# ReA4091_Rev4_2023-05-15_SCH.net
KiCad netlist of a schematic drawn in EasyEDA
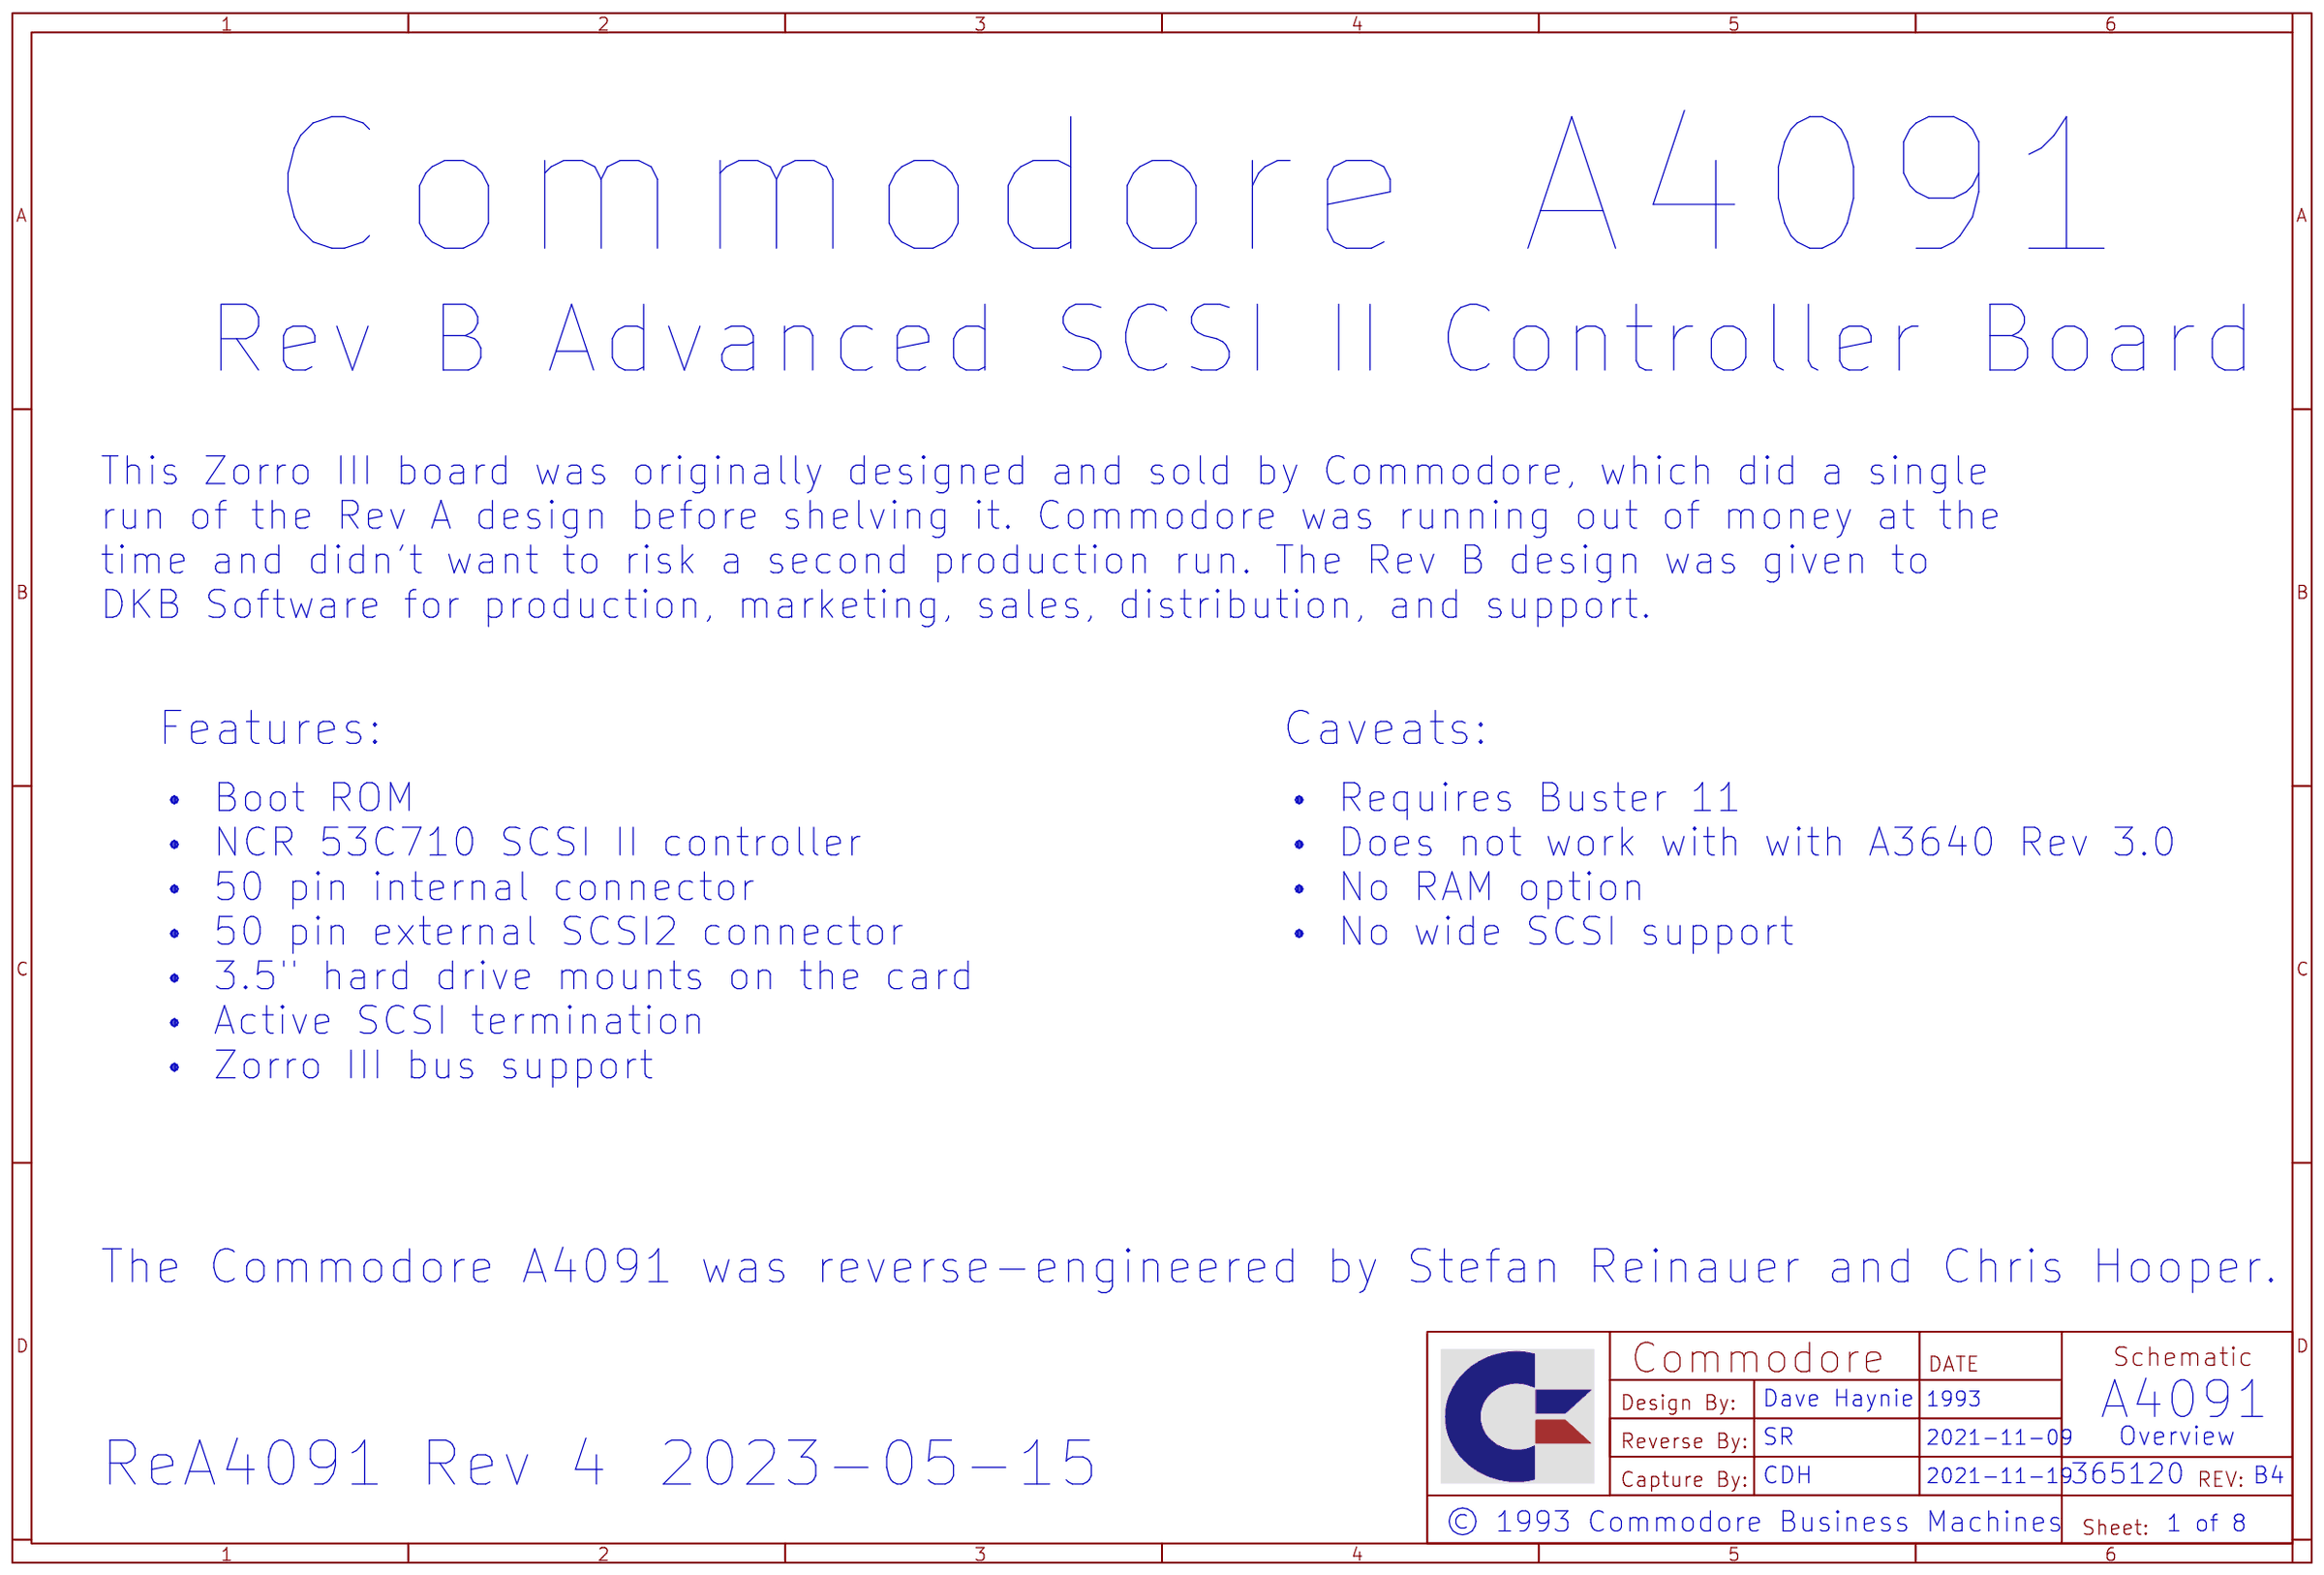
[diagram p0: Overview]
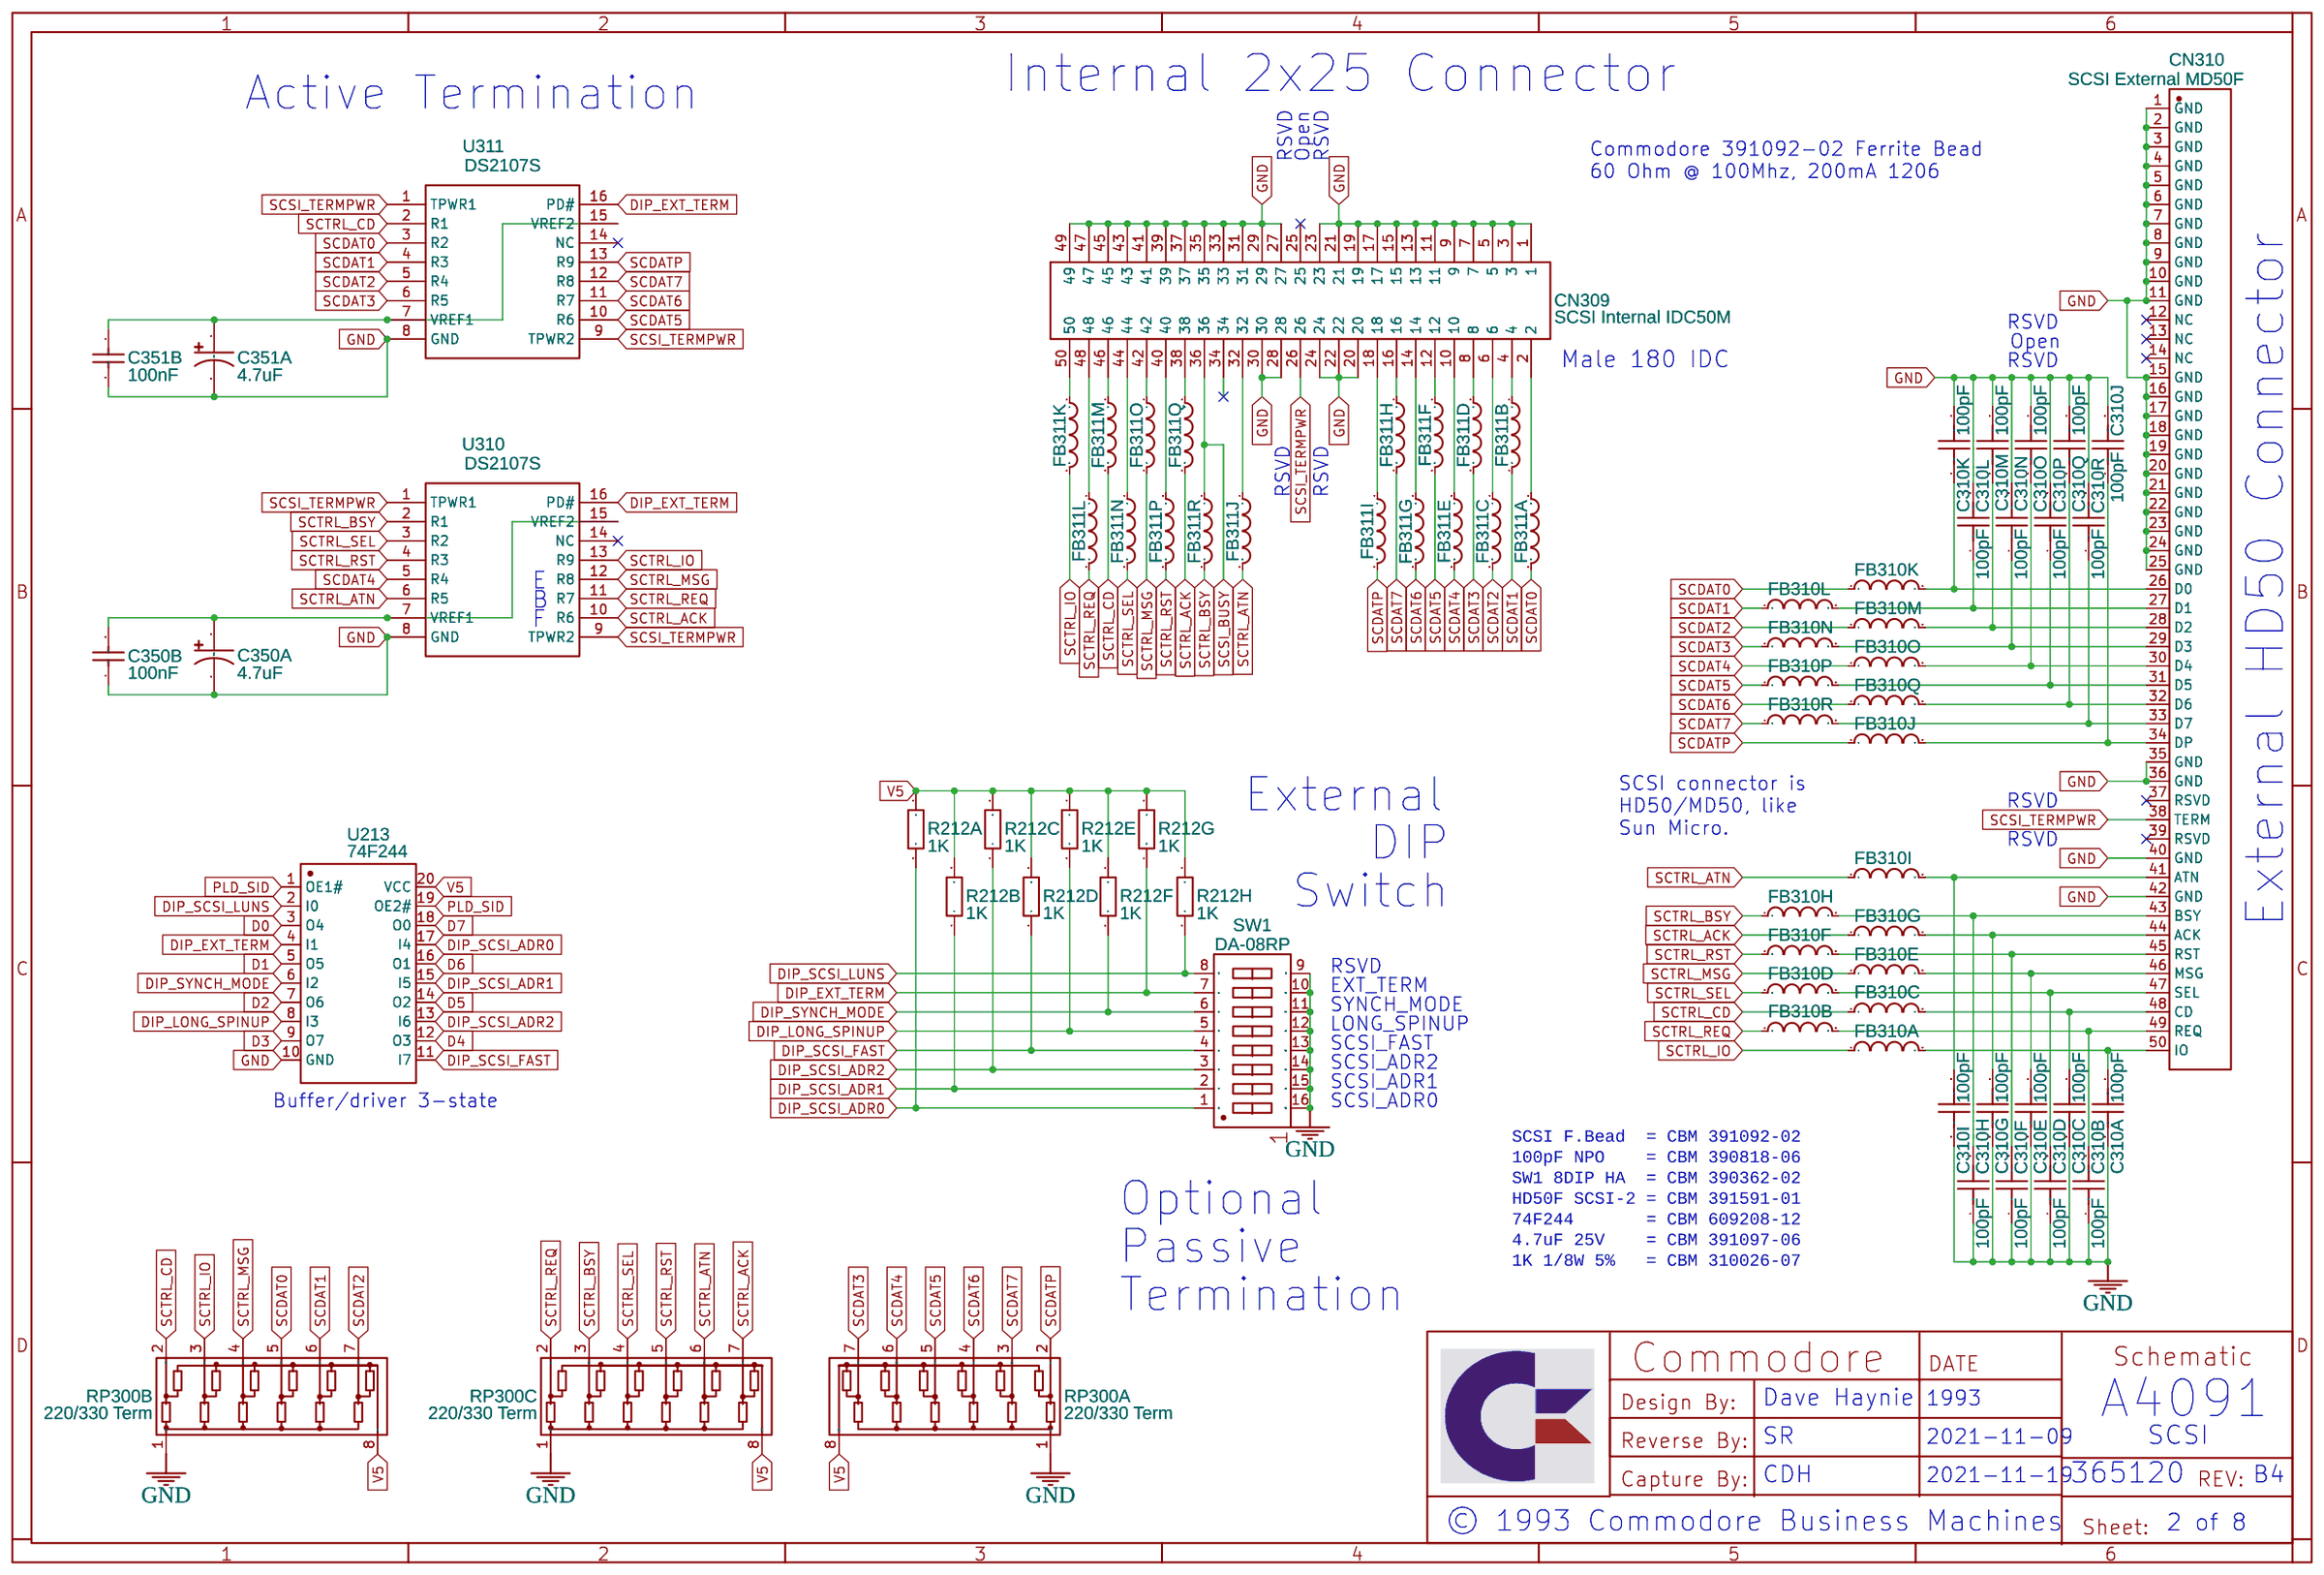
[diagram p1: SCSI]
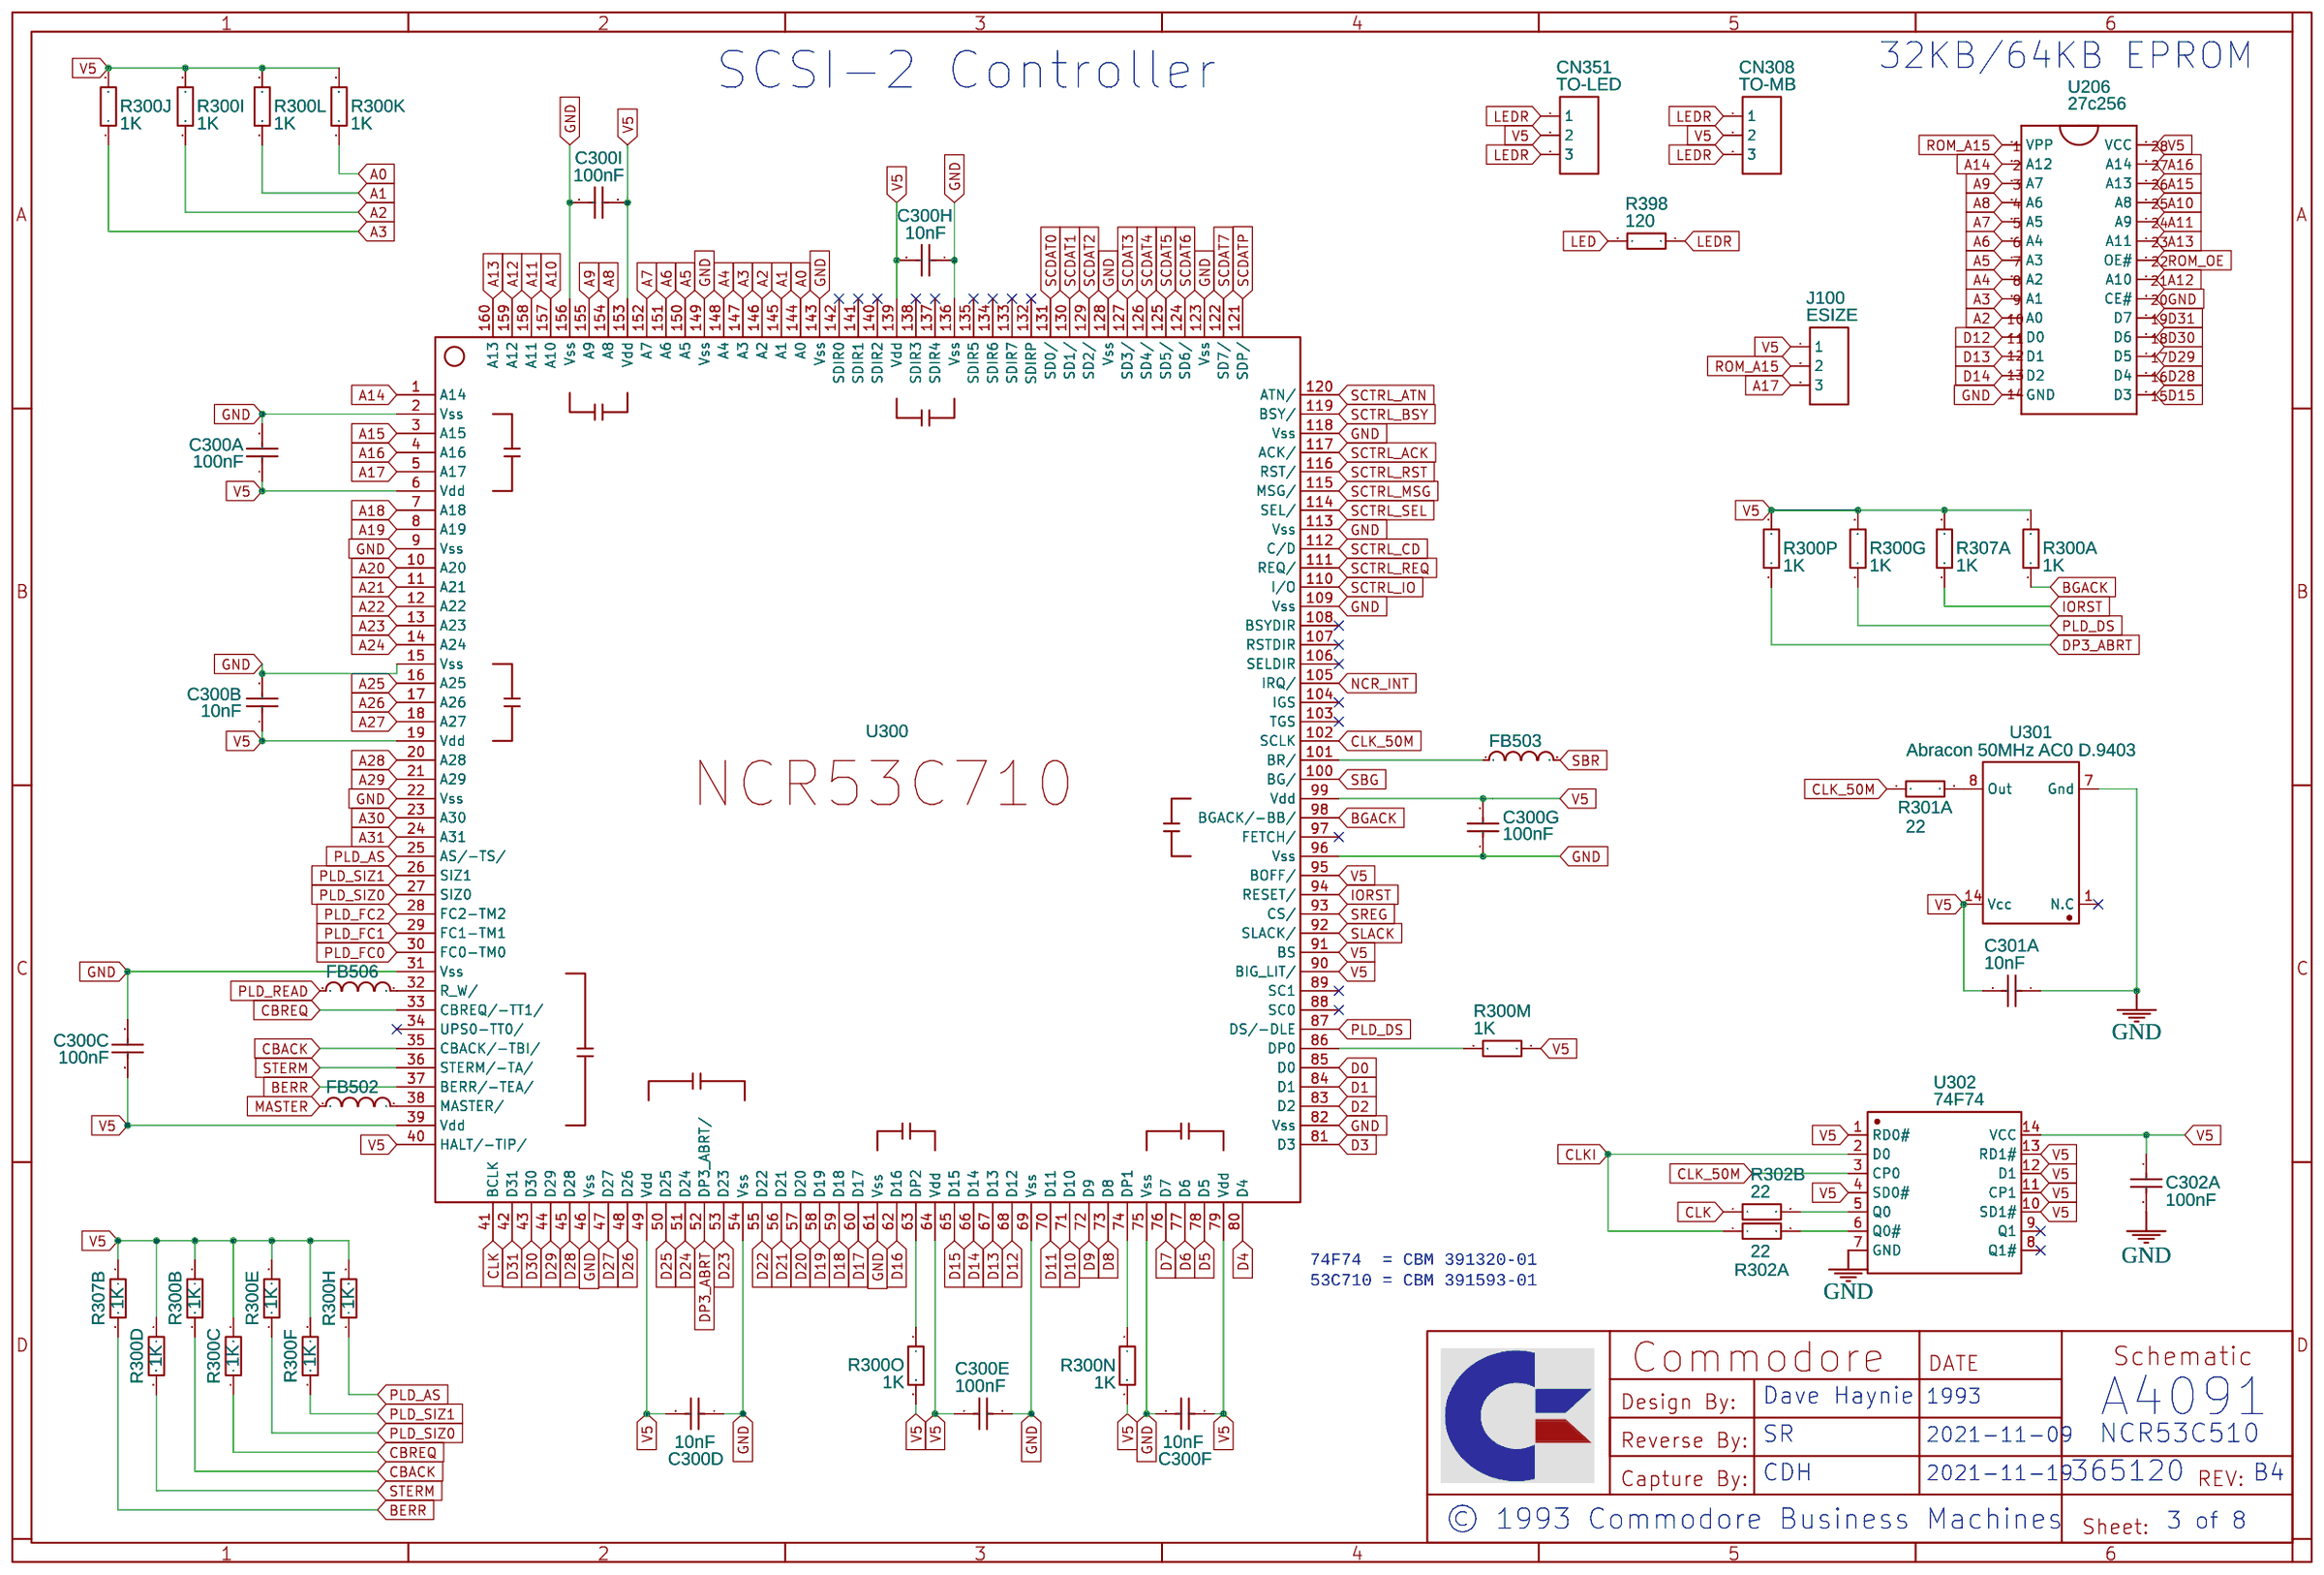
[diagram p2: NCR53C710]
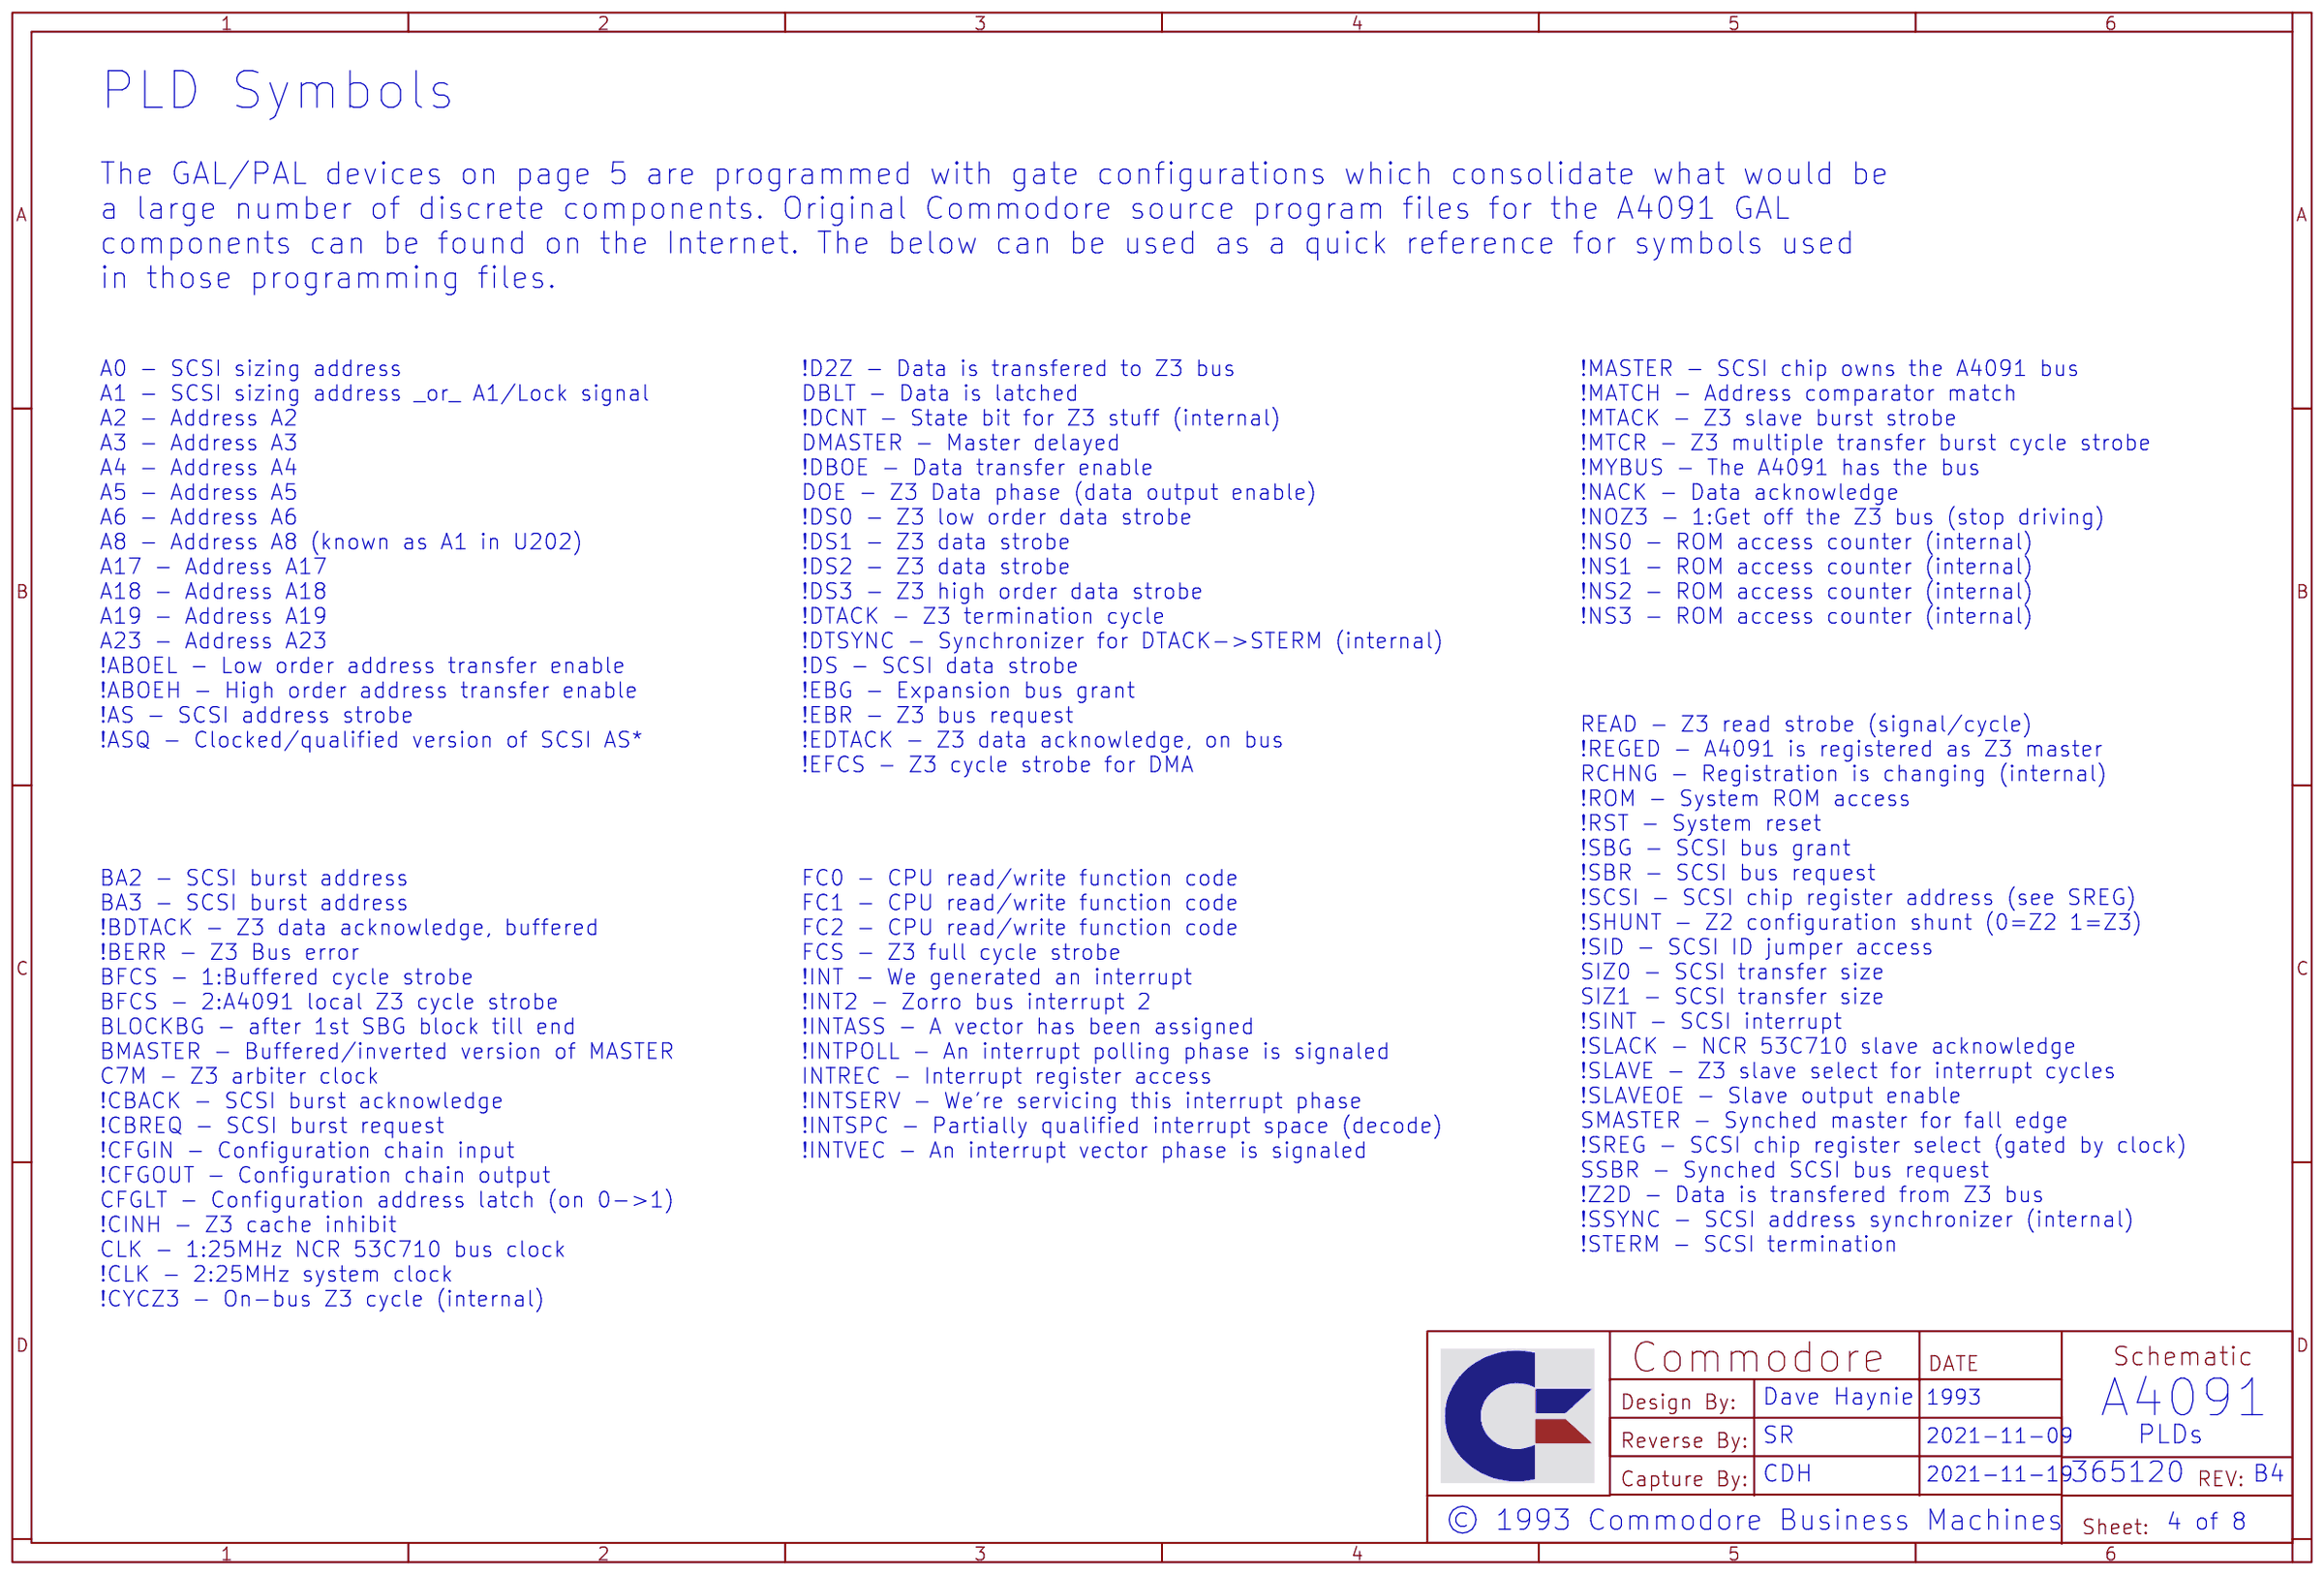
[diagram p3: PLD Symbols]
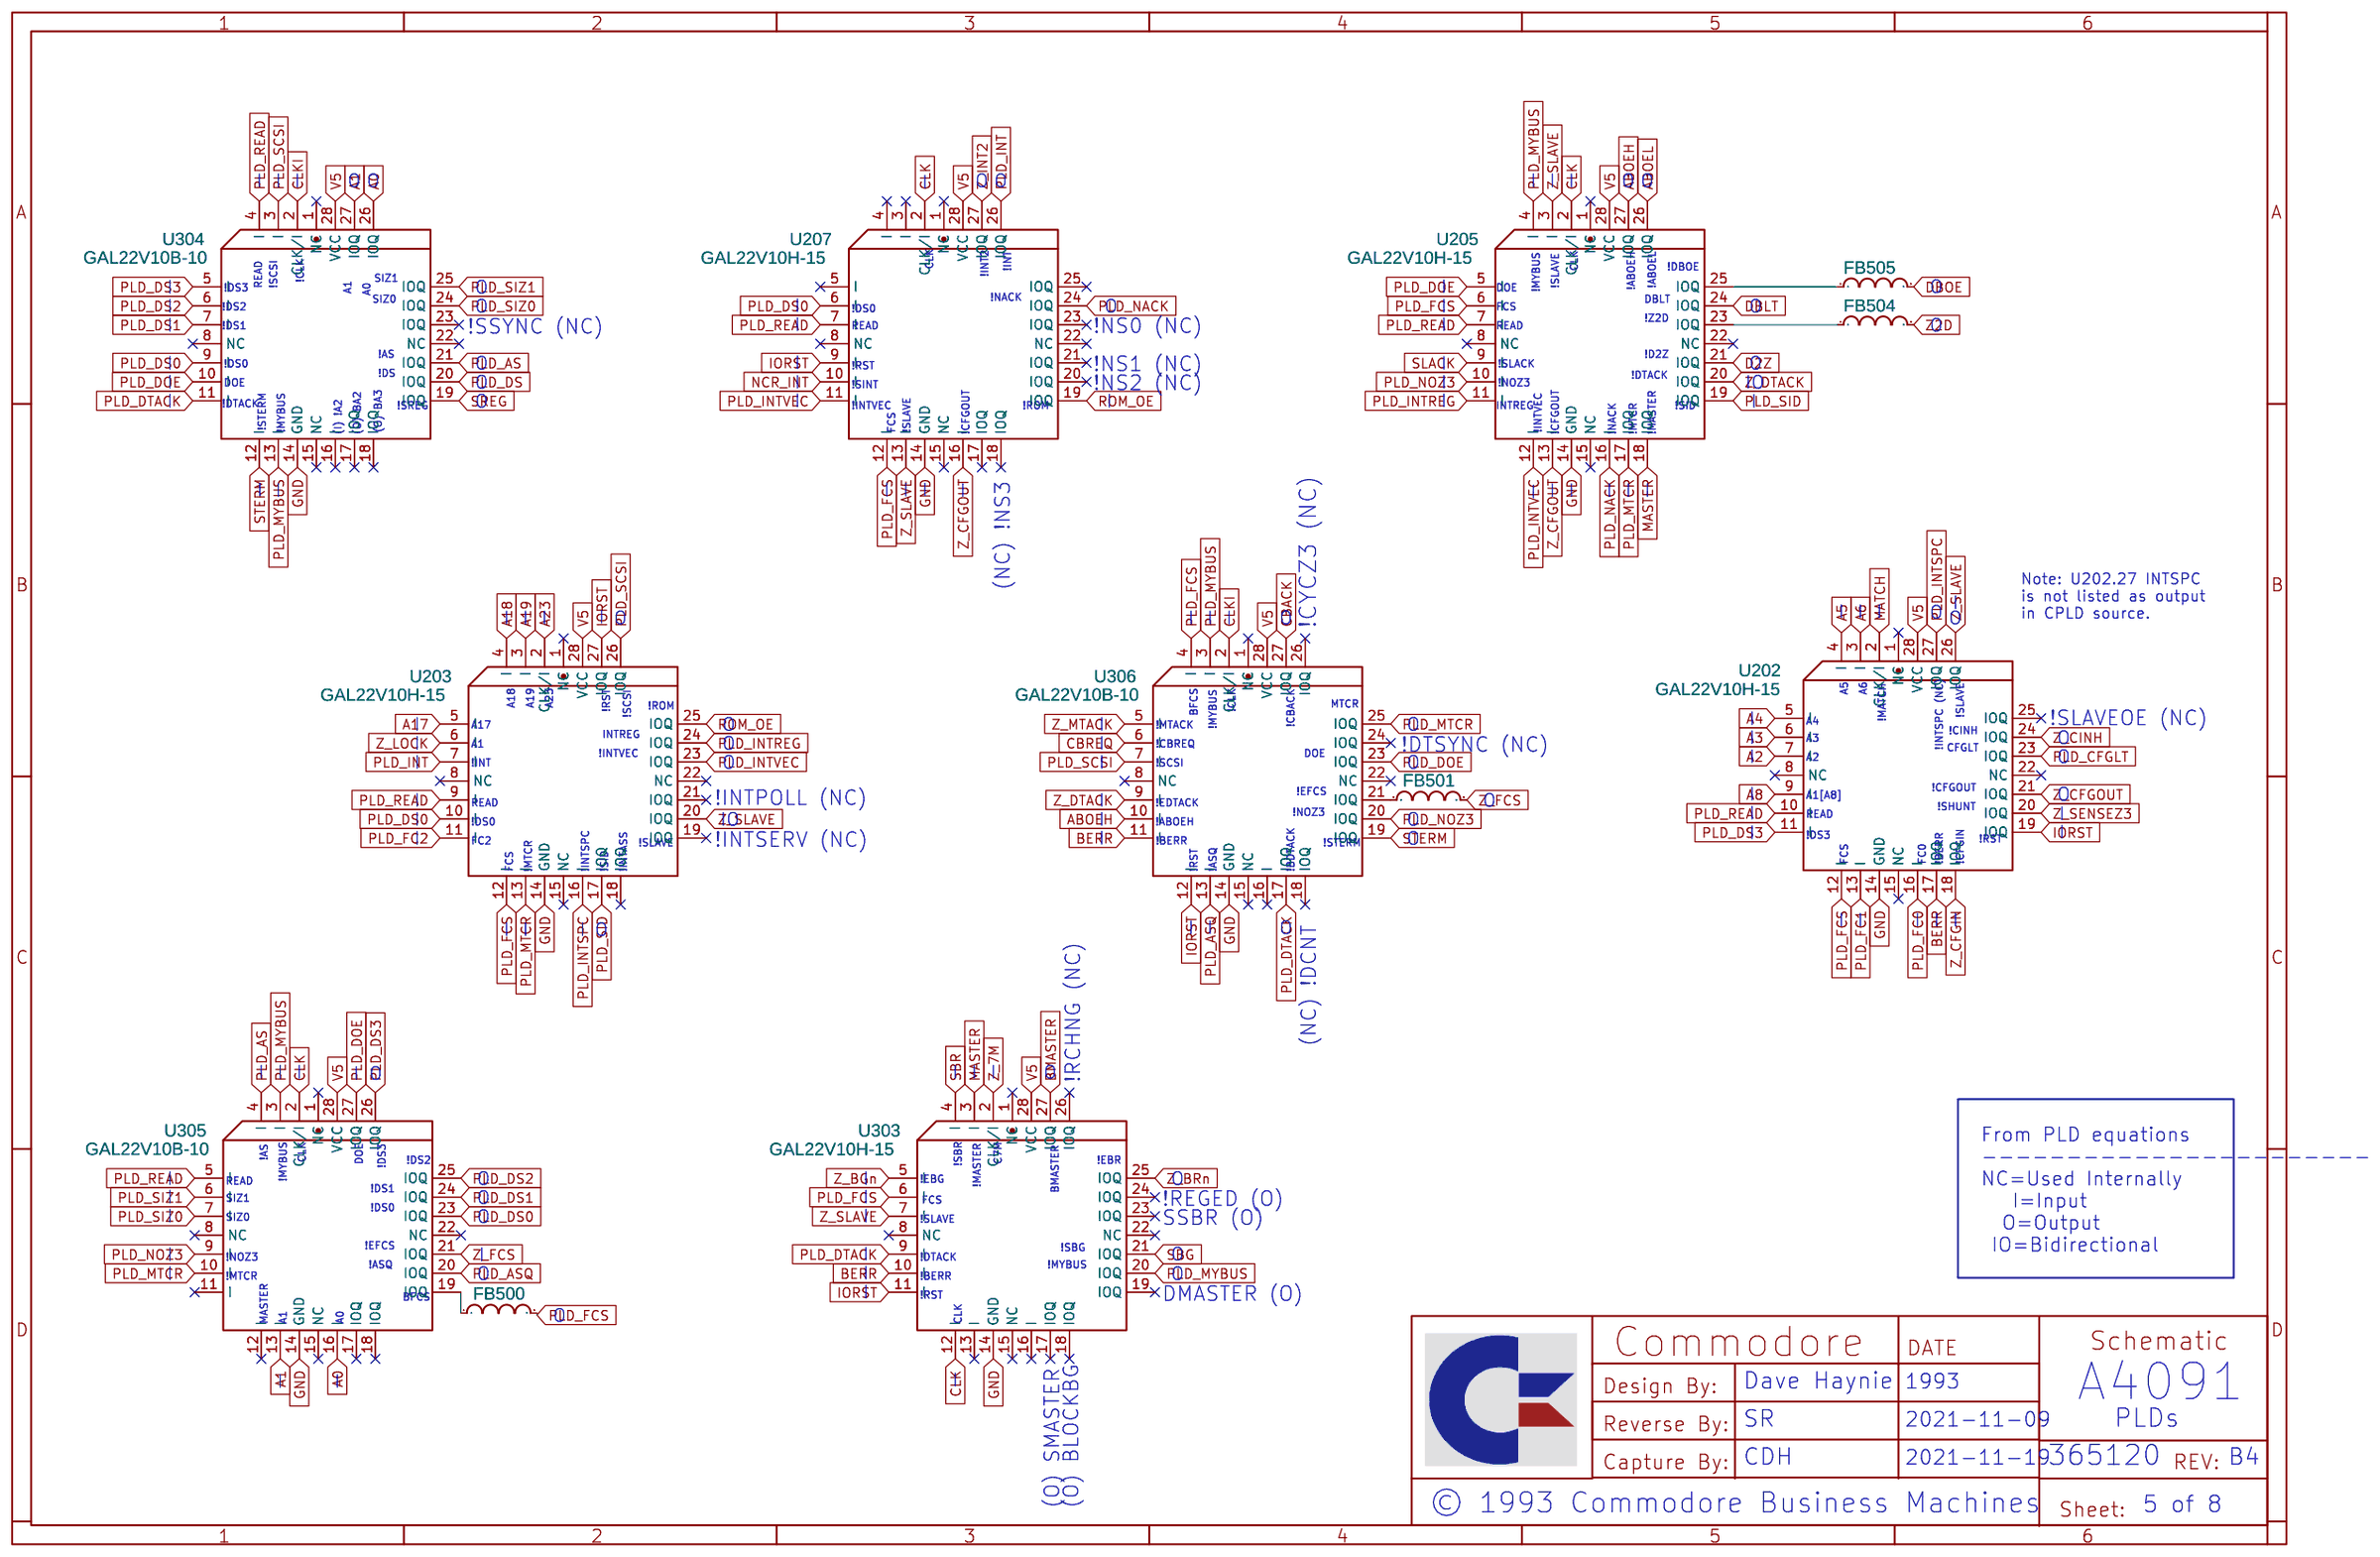
[diagram p4: PLDs]
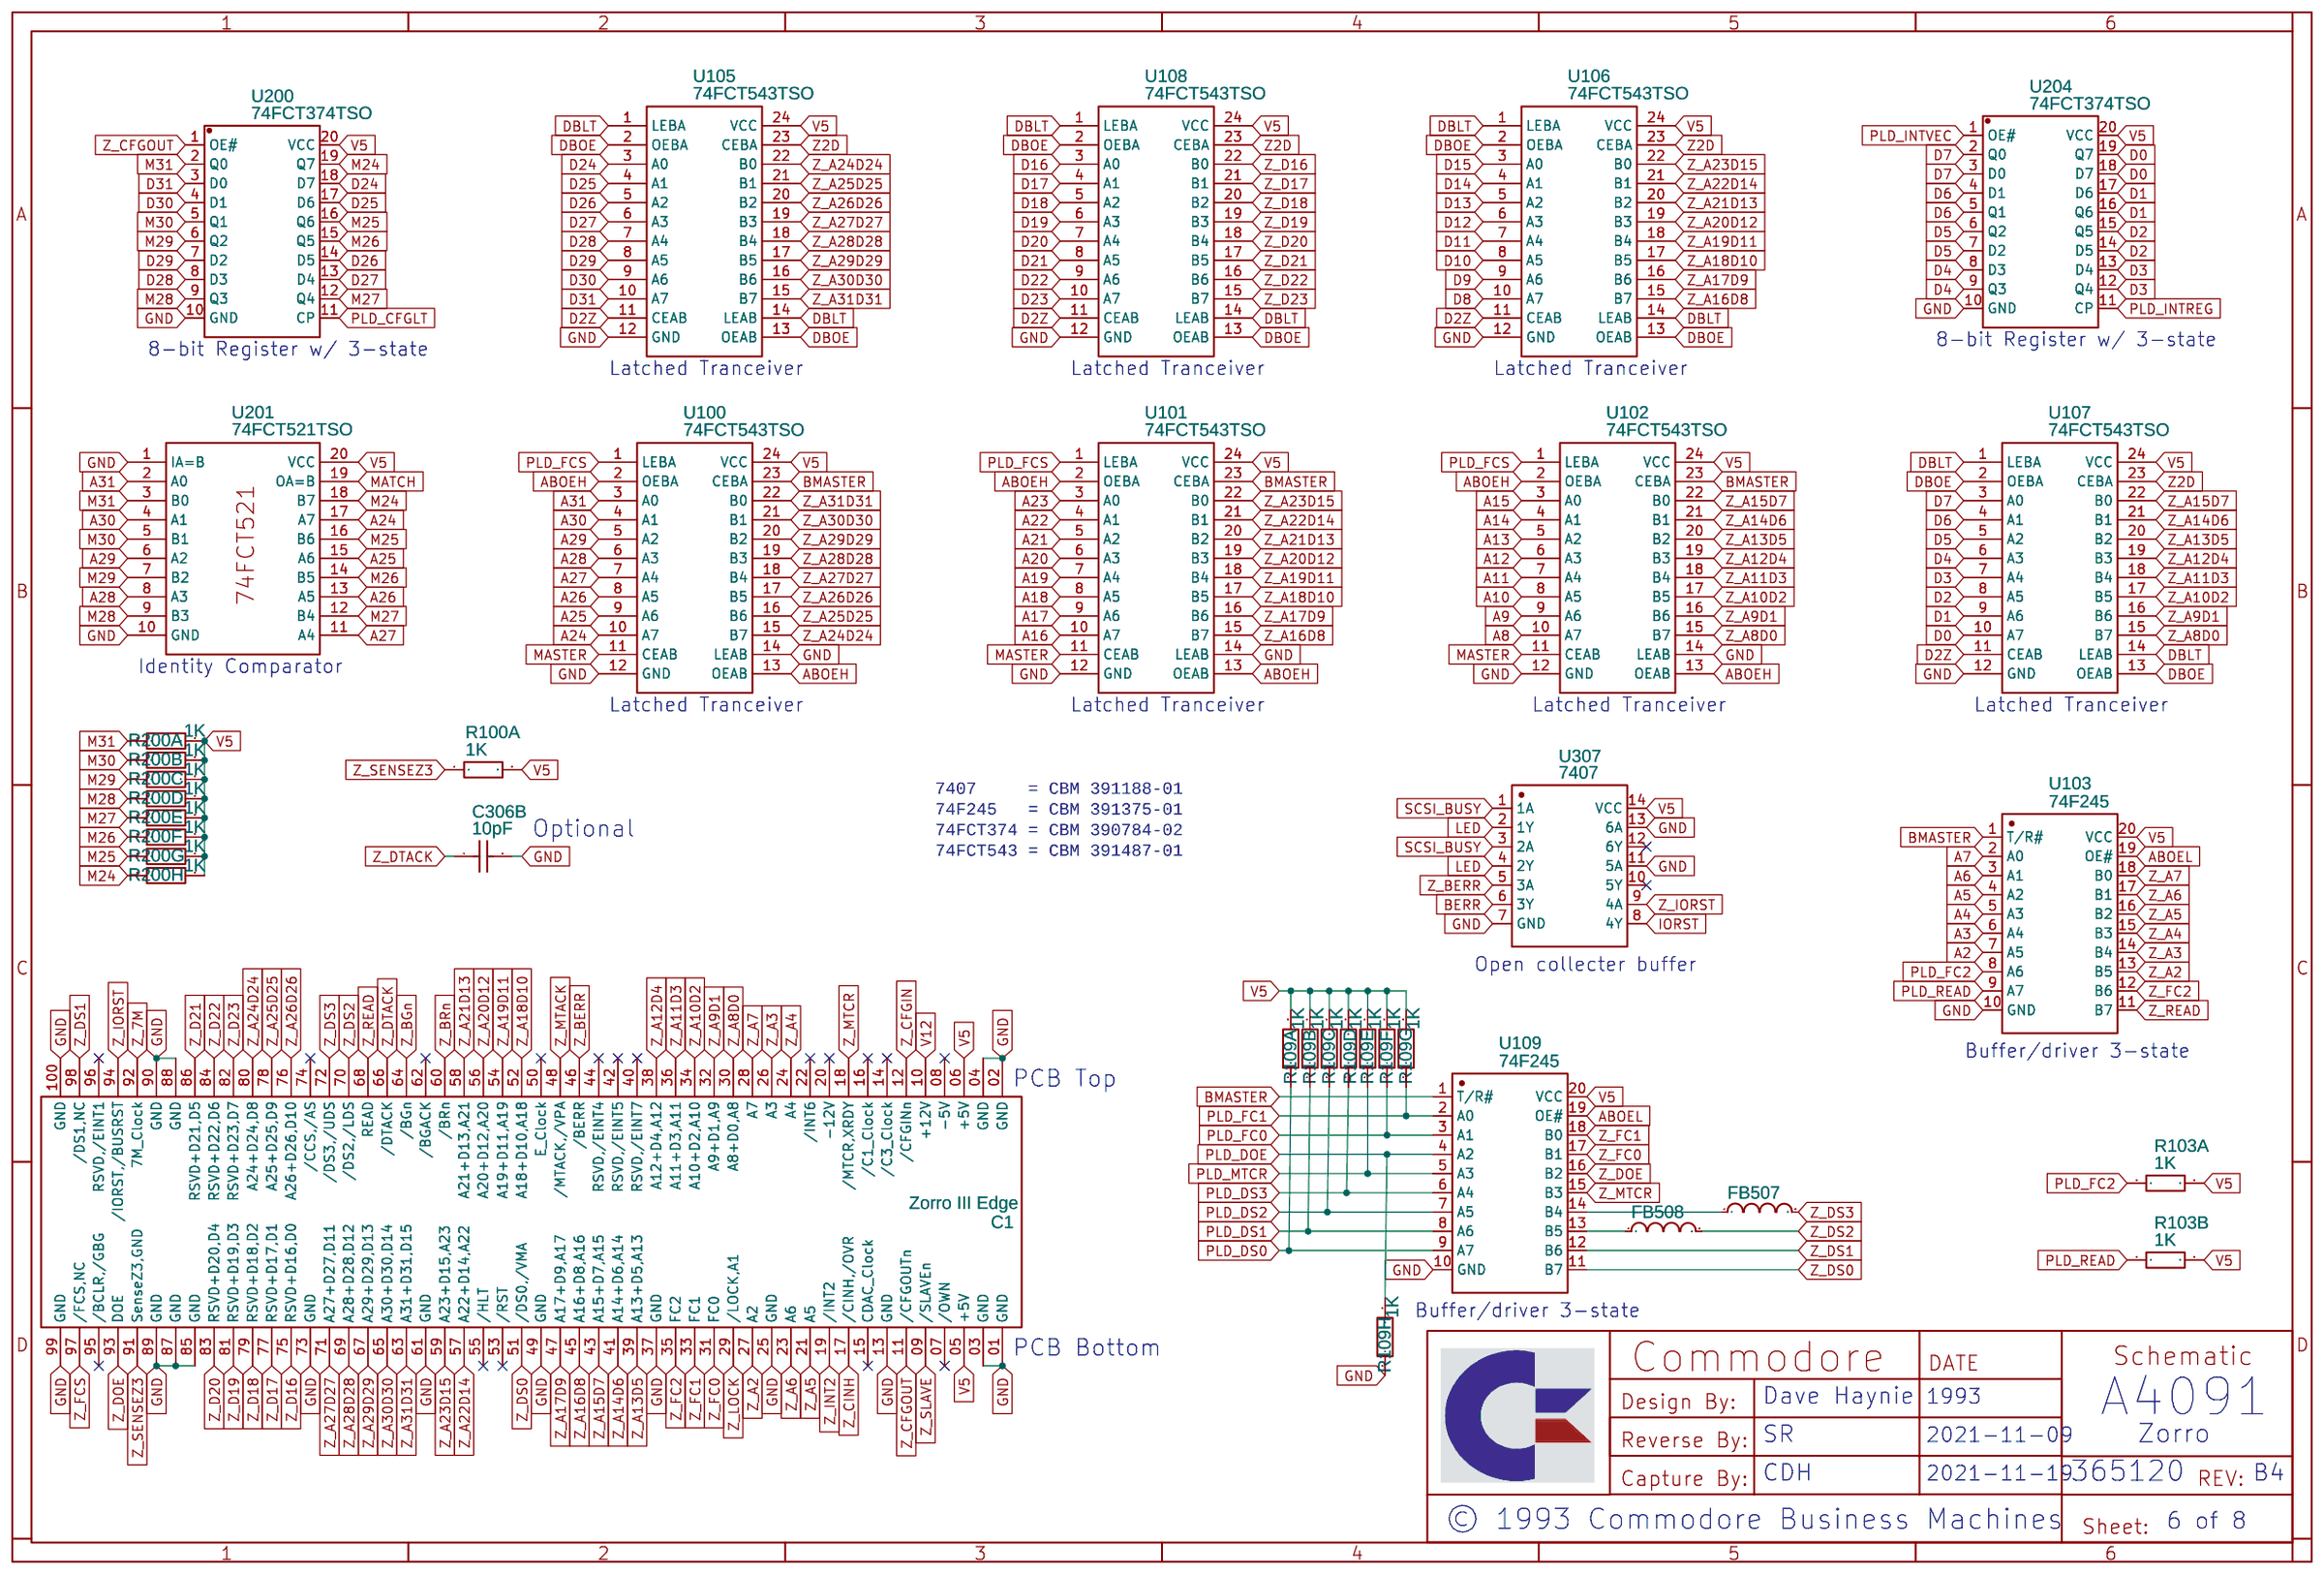
[diagram p5: Zorro]
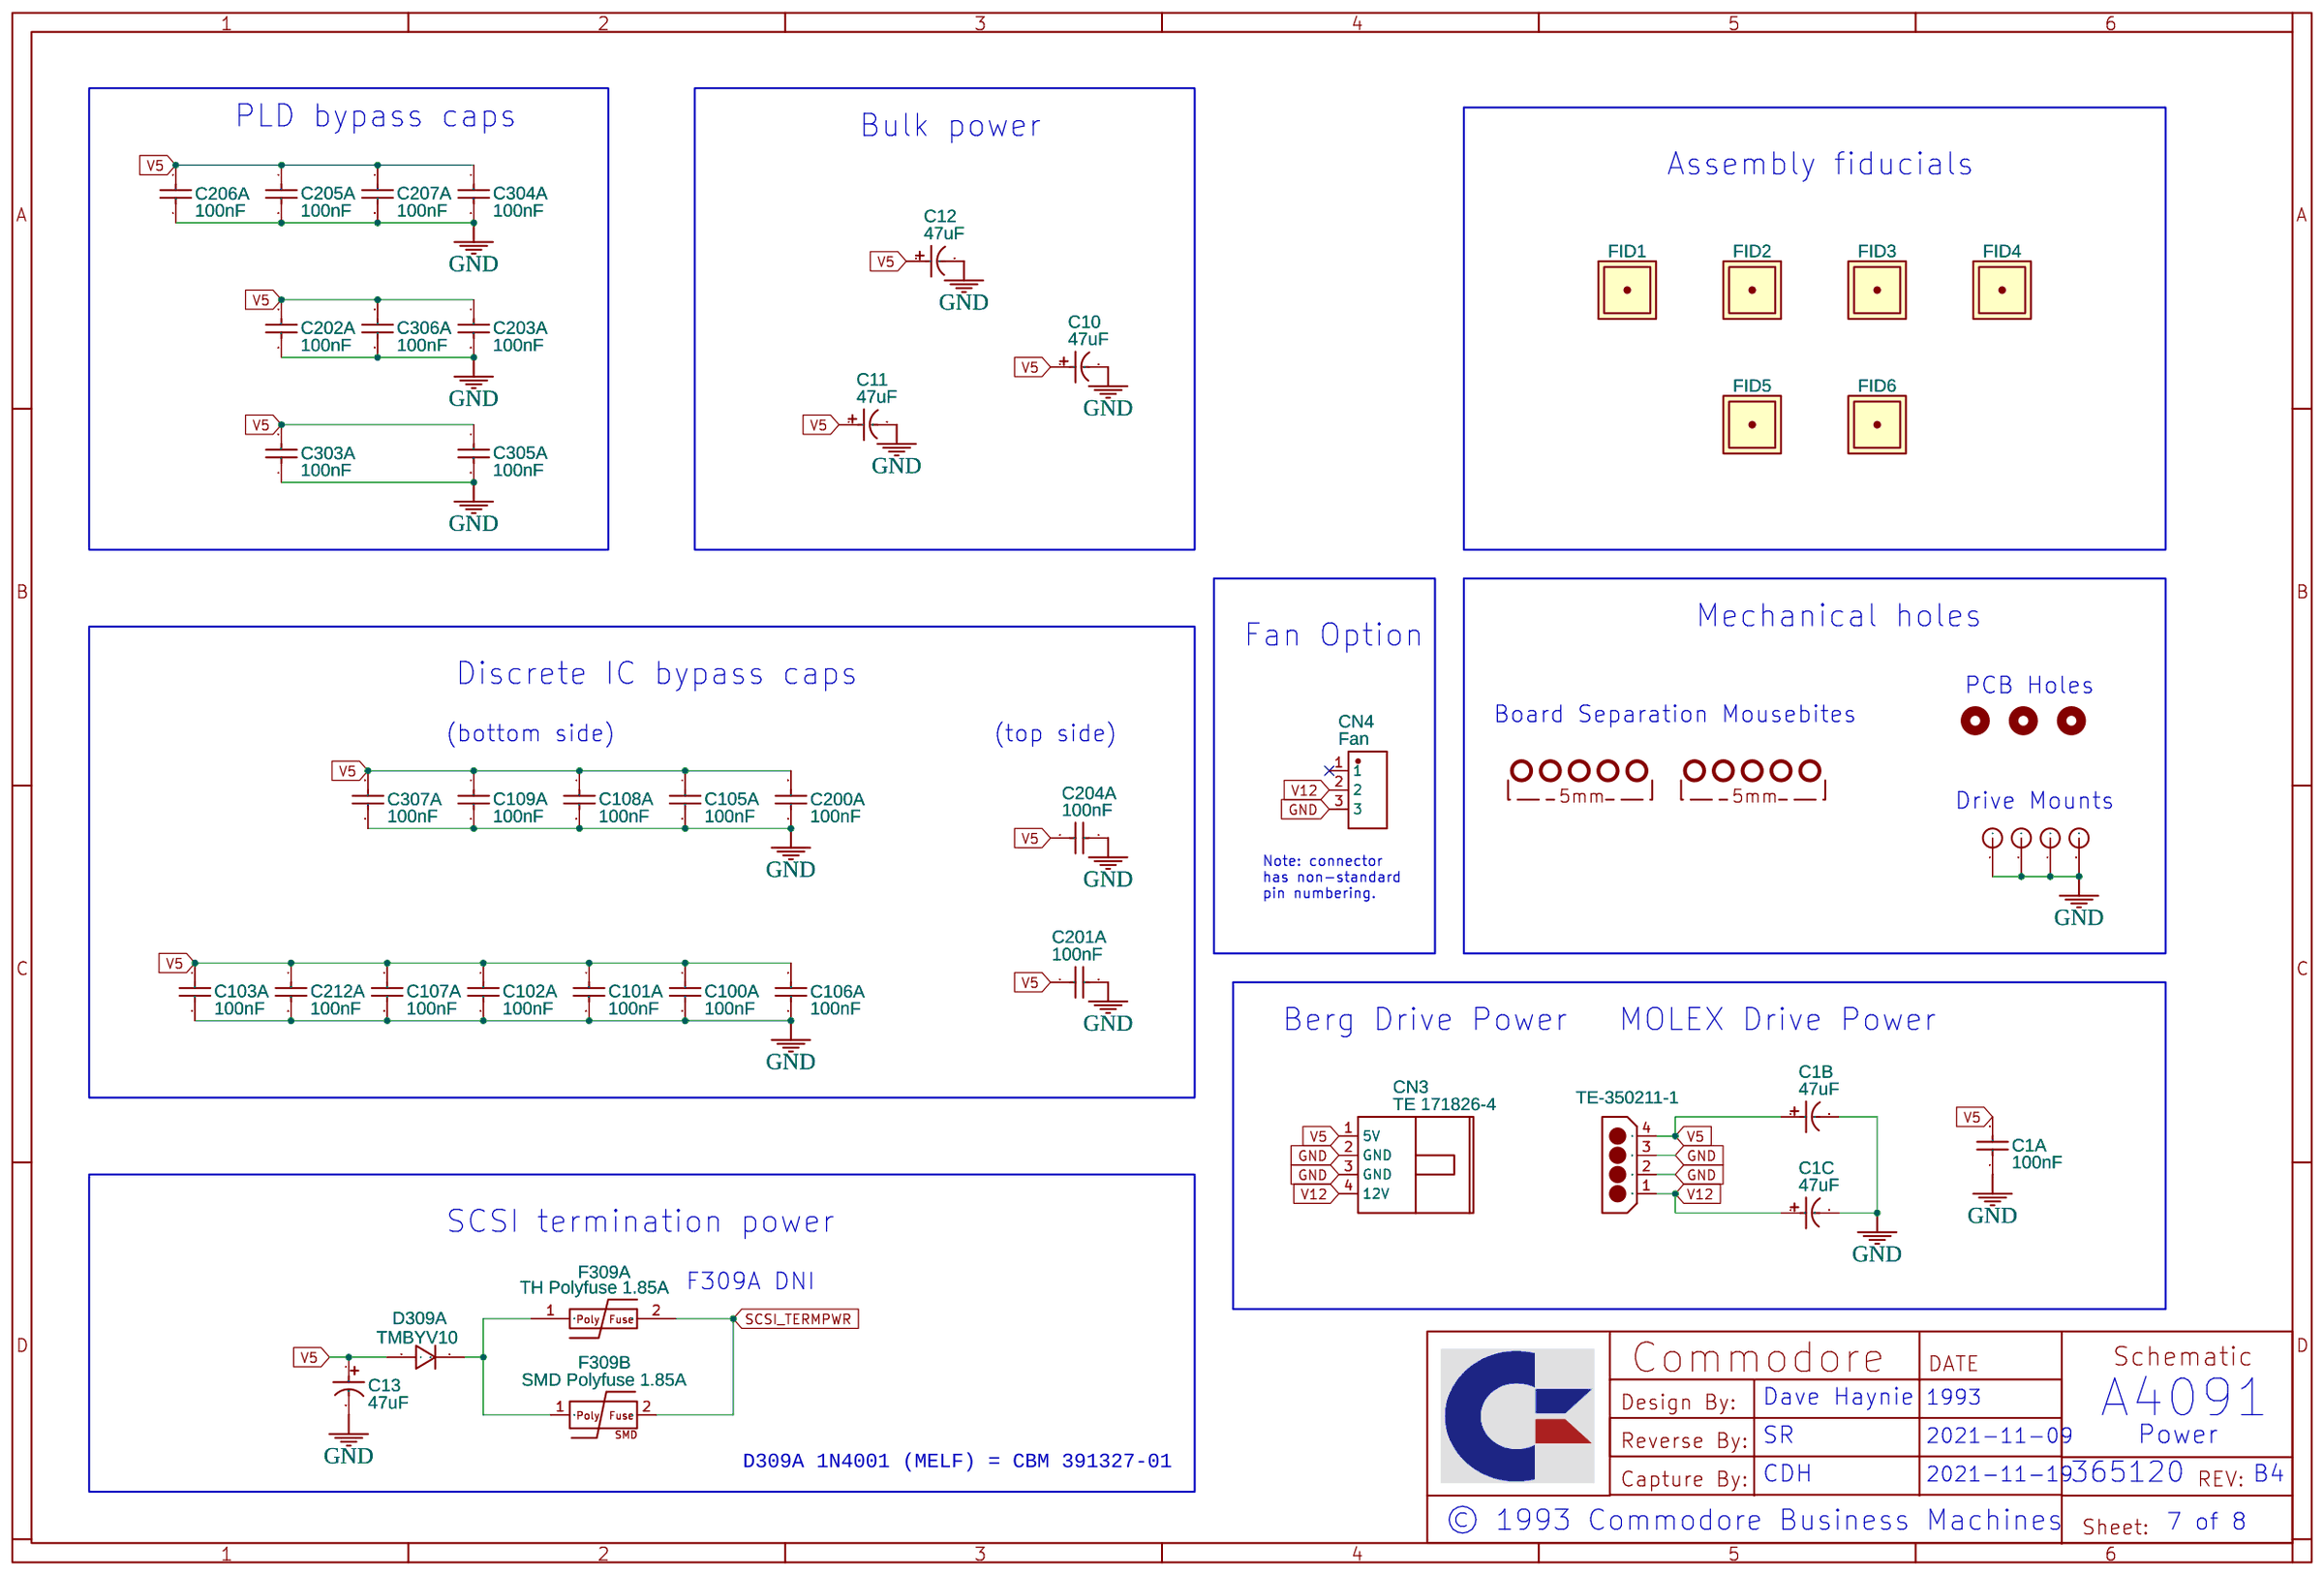
[diagram p6: Power]
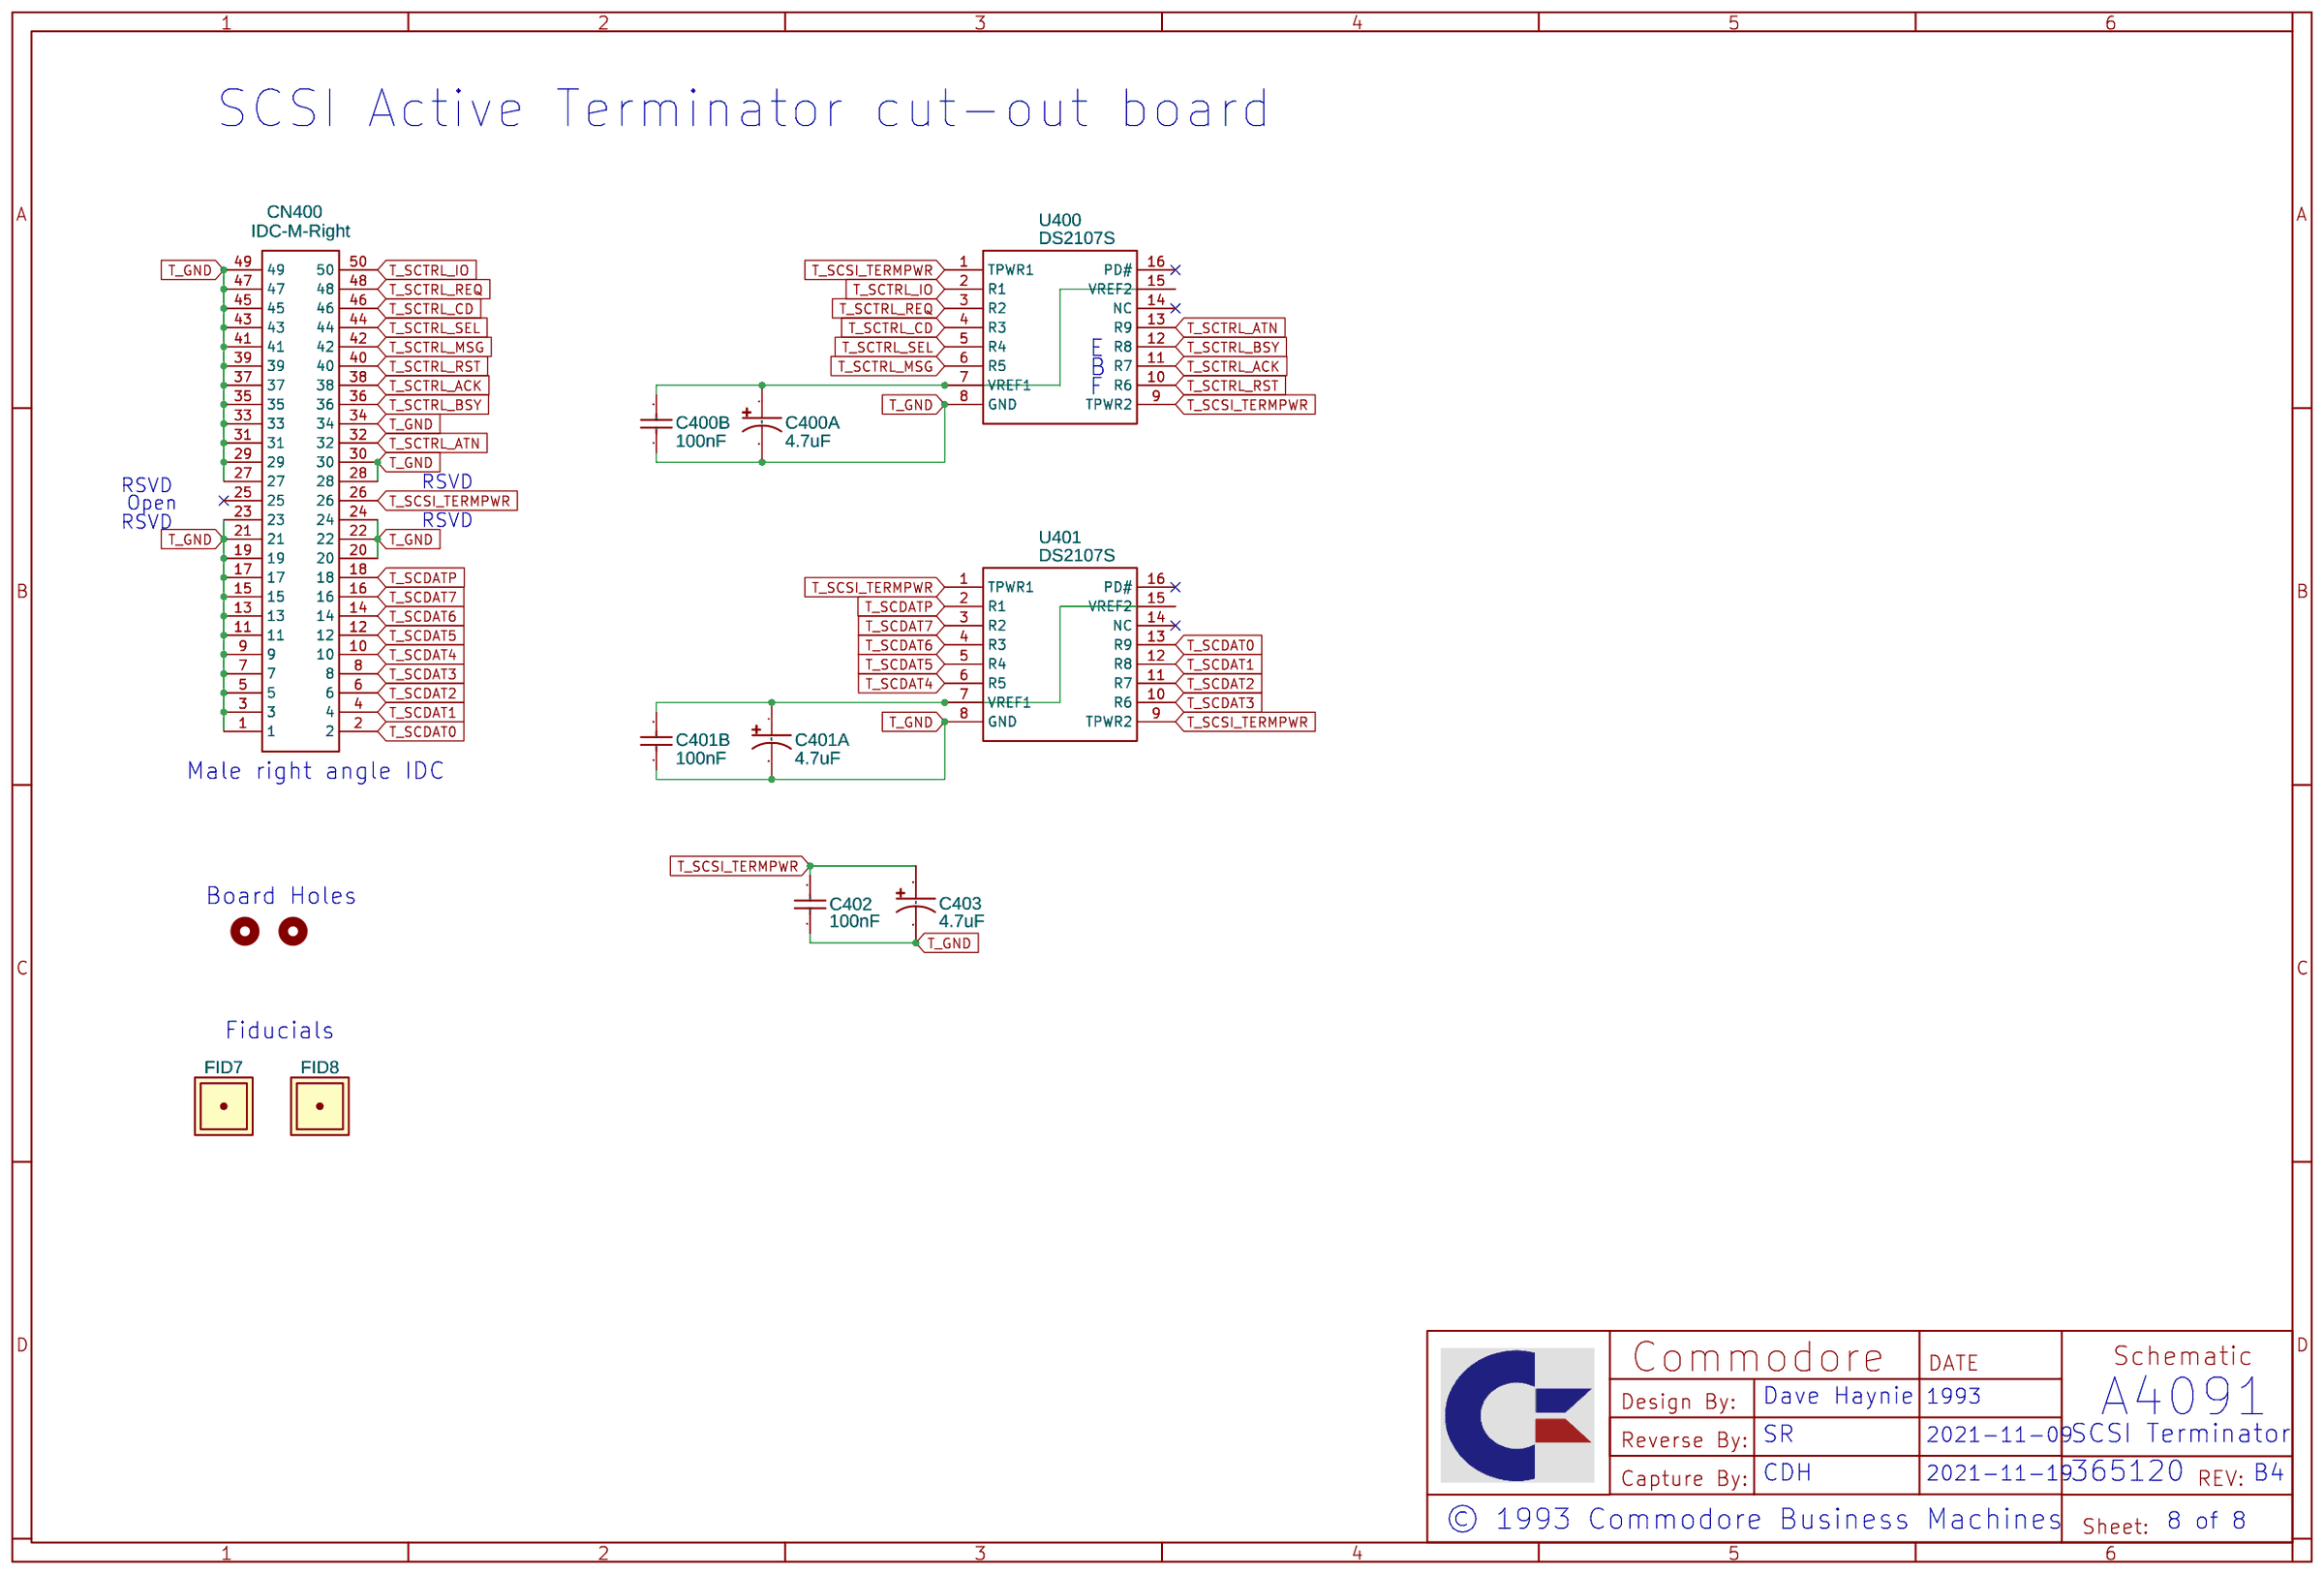
[diagram p7: SCSI Term]

(export (version "E")
  (design (tool "Eeschema 10.0.6"))
  (components
    (comp (ref "C310A")
      (value "100pF")
      (fields
        (field (name "BOM_Manufacturer Part") "TCC1206COG101J102ET")
        (field (name "BOM_Supplier Part") "C377018")
      )
      (libsource (lib "") (part "CL31C101JHFNNNE_11"))
    )
    (comp (ref "C310B")
      (value "100pF")
      (fields
        (field (name "BOM_Manufacturer Part") "TCC1206COG101J102ET")
        (field (name "BOM_Supplier Part") "C377018")
      )
      (libsource (lib "") (part "CL31C101JHFNNNE_5"))
    )
    (comp (ref "C310C")
      (value "100pF")
      (fields
        (field (name "BOM_Manufacturer Part") "TCC1206COG101J102ET")
        (field (name "BOM_Supplier Part") "C377018")
      )
      (libsource (lib "") (part "CL31C101JHFNNNE_3"))
    )
    (comp (ref "C310D")
      (value "100pF")
      (fields
        (field (name "BOM_Manufacturer Part") "TCC1206COG101J102ET")
        (field (name "BOM_Supplier Part") "C377018")
      )
      (libsource (lib "") (part "CL31C101JHFNNNE_8"))
    )
    (comp (ref "C310E")
      (value "100pF")
      (fields
        (field (name "BOM_Manufacturer Part") "TCC1206COG101J102ET")
        (field (name "BOM_Supplier Part") "C377018")
      )
      (libsource (lib "") (part "CL31C101JHFNNNE_1"))
    )
    (comp (ref "C310F")
      (value "100pF")
      (fields
        (field (name "BOM_Manufacturer Part") "TCC1206COG101J102ET")
        (field (name "BOM_Supplier Part") "C377018")
      )
      (libsource (lib "") (part "CL31C101JHFNNNE_7"))
    )
    (comp (ref "C310G")
      (value "100pF")
      (fields
        (field (name "BOM_Manufacturer Part") "TCC1206COG101J102ET")
        (field (name "BOM_Supplier Part") "C377018")
      )
      (libsource (lib "") (part "CL31C101JHFNNNE_6"))
    )
    (comp (ref "C310H")
      (value "100pF")
      (fields
        (field (name "BOM_Manufacturer Part") "TCC1206COG101J102ET")
        (field (name "BOM_Supplier Part") "C377018")
      )
      (libsource (lib "") (part "CL31C101JHFNNNE_15"))
    )
    (comp (ref "C310I")
      (value "100pF")
      (fields
        (field (name "BOM_Manufacturer Part") "TCC1206COG101J102ET")
        (field (name "BOM_Supplier Part") "C377018")
      )
      (libsource (lib "") (part "CL31C101JHFNNNE_16"))
    )
    (comp (ref "C310J")
      (value "100pF")
      (fields
        (field (name "BOM_Manufacturer Part") "TCC1206COG101J102ET")
        (field (name "BOM_Supplier Part") "C377018")
      )
      (libsource (lib "") (part "CL31C101JHFNNNE_13"))
    )
    (comp (ref "C310K")
      (value "100pF")
      (fields
        (field (name "BOM_Manufacturer Part") "TCC1206COG101J102ET")
        (field (name "BOM_Supplier Part") "C377018")
      )
      (libsource (lib "") (part "CL31C101JHFNNNE_14"))
    )
    (comp (ref "C310L")
      (value "100pF")
      (fields
        (field (name "BOM_Manufacturer Part") "TCC1206COG101J102ET")
        (field (name "BOM_Supplier Part") "C377018")
      )
      (libsource (lib "") (part "CL31C101JHFNNNE_17"))
    )
    (comp (ref "C310M")
      (value "100pF")
      (fields
        (field (name "BOM_Manufacturer Part") "TCC1206COG101J102ET")
        (field (name "BOM_Supplier Part") "C377018")
      )
      (libsource (lib "") (part "CL31C101JHFNNNE"))
    )
    (comp (ref "C310N")
      (value "100pF")
      (fields
        (field (name "BOM_Manufacturer Part") "TCC1206COG101J102ET")
        (field (name "BOM_Supplier Part") "C377018")
      )
      (libsource (lib "") (part "CL31C101JHFNNNE_2"))
    )
    (comp (ref "C310O")
      (value "100pF")
      (fields
        (field (name "BOM_Manufacturer Part") "TCC1206COG101J102ET")
        (field (name "BOM_Supplier Part") "C377018")
      )
      (libsource (lib "") (part "CL31C101JHFNNNE_4"))
    )
    (comp (ref "C310P")
      (value "100pF")
      (fields
        (field (name "BOM_Manufacturer Part") "TCC1206COG101J102ET")
        (field (name "BOM_Supplier Part") "C377018")
      )
      (libsource (lib "") (part "CL31C101JHFNNNE_12"))
    )
    (comp (ref "C310Q")
      (value "100pF")
      (fields
        (field (name "BOM_Manufacturer Part") "TCC1206COG101J102ET")
        (field (name "BOM_Supplier Part") "C377018")
      )
      (libsource (lib "") (part "CL31C101JHFNNNE_10"))
    )
    (comp (ref "C310R")
      (value "100pF")
      (fields
        (field (name "BOM_Manufacturer Part") "TCC1206COG101J102ET")
        (field (name "BOM_Supplier Part") "C377018")
      )
      (libsource (lib "") (part "CL31C101JHFNNNE_9"))
    )
    (comp (ref "C350A")
      (value "4.7uF")
      (fields
        (field (name "BOM_Manufacturer Part") "UWX1E4R7MCL1GB")
        (field (name "BOM_Supplier Part") "C445042")
      )
      (libsource (lib "") (part "VZH4R7M1HTR-0406_1"))
    )
    (comp (ref "C350B")
      (value "100nF")
      (fields
        (field (name "BOM_Manufacturer Part") "CL31B104KBCNNNC")
        (field (name "BOM_Supplier Part") "C24497")
      )
      (libsource (lib "") (part "CL31B104KBCNNNC"))
    )
    (comp (ref "C351A")
      (value "4.7uF")
      (fields
        (field (name "BOM_Manufacturer Part") "UWX1E4R7MCL1GB")
        (field (name "BOM_Supplier Part") "C445042")
      )
      (libsource (lib "") (part "VZH4R7M1HTR-0406"))
    )
    (comp (ref "C351B")
      (value "100nF")
      (fields
        (field (name "BOM_Manufacturer Part") "CL31B104KBCNNNC")
        (field (name "BOM_Supplier Part") "C24497")
      )
      (libsource (lib "") (part "CL31B104KBCNNNC_1"))
    )
    (comp (ref "CN309")
      (value "SCSI Internal IDC50M")
      (fields
        (field (name "BOM_Manufacturer Part") "B-3000S50P-0110")
        (field (name "BOM_Supplier Part") "C146633")
      )
      (libsource (lib "") (part "300S-50P"))
    )
    (comp (ref "CN310") (value "SCSI External MD50F") (libsource (lib "") (part "SCSI External MD50F")))
    (comp (ref "FB310A")
      (value "60Ω")
      (fields
        (field (name "BOM_Manufacturer Part") "CBG321609U600T")
        (field (name "BOM_Supplier Part") "C1020")
      )
      (libsource (lib "") (part "MLB3216-601(f)_32"))
    )
    (comp (ref "FB310B")
      (value "60Ω")
      (fields
        (field (name "BOM_Manufacturer Part") "CBG321609U600T")
        (field (name "BOM_Supplier Part") "C1020")
      )
      (libsource (lib "") (part "MLB3216-601(f)_28"))
    )
    (comp (ref "FB310C")
      (value "60Ω")
      (fields
        (field (name "BOM_Manufacturer Part") "CBG321609U600T")
        (field (name "BOM_Supplier Part") "C1020")
      )
      (libsource (lib "") (part "MLB3216-601(f)_26"))
    )
    (comp (ref "FB310D")
      (value "60Ω")
      (fields
        (field (name "BOM_Manufacturer Part") "CBG321609U600T")
        (field (name "BOM_Supplier Part") "C1020")
      )
      (libsource (lib "") (part "MLB3216-601(f)_19"))
    )
    (comp (ref "FB310E")
      (value "60Ω")
      (fields
        (field (name "BOM_Manufacturer Part") "CBG321609U600T")
        (field (name "BOM_Supplier Part") "C1020")
      )
      (libsource (lib "") (part "MLB3216-601(f)_4"))
    )
    (comp (ref "FB310F")
      (value "60Ω")
      (fields
        (field (name "BOM_Manufacturer Part") "CBG321609U600T")
        (field (name "BOM_Supplier Part") "C1020")
      )
      (libsource (lib "") (part "MLB3216-601(f)_31"))
    )
    (comp (ref "FB310G")
      (value "60Ω")
      (fields
        (field (name "BOM_Manufacturer Part") "CBG321609U600T")
        (field (name "BOM_Supplier Part") "C1020")
      )
      (libsource (lib "") (part "MLB3216-601(f)_5"))
    )
    (comp (ref "FB310H")
      (value "60Ω")
      (fields
        (field (name "BOM_Manufacturer Part") "CBG321609U600T")
        (field (name "BOM_Supplier Part") "C1020")
      )
      (libsource (lib "") (part "MLB3216-601(f)_34"))
    )
    (comp (ref "FB310I")
      (value "60Ω")
      (fields
        (field (name "BOM_Manufacturer Part") "CBG321609U600T")
        (field (name "BOM_Supplier Part") "C1020")
      )
      (libsource (lib "") (part "MLB3216-601(f)_1"))
    )
    (comp (ref "FB310J")
      (value "60Ω")
      (fields
        (field (name "BOM_Manufacturer Part") "CBG321609U600T")
        (field (name "BOM_Supplier Part") "C1020")
      )
      (libsource (lib "") (part "MLB3216-601(f)_9"))
    )
    (comp (ref "FB310K")
      (value "60Ω")
      (fields
        (field (name "BOM_Manufacturer Part") "CBG321609U600T")
        (field (name "BOM_Supplier Part") "C1020")
      )
      (libsource (lib "") (part "MLB3216-601(f)_29"))
    )
    (comp (ref "FB310L")
      (value "60Ω")
      (fields
        (field (name "BOM_Manufacturer Part") "CBG321609U600T")
        (field (name "BOM_Supplier Part") "C1020")
      )
      (libsource (lib "") (part "MLB3216-601(f)_24"))
    )
    (comp (ref "FB310M")
      (value "60Ω")
      (fields
        (field (name "BOM_Manufacturer Part") "CBG321609U600T")
        (field (name "BOM_Supplier Part") "C1020")
      )
      (libsource (lib "") (part "MLB3216-601(f)"))
    )
    (comp (ref "FB310N")
      (value "60Ω")
      (fields
        (field (name "BOM_Manufacturer Part") "CBG321609U600T")
        (field (name "BOM_Supplier Part") "C1020")
      )
      (libsource (lib "") (part "MLB3216-601(f)_22"))
    )
    (comp (ref "FB310O")
      (value "60Ω")
      (fields
        (field (name "BOM_Manufacturer Part") "CBG321609U600T")
        (field (name "BOM_Supplier Part") "C1020")
      )
      (libsource (lib "") (part "MLB3216-601(f)_12"))
    )
    (comp (ref "FB310P")
      (value "60Ω")
      (fields
        (field (name "BOM_Manufacturer Part") "CBG321609U600T")
        (field (name "BOM_Supplier Part") "C1020")
      )
      (libsource (lib "") (part "MLB3216-601(f)_6"))
    )
    (comp (ref "FB310Q")
      (value "60Ω")
      (fields
        (field (name "BOM_Manufacturer Part") "CBG321609U600T")
        (field (name "BOM_Supplier Part") "C1020")
      )
      (libsource (lib "") (part "MLB3216-601(f)_11"))
    )
    (comp (ref "FB310R")
      (value "60Ω")
      (fields
        (field (name "BOM_Manufacturer Part") "CBG321609U600T")
        (field (name "BOM_Supplier Part") "C1020")
      )
      (libsource (lib "") (part "MLB3216-601(f)_17"))
    )
    (comp (ref "FB311A")
      (value "60Ω")
      (fields
        (field (name "BOM_Manufacturer Part") "CBG321609U600T")
        (field (name "BOM_Supplier Part") "C1020")
      )
      (libsource (lib "") (part "MLB3216-601(f)_16"))
    )
    (comp (ref "FB311B")
      (value "60Ω")
      (fields
        (field (name "BOM_Manufacturer Part") "CBG321609U600T")
        (field (name "BOM_Supplier Part") "C1020")
      )
      (libsource (lib "") (part "MLB3216-601(f)_21"))
    )
    (comp (ref "FB311C")
      (value "60Ω")
      (fields
        (field (name "BOM_Manufacturer Part") "CBG321609U600T")
        (field (name "BOM_Supplier Part") "C1020")
      )
      (libsource (lib "") (part "MLB3216-601(f)_15"))
    )
    (comp (ref "FB311D")
      (value "60Ω")
      (fields
        (field (name "BOM_Manufacturer Part") "CBG321609U600T")
        (field (name "BOM_Supplier Part") "C1020")
      )
      (libsource (lib "") (part "MLB3216-601(f)_25"))
    )
    (comp (ref "FB311E")
      (value "60Ω")
      (fields
        (field (name "BOM_Manufacturer Part") "CBG321609U600T")
        (field (name "BOM_Supplier Part") "C1020")
      )
      (libsource (lib "") (part "MLB3216-601(f)_18"))
    )
    (comp (ref "FB311F")
      (value "60Ω")
      (fields
        (field (name "BOM_Manufacturer Part") "CBG321609U600T")
        (field (name "BOM_Supplier Part") "C1020")
      )
      (libsource (lib "") (part "MLB3216-601(f)_13"))
    )
    (comp (ref "FB311G")
      (value "60Ω")
      (fields
        (field (name "BOM_Manufacturer Part") "CBG321609U600T")
        (field (name "BOM_Supplier Part") "C1020")
      )
      (libsource (lib "") (part "MLB3216-601(f)_35"))
    )
    (comp (ref "FB311H")
      (value "60Ω")
      (fields
        (field (name "BOM_Manufacturer Part") "CBG321609U600T")
        (field (name "BOM_Supplier Part") "C1020")
      )
      (libsource (lib "") (part "MLB3216-601(f)_8"))
    )
    (comp (ref "FB311I")
      (value "60Ω")
      (fields
        (field (name "BOM_Manufacturer Part") "CBG321609U600T")
        (field (name "BOM_Supplier Part") "C1020")
      )
      (libsource (lib "") (part "MLB3216-601(f)_10"))
    )
    (comp (ref "FB311J")
      (value "60Ω")
      (fields
        (field (name "BOM_Manufacturer Part") "CBG321609U600T")
        (field (name "BOM_Supplier Part") "C1020")
      )
      (libsource (lib "") (part "MLB3216-601(f)_30"))
    )
    (comp (ref "FB311K")
      (value "60Ω")
      (fields
        (field (name "BOM_Manufacturer Part") "CBG321609U600T")
        (field (name "BOM_Supplier Part") "C1020")
      )
      (libsource (lib "") (part "MLB3216-601(f)_3"))
    )
    (comp (ref "FB311L")
      (value "60Ω")
      (fields
        (field (name "BOM_Manufacturer Part") "CBG321609U600T")
        (field (name "BOM_Supplier Part") "C1020")
      )
      (libsource (lib "") (part "MLB3216-601(f)_20"))
    )
    (comp (ref "FB311M")
      (value "60Ω")
      (fields
        (field (name "BOM_Manufacturer Part") "CBG321609U600T")
        (field (name "BOM_Supplier Part") "C1020")
      )
      (libsource (lib "") (part "MLB3216-601(f)_2"))
    )
    (comp (ref "FB311N")
      (value "60Ω")
      (fields
        (field (name "BOM_Manufacturer Part") "CBG321609U600T")
        (field (name "BOM_Supplier Part") "C1020")
      )
      (libsource (lib "") (part "MLB3216-601(f)_33"))
    )
    (comp (ref "FB311O")
      (value "60Ω")
      (fields
        (field (name "BOM_Manufacturer Part") "CBG321609U600T")
        (field (name "BOM_Supplier Part") "C1020")
      )
      (libsource (lib "") (part "MLB3216-601(f)_27"))
    )
    (comp (ref "FB311P")
      (value "60Ω")
      (fields
        (field (name "BOM_Manufacturer Part") "CBG321609U600T")
        (field (name "BOM_Supplier Part") "C1020")
      )
      (libsource (lib "") (part "MLB3216-601(f)_14"))
    )
    (comp (ref "FB311Q")
      (value "60Ω")
      (fields
        (field (name "BOM_Manufacturer Part") "CBG321609U600T")
        (field (name "BOM_Supplier Part") "C1020")
      )
      (libsource (lib "") (part "MLB3216-601(f)_7"))
    )
    (comp (ref "FB311R")
      (value "60Ω")
      (fields
        (field (name "BOM_Manufacturer Part") "CBG321609U600T")
        (field (name "BOM_Supplier Part") "C1020")
      )
      (libsource (lib "") (part "MLB3216-601(f)_23"))
    )
    (comp (ref "R212A")
      (value "1K")
      (fields
        (field (name "BOM_Manufacturer Part") "1206W4F1001T5E")
        (field (name "BOM_Supplier Part") "C4410")
      )
      (libsource (lib "") (part "1206W4F1001T5E_3"))
    )
    (comp (ref "R212B")
      (value "1K")
      (fields
        (field (name "BOM_Manufacturer Part") "1206W4F1001T5E")
        (field (name "BOM_Supplier Part") "C4410")
      )
      (libsource (lib "") (part "1206W4F1001T5E_4"))
    )
    (comp (ref "R212C")
      (value "1K")
      (fields
        (field (name "BOM_Manufacturer Part") "1206W4F1001T5E")
        (field (name "BOM_Supplier Part") "C4410")
      )
      (libsource (lib "") (part "1206W4F1001T5E_5"))
    )
    (comp (ref "R212D")
      (value "1K")
      (fields
        (field (name "BOM_Manufacturer Part") "1206W4F1001T5E")
        (field (name "BOM_Supplier Part") "C4410")
      )
      (libsource (lib "") (part "1206W4F1001T5E_7"))
    )
    (comp (ref "R212E")
      (value "1K")
      (fields
        (field (name "BOM_Manufacturer Part") "1206W4F1001T5E")
        (field (name "BOM_Supplier Part") "C4410")
      )
      (libsource (lib "") (part "1206W4F1001T5E"))
    )
    (comp (ref "R212F")
      (value "1K")
      (fields
        (field (name "BOM_Manufacturer Part") "1206W4F1001T5E")
        (field (name "BOM_Supplier Part") "C4410")
      )
      (libsource (lib "") (part "1206W4F1001T5E_6"))
    )
    (comp (ref "R212G")
      (value "1K")
      (fields
        (field (name "BOM_Manufacturer Part") "1206W4F1001T5E")
        (field (name "BOM_Supplier Part") "C4410")
      )
      (libsource (lib "") (part "1206W4F1001T5E_2"))
    )
    (comp (ref "R212H")
      (value "1K")
      (fields
        (field (name "BOM_Manufacturer Part") "1206W4F1001T5E")
        (field (name "BOM_Supplier Part") "C4410")
      )
      (libsource (lib "") (part "1206W4F1001T5E_1"))
    )
    (comp (ref "RP300A")
      (value "220/330 Term")
      (fields
        (field (name "BOM_Manufacturer Part") "4608X-104-331/221L")
        (field (name "BOM_Supplier Part") "652-4608X104331/221L")
      )
      (libsource (lib "") (part "SCSI Terminator sip-8"))
    )
    (comp (ref "RP300B")
      (value "220/330 Term")
      (fields
        (field (name "BOM_Manufacturer Part") "4608X-104-331/221L")
        (field (name "BOM_Supplier Part") "652-4608X104331/221L")
      )
      (libsource (lib "") (part "SCSI Terminator sip-8_1"))
    )
    (comp (ref "RP300C")
      (value "220/330 Term")
      (fields
        (field (name "BOM_Manufacturer Part") "4608X-104-331/221L")
        (field (name "BOM_Supplier Part") "652-4608X104331/221L")
      )
      (libsource (lib "") (part "SCSI Terminator sip-8_2"))
    )
    (comp (ref "SW1")
      (value "DA-08RP")
      (fields (field (name "BOM_Supplier Part") "C129027"))
      (libsource (lib "") (part "DA-08RP"))
    )
    (comp (ref "U213")
      (value "74F244")
      (fields (field (name "BOM_Manufacturer Part") "74F244SCX") (field (name "BOM_Supplier Part") "C5555"))
      (libsource (lib "") (part "74F244SCX"))
    )
    (comp (ref "U310") (value "DS2107S") (libsource (lib "") (part "DS2107S")))
    (comp (ref "U311") (value "DS2107S") (libsource (lib "") (part "DS2107S")))
    (comp (ref "C300A")
      (value "100nF")
      (fields
        (field (name "BOM_Manufacturer Part") "CL31B104KBCNNNC")
        (field (name "BOM_Supplier Part") "C24497")
      )
      (libsource (lib "") (part "CL31B104KBCNNNC_5"))
    )
    (comp (ref "C300B")
      (value "10nF")
      (fields
        (field (name "BOM_Manufacturer Part") "1206B103K500NT")
        (field (name "BOM_Supplier Part") "C1846")
      )
      (libsource (lib "") (part "1206B103K500NT_3"))
    )
    (comp (ref "C300C")
      (value "100nF")
      (fields
        (field (name "BOM_Manufacturer Part") "CL31B104KBCNNNC")
        (field (name "BOM_Supplier Part") "C24497")
      )
      (libsource (lib "") (part "CL31B104KBCNNNC_1"))
    )
    (comp (ref "C300D")
      (value "10nF")
      (fields
        (field (name "BOM_Manufacturer Part") "1206B103K500NT")
        (field (name "BOM_Supplier Part") "C1846")
      )
      (libsource (lib "") (part "1206B103K500NT"))
    )
    (comp (ref "C300E")
      (value "100nF")
      (fields
        (field (name "BOM_Manufacturer Part") "CL31B104KBCNNNC")
        (field (name "BOM_Supplier Part") "C24497")
      )
      (libsource (lib "") (part "CL31B104KBCNNNC_4"))
    )
    (comp (ref "C300F")
      (value "10nF")
      (fields
        (field (name "BOM_Manufacturer Part") "1206B103K500NT")
        (field (name "BOM_Supplier Part") "C1846")
      )
      (libsource (lib "") (part "1206B103K500NT_1"))
    )
    (comp (ref "C300G")
      (value "100nF")
      (fields
        (field (name "BOM_Manufacturer Part") "CL31B104KBCNNNC")
        (field (name "BOM_Supplier Part") "C24497")
      )
      (libsource (lib "") (part "CL31B104KBCNNNC_2"))
    )
    (comp (ref "C300H")
      (value "10nF")
      (fields
        (field (name "BOM_Manufacturer Part") "1206B103K500NT")
        (field (name "BOM_Supplier Part") "C1846")
      )
      (libsource (lib "") (part "1206B103K500NT_4"))
    )
    (comp (ref "C300I")
      (value "100nF")
      (fields
        (field (name "BOM_Manufacturer Part") "CL31B104KBCNNNC")
        (field (name "BOM_Supplier Part") "C24497")
      )
      (libsource (lib "") (part "CL31B104KBCNNNC_3"))
    )
    (comp (ref "C301A")
      (value "10nF")
      (fields
        (field (name "BOM_Manufacturer Part") "1206B103K500NT")
        (field (name "BOM_Supplier Part") "C1846")
      )
      (libsource (lib "") (part "1206B103K500NT_2"))
    )
    (comp (ref "C302A")
      (value "100nF")
      (fields
        (field (name "BOM_Manufacturer Part") "CL31B104KBCNNNC")
        (field (name "BOM_Supplier Part") "C24497")
      )
      (libsource (lib "") (part "CL31B104KBCNNNC"))
    )
    (comp (ref "CN308")
      (value "TO-MB")
      (fields
        (field (name "BOM_Manufacturer Part") "Header2.54mm 1*3P")
        (field (name "BOM_Supplier Part") "C49257")
      )
      (libsource (lib "") (part "Header-Male-2.54_1x3"))
    )
    (comp (ref "CN351")
      (value "TO-LED")
      (fields
        (field (name "BOM_Manufacturer Part") "Header2.54mm 1*3P")
        (field (name "BOM_Supplier Part") "C49257")
      )
      (libsource (lib "") (part "Header-Male-2.54_1x3"))
    )
    (comp (ref "FB502")
      (value "60Ω")
      (fields
        (field (name "BOM_Manufacturer Part") "CBG321609U600T")
        (field (name "BOM_Supplier Part") "C1020")
      )
      (libsource (lib "") (part "MLB3216-601(f)"))
    )
    (comp (ref "FB503")
      (value "60Ω")
      (fields
        (field (name "BOM_Manufacturer Part") "CBG321609U600T")
        (field (name "BOM_Supplier Part") "C1020")
      )
      (libsource (lib "") (part "MLB3216-601(f)_1"))
    )
    (comp (ref "FB506")
      (value "60Ω")
      (fields
        (field (name "BOM_Manufacturer Part") "CBG321609U600T")
        (field (name "BOM_Supplier Part") "C1020")
      )
      (libsource (lib "") (part "MLB3216-601(f)"))
    )
    (comp (ref "J100")
      (value "ESIZE")
      (fields
        (field (name "BOM_Manufacturer Part") "Header2.54mm 1*3P")
        (field (name "BOM_Supplier Part") "C49257")
      )
      (libsource (lib "") (part "Header-Male-2.54_1x3_1"))
    )
    (comp (ref "R300A")
      (value "1K")
      (fields
        (field (name "BOM_Manufacturer Part") "1206W4F1001T5E")
        (field (name "BOM_Supplier Part") "C4410")
      )
      (libsource (lib "") (part "1206W4F1001T5E_5"))
    )
    (comp (ref "R300B")
      (value "1K")
      (fields
        (field (name "BOM_Manufacturer Part") "1206W4F1001T5E")
        (field (name "BOM_Supplier Part") "C4410")
      )
      (libsource (lib "") (part "1206W4F1001T5E_16"))
    )
    (comp (ref "R300C")
      (value "1K")
      (fields
        (field (name "BOM_Manufacturer Part") "1206W4F1001T5E")
        (field (name "BOM_Supplier Part") "C4410")
      )
      (libsource (lib "") (part "1206W4F1001T5E_14"))
    )
    (comp (ref "R300D")
      (value "1K")
      (fields
        (field (name "BOM_Manufacturer Part") "1206W4F1001T5E")
        (field (name "BOM_Supplier Part") "C4410")
      )
      (libsource (lib "") (part "1206W4F1001T5E_8"))
    )
    (comp (ref "R300E")
      (value "1K")
      (fields
        (field (name "BOM_Manufacturer Part") "1206W4F1001T5E")
        (field (name "BOM_Supplier Part") "C4410")
      )
      (libsource (lib "") (part "1206W4F1001T5E_17"))
    )
    (comp (ref "R300F")
      (value "1K")
      (fields
        (field (name "BOM_Manufacturer Part") "1206W4F1001T5E")
        (field (name "BOM_Supplier Part") "C4410")
      )
      (libsource (lib "") (part "1206W4F1001T5E_4"))
    )
    (comp (ref "R300G")
      (value "1K")
      (fields
        (field (name "BOM_Manufacturer Part") "1206W4F1001T5E")
        (field (name "BOM_Supplier Part") "C4410")
      )
      (libsource (lib "") (part "1206W4F1001T5E_1"))
    )
    (comp (ref "R300H")
      (value "1K")
      (fields
        (field (name "BOM_Manufacturer Part") "1206W4F1001T5E")
        (field (name "BOM_Supplier Part") "C4410")
      )
      (libsource (lib "") (part "1206W4F1001T5E_12"))
    )
    (comp (ref "R300I")
      (value "1K")
      (fields
        (field (name "BOM_Manufacturer Part") "1206W4F1001T5E")
        (field (name "BOM_Supplier Part") "C4410")
      )
      (libsource (lib "") (part "1206W4F1001T5E_9"))
    )
    (comp (ref "R300J")
      (value "1K")
      (fields
        (field (name "BOM_Manufacturer Part") "1206W4F1001T5E")
        (field (name "BOM_Supplier Part") "C4410")
      )
      (libsource (lib "") (part "1206W4F1001T5E"))
    )
    (comp (ref "R300K")
      (value "1K")
      (fields
        (field (name "BOM_Manufacturer Part") "1206W4F1001T5E")
        (field (name "BOM_Supplier Part") "C4410")
      )
      (libsource (lib "") (part "1206W4F1001T5E_10"))
    )
    (comp (ref "R300L")
      (value "1K")
      (fields
        (field (name "BOM_Manufacturer Part") "1206W4F1001T5E")
        (field (name "BOM_Supplier Part") "C4410")
      )
      (libsource (lib "") (part "1206W4F1001T5E_2"))
    )
    (comp (ref "R300M")
      (value "1K")
      (fields
        (field (name "BOM_Manufacturer Part") "1206W4F1001T5E")
        (field (name "BOM_Supplier Part") "C4410")
      )
      (libsource (lib "") (part "1206W4F1001T5E_7"))
    )
    (comp (ref "R300N")
      (value "1K")
      (fields
        (field (name "BOM_Manufacturer Part") "1206W4F1001T5E")
        (field (name "BOM_Supplier Part") "C4410")
      )
      (libsource (lib "") (part "1206W4F1001T5E_13"))
    )
    (comp (ref "R300O")
      (value "1K")
      (fields
        (field (name "BOM_Manufacturer Part") "1206W4F1001T5E")
        (field (name "BOM_Supplier Part") "C4410")
      )
      (libsource (lib "") (part "1206W4F1001T5E_15"))
    )
    (comp (ref "R300P")
      (value "1K")
      (fields
        (field (name "BOM_Manufacturer Part") "1206W4F1001T5E")
        (field (name "BOM_Supplier Part") "C4410")
      )
      (libsource (lib "") (part "1206W4F1001T5E_11"))
    )
    (comp (ref "R301A")
      (value "22")
      (fields
        (field (name "BOM_Manufacturer Part") "1206W4F220JT5E")
        (field (name "BOM_Supplier Part") "C17958")
      )
      (libsource (lib "") (part "RS-06K22R0FT_1"))
    )
    (comp (ref "R302A")
      (value "22")
      (fields
        (field (name "BOM_Manufacturer Part") "1206W4F220JT5E")
        (field (name "BOM_Supplier Part") "C17958")
      )
      (libsource (lib "") (part "RS-06K22R0FT"))
    )
    (comp (ref "R302B")
      (value "22")
      (fields
        (field (name "BOM_Manufacturer Part") "1206W4F220JT5E")
        (field (name "BOM_Supplier Part") "C17958")
      )
      (libsource (lib "") (part "RS-06K22R0FT_2"))
    )
    (comp (ref "R307A")
      (value "1K")
      (fields
        (field (name "BOM_Manufacturer Part") "1206W4F1001T5E")
        (field (name "BOM_Supplier Part") "C4410")
      )
      (libsource (lib "") (part "1206W4F1001T5E_3"))
    )
    (comp (ref "R307B")
      (value "1K")
      (fields
        (field (name "BOM_Manufacturer Part") "1206W4F1001T5E")
        (field (name "BOM_Supplier Part") "C4410")
      )
      (libsource (lib "") (part "1206W4F1001T5E_6"))
    )
    (comp (ref "R398")
      (value "120")
      (fields
        (field (name "BOM_Manufacturer Part") "1206W4F1200T5E")
        (field (name "BOM_Supplier Part") "C17909")
      )
      (libsource (lib "") (part "RTT061200FTP"))
    )
    (comp (ref "U206")
      (value "27c256")
      (fields
        (field (name "BOM_Manufacturer Part") "IC254V-12-28-0743-P1524")
        (field (name "BOM_Supplier Part") "C2874016")
      )
      (libsource (lib "") (part "27c256"))
    )
    (comp (ref "U300") (value "NCR53C710") (libsource (lib "") (part "NCR53C710")))
    (comp (ref "U301")
      (value "Abracon 50MHz AC0 D.9403")
      (fields
        (field (name "BOM_Manufacturer Part") "MXO45T-3C-50M000000")
        (field (name "BOM_Supplier Part") "C1138655")
      )
      (libsource (lib "") (part "Osc"))
    )
    (comp (ref "U302")
      (value "74F74")
      (fields (field (name "BOM_Manufacturer Part") "74F74D") (field (name "BOM_Supplier Part") "C5573"))
      (libsource (lib "") (part "74F74D"))
    )
    (comp (ref "FB500")
      (value "60Ω")
      (fields
        (field (name "BOM_Manufacturer Part") "CBG321609U600T")
        (field (name "BOM_Supplier Part") "C1020")
      )
      (libsource (lib "") (part "MLB3216-601(f)_1"))
    )
    (comp (ref "FB501")
      (value "60Ω")
      (fields
        (field (name "BOM_Manufacturer Part") "CBG321609U600T")
        (field (name "BOM_Supplier Part") "C1020")
      )
      (libsource (lib "") (part "MLB3216-601(f)"))
    )
    (comp (ref "FB504")
      (value "60Ω")
      (fields
        (field (name "BOM_Manufacturer Part") "CBG321609U600T")
        (field (name "BOM_Supplier Part") "C1020")
      )
      (libsource (lib "") (part "MLB3216-601(f)"))
    )
    (comp (ref "FB505")
      (value "60Ω")
      (fields
        (field (name "BOM_Manufacturer Part") "CBG321609U600T")
        (field (name "BOM_Supplier Part") "C1020")
      )
      (libsource (lib "") (part "MLB3216-601(f)"))
    )
    (comp (ref "U202")
      (value "GAL22V10H-15")
      (fields (field (name "BOM_Manufacturer Part") "GAL220V10"))
      (libsource (lib "") (part "GAL22V10"))
    )
    (comp (ref "U203")
      (value "GAL22V10H-15")
      (fields (field (name "BOM_Manufacturer Part") "GAL220V10"))
      (libsource (lib "") (part "GAL22V10"))
    )
    (comp (ref "U205")
      (value "GAL22V10H-15")
      (fields (field (name "BOM_Manufacturer Part") "GAL220V10"))
      (libsource (lib "") (part "GAL22V10"))
    )
    (comp (ref "U207")
      (value "GAL22V10H-15")
      (fields (field (name "BOM_Manufacturer Part") "GAL220V10"))
      (libsource (lib "") (part "GAL22V10"))
    )
    (comp (ref "U303")
      (value "GAL22V10H-15")
      (fields (field (name "BOM_Manufacturer Part") "GAL220V10"))
      (libsource (lib "") (part "GAL22V10"))
    )
    (comp (ref "U304")
      (value "GAL22V10B-10")
      (fields (field (name "BOM_Manufacturer Part") "GAL220V10"))
      (libsource (lib "") (part "GAL22V10"))
    )
    (comp (ref "U305")
      (value "GAL22V10B-10")
      (fields (field (name "BOM_Manufacturer Part") "GAL220V10"))
      (libsource (lib "") (part "GAL22V10"))
    )
    (comp (ref "U306")
      (value "GAL22V10B-10")
      (fields (field (name "BOM_Manufacturer Part") "GAL220V10"))
      (libsource (lib "") (part "GAL22V10"))
    )
    (comp (ref "C1") (value "Zorro III Edge") (libsource (lib "") (part "Zorro III Edge")))
    (comp (ref "C306B")
      (value "10pF")
      (fields
        (field (name "BOM_Manufacturer Part") "CL21C100JBANNNC")
        (field (name "BOM_Supplier Part") "C1785")
      )
      (libsource (lib "") (part "CL21C100JBANNNC"))
    )
    (comp (ref "FB507")
      (value "60Ω")
      (fields
        (field (name "BOM_Manufacturer Part") "CBG321609U600T")
        (field (name "BOM_Supplier Part") "C1020")
      )
      (libsource (lib "") (part "MLB3216-601(f)"))
    )
    (comp (ref "FB508")
      (value "60Ω")
      (fields
        (field (name "BOM_Manufacturer Part") "CBG321609U600T")
        (field (name "BOM_Supplier Part") "C1020")
      )
      (libsource (lib "") (part "MLB3216-601(f)"))
    )
    (comp (ref "R100A")
      (value "1K")
      (fields
        (field (name "BOM_Manufacturer Part") "1206W4F1001T5E")
        (field (name "BOM_Supplier Part") "C4410")
      )
      (libsource (lib "") (part "1206W4F1001T5E_12"))
    )
    (comp (ref "R103A")
      (value "1K")
      (fields
        (field (name "BOM_Manufacturer Part") "1206W4F1001T5E")
        (field (name "BOM_Supplier Part") "C4410")
      )
      (libsource (lib "") (part "1206W4F1001T5E_8"))
    )
    (comp (ref "R103B")
      (value "1K")
      (fields
        (field (name "BOM_Manufacturer Part") "1206W4F1001T5E")
        (field (name "BOM_Supplier Part") "C4410")
      )
      (libsource (lib "") (part "1206W4F1001T5E_2"))
    )
    (comp (ref "R109A")
      (value "1K")
      (fields
        (field (name "BOM_Manufacturer Part") "1206W4F1001T5E")
        (field (name "BOM_Supplier Part") "C4410")
      )
      (libsource (lib "") (part "1206W4F1001T5E"))
    )
    (comp (ref "R109B")
      (value "1K")
      (fields
        (field (name "BOM_Manufacturer Part") "1206W4F1001T5E")
        (field (name "BOM_Supplier Part") "C4410")
      )
      (libsource (lib "") (part "1206W4F1001T5E_15"))
    )
    (comp (ref "R109C")
      (value "1K")
      (fields
        (field (name "BOM_Manufacturer Part") "1206W4F1001T5E")
        (field (name "BOM_Supplier Part") "C4410")
      )
      (libsource (lib "") (part "1206W4F1001T5E_14"))
    )
    (comp (ref "R109D")
      (value "1K")
      (fields
        (field (name "BOM_Manufacturer Part") "1206W4F1001T5E")
        (field (name "BOM_Supplier Part") "C4410")
      )
      (libsource (lib "") (part "1206W4F1001T5E_10"))
    )
    (comp (ref "R109E")
      (value "1K")
      (fields
        (field (name "BOM_Manufacturer Part") "1206W4F1001T5E")
        (field (name "BOM_Supplier Part") "C4410")
      )
      (libsource (lib "") (part "1206W4F1001T5E_16"))
    )
    (comp (ref "R109F")
      (value "1K")
      (fields
        (field (name "BOM_Manufacturer Part") "1206W4F1001T5E")
        (field (name "BOM_Supplier Part") "C4410")
      )
      (libsource (lib "") (part "1206W4F1001T5E_11"))
    )
    (comp (ref "R109G")
      (value "1K")
      (fields
        (field (name "BOM_Manufacturer Part") "1206W4F1001T5E")
        (field (name "BOM_Supplier Part") "C4410")
      )
      (libsource (lib "") (part "1206W4F1001T5E_1"))
    )
    (comp (ref "R109H")
      (value "1K")
      (fields
        (field (name "BOM_Manufacturer Part") "1206W4F1001T5E")
        (field (name "BOM_Supplier Part") "C4410")
      )
      (libsource (lib "") (part "1206W4F1001T5E_7"))
    )
    (comp (ref "R200A")
      (value "1K")
      (fields
        (field (name "BOM_Manufacturer Part") "1206W4F1001T5E")
        (field (name "BOM_Supplier Part") "C4410")
      )
      (libsource (lib "") (part "1206W4F1001T5E_3"))
    )
    (comp (ref "R200B")
      (value "1K")
      (fields
        (field (name "BOM_Manufacturer Part") "1206W4F1001T5E")
        (field (name "BOM_Supplier Part") "C4410")
      )
      (libsource (lib "") (part "1206W4F1001T5E_17"))
    )
    (comp (ref "R200C")
      (value "1K")
      (fields
        (field (name "BOM_Manufacturer Part") "1206W4F1001T5E")
        (field (name "BOM_Supplier Part") "C4410")
      )
      (libsource (lib "") (part "1206W4F1001T5E_18"))
    )
    (comp (ref "R200D")
      (value "1K")
      (fields
        (field (name "BOM_Manufacturer Part") "1206W4F1001T5E")
        (field (name "BOM_Supplier Part") "C4410")
      )
      (libsource (lib "") (part "1206W4F1001T5E_9"))
    )
    (comp (ref "R200E")
      (value "1K")
      (fields
        (field (name "BOM_Manufacturer Part") "1206W4F1001T5E")
        (field (name "BOM_Supplier Part") "C4410")
      )
      (libsource (lib "") (part "1206W4F1001T5E_4"))
    )
    (comp (ref "R200F")
      (value "1K")
      (fields
        (field (name "BOM_Manufacturer Part") "1206W4F1001T5E")
        (field (name "BOM_Supplier Part") "C4410")
      )
      (libsource (lib "") (part "1206W4F1001T5E_5"))
    )
    (comp (ref "R200G")
      (value "1K")
      (fields
        (field (name "BOM_Manufacturer Part") "1206W4F1001T5E")
        (field (name "BOM_Supplier Part") "C4410")
      )
      (libsource (lib "") (part "1206W4F1001T5E_6"))
    )
    (comp (ref "R200H")
      (value "1K")
      (fields
        (field (name "BOM_Manufacturer Part") "1206W4F1001T5E")
        (field (name "BOM_Supplier Part") "C4410")
      )
      (libsource (lib "") (part "1206W4F1001T5E_13"))
    )
    (comp (ref "U100")
      (value "74FCT543TSO")
      (fields (field (name "BOM_Manufacturer Part") "CY74FCT543TSOC"))
      (libsource (lib "") (part "74FCT543TSO"))
    )
    (comp (ref "U101")
      (value "74FCT543TSO")
      (fields (field (name "BOM_Manufacturer Part") "CY74FCT543TSOC"))
      (libsource (lib "") (part "74FCT543TSO"))
    )
    (comp (ref "U102")
      (value "74FCT543TSO")
      (fields (field (name "BOM_Manufacturer Part") "CY74FCT543TSOC"))
      (libsource (lib "") (part "74FCT543TSO"))
    )
    (comp (ref "U103")
      (value "74F245")
      (fields (field (name "BOM_Manufacturer Part") "74F245D") (field (name "BOM_Supplier Part") "C5557"))
      (libsource (lib "") (part "74F245D"))
    )
    (comp (ref "U105")
      (value "74FCT543TSO")
      (fields (field (name "BOM_Manufacturer Part") "CY74FCT543TSOC"))
      (libsource (lib "") (part "74FCT543TSO"))
    )
    (comp (ref "U106")
      (value "74FCT543TSO")
      (fields (field (name "BOM_Manufacturer Part") "CY74FCT543TSOC"))
      (libsource (lib "") (part "74FCT543TSO"))
    )
    (comp (ref "U107")
      (value "74FCT543TSO")
      (fields (field (name "BOM_Manufacturer Part") "CY74FCT543TSOC"))
      (libsource (lib "") (part "74FCT543TSO"))
    )
    (comp (ref "U108")
      (value "74FCT543TSO")
      (fields (field (name "BOM_Manufacturer Part") "CY74FCT543TSOC"))
      (libsource (lib "") (part "74FCT543TSO"))
    )
    (comp (ref "U109")
      (value "74F245")
      (fields (field (name "BOM_Manufacturer Part") "74F245D") (field (name "BOM_Supplier Part") "C5557"))
      (libsource (lib "") (part "74F245D"))
    )
    (comp (ref "U200")
      (value "74FCT374TSO")
      (fields (field (name "BOM_Manufacturer Part") "74F374D") (field (name "BOM_Supplier Part") "C5564"))
      (libsource (lib "") (part "74F374D"))
    )
    (comp (ref "U201")
      (value "74FCT521TSO")
      (fields
        (field (name "BOM_Manufacturer Part") "74FCT521CTSOG8")
        (field (name "BOM_Supplier Part") "972-74FCT521CTSOG8")
      )
      (libsource (lib "") (part "74FCT521TSO"))
    )
    (comp (ref "U204")
      (value "74FCT374TSO")
      (fields (field (name "BOM_Manufacturer Part") "74F374D") (field (name "BOM_Supplier Part") "C5564"))
      (libsource (lib "") (part "74F374D"))
    )
    (comp (ref "U307")
      (value "7407")
      (fields (field (name "BOM_Manufacturer Part") "SN7407DR") (field (name "BOM_Supplier Part") "C40481"))
      (libsource (lib "") (part "SN7407DR"))
    )
    (comp (ref "C1A")
      (value "100nF")
      (fields
        (field (name "BOM_Manufacturer Part") "CL31B104KBCNNNC")
        (field (name "BOM_Supplier Part") "C24497")
      )
      (libsource (lib "") (part "CL31B104KBCNNNC_9"))
    )
    (comp (ref "C1B")
      (value "47uF")
      (fields
        (field (name "BOM_Manufacturer Part") "RVT1V470M0605")
        (field (name "BOM_Supplier Part") "C3344")
      )
      (libsource (lib "") (part "RVT1V470M0605_1"))
    )
    (comp (ref "C1C")
      (value "47uF")
      (fields
        (field (name "BOM_Manufacturer Part") "RVT1V470M0605")
        (field (name "BOM_Supplier Part") "C3344")
      )
      (libsource (lib "") (part "RVT1V470M0605_3"))
    )
    (comp (ref "C10")
      (value "47uF")
      (fields
        (field (name "BOM_Manufacturer Part") "RVT1V470M0605")
        (field (name "BOM_Supplier Part") "C3344")
      )
      (libsource (lib "") (part "RVT1V470M0605"))
    )
    (comp (ref "C11")
      (value "47uF")
      (fields
        (field (name "BOM_Manufacturer Part") "RVT1V470M0605")
        (field (name "BOM_Supplier Part") "C3344")
      )
      (libsource (lib "") (part "RVT1V470M0605"))
    )
    (comp (ref "C12")
      (value "47uF")
      (fields
        (field (name "BOM_Manufacturer Part") "RVT1V470M0605")
        (field (name "BOM_Supplier Part") "C3344")
      )
      (libsource (lib "") (part "RVT1V470M0605"))
    )
    (comp (ref "C13")
      (value "47uF")
      (fields
        (field (name "BOM_Manufacturer Part") "RVT1V470M0605")
        (field (name "BOM_Supplier Part") "C3344")
      )
      (libsource (lib "") (part "RVT1V470M0605_2"))
    )
    (comp (ref "C100A")
      (value "100nF")
      (fields
        (field (name "BOM_Manufacturer Part") "CL31B104KBCNNNC")
        (field (name "BOM_Supplier Part") "C24497")
      )
      (libsource (lib "") (part "CL31B104KBCNNNC_3"))
    )
    (comp (ref "C101A")
      (value "100nF")
      (fields
        (field (name "BOM_Manufacturer Part") "CL31B104KBCNNNC")
        (field (name "BOM_Supplier Part") "C24497")
      )
      (libsource (lib "") (part "CL31B104KBCNNNC_4"))
    )
    (comp (ref "C102A")
      (value "100nF")
      (fields
        (field (name "BOM_Manufacturer Part") "CL31B104KBCNNNC")
        (field (name "BOM_Supplier Part") "C24497")
      )
      (libsource (lib "") (part "CL31B104KBCNNNC_2"))
    )
    (comp (ref "C103A")
      (value "100nF")
      (fields
        (field (name "BOM_Manufacturer Part") "CL31B104KBCNNNC")
        (field (name "BOM_Supplier Part") "C24497")
      )
      (libsource (lib "") (part "CL31B104KBCNNNC_1"))
    )
    (comp (ref "C105A")
      (value "100nF")
      (fields
        (field (name "BOM_Manufacturer Part") "CL31B104KBCNNNC")
        (field (name "BOM_Supplier Part") "C24497")
      )
      (libsource (lib "") (part "CL31B104KBCNNNC_11"))
    )
    (comp (ref "C106A")
      (value "100nF")
      (fields
        (field (name "BOM_Manufacturer Part") "CL31B104KBCNNNC")
        (field (name "BOM_Supplier Part") "C24497")
      )
      (libsource (lib "") (part "CL31B104KBCNNNC_23"))
    )
    (comp (ref "C107A")
      (value "100nF")
      (fields
        (field (name "BOM_Manufacturer Part") "CL31B104KBCNNNC")
        (field (name "BOM_Supplier Part") "C24497")
      )
      (libsource (lib "") (part "CL31B104KBCNNNC"))
    )
    (comp (ref "C108A")
      (value "100nF")
      (fields
        (field (name "BOM_Manufacturer Part") "CL31B104KBCNNNC")
        (field (name "BOM_Supplier Part") "C24497")
      )
      (libsource (lib "") (part "CL31B104KBCNNNC_15"))
    )
    (comp (ref "C109A")
      (value "100nF")
      (fields
        (field (name "BOM_Manufacturer Part") "CL31B104KBCNNNC")
        (field (name "BOM_Supplier Part") "C24497")
      )
      (libsource (lib "") (part "CL31B104KBCNNNC_14"))
    )
    (comp (ref "C200A")
      (value "100nF")
      (fields
        (field (name "BOM_Manufacturer Part") "CL31B104KBCNNNC")
        (field (name "BOM_Supplier Part") "C24497")
      )
      (libsource (lib "") (part "CL31B104KBCNNNC_8"))
    )
    (comp (ref "C201A")
      (value "100nF")
      (fields
        (field (name "BOM_Manufacturer Part") "CL31B104KBCNNNC")
        (field (name "BOM_Supplier Part") "C24497")
      )
      (libsource (lib "") (part "CL31B104KBCNNNC_19"))
    )
    (comp (ref "C202A")
      (value "100nF")
      (fields
        (field (name "BOM_Manufacturer Part") "CL31B104KBCNNNC")
        (field (name "BOM_Supplier Part") "C24497")
      )
      (libsource (lib "") (part "CL31B104KBCNNNC_13"))
    )
    (comp (ref "C203A")
      (value "100nF")
      (fields
        (field (name "BOM_Manufacturer Part") "CL31B104KBCNNNC")
        (field (name "BOM_Supplier Part") "C24497")
      )
      (libsource (lib "") (part "CL31B104KBCNNNC_16"))
    )
    (comp (ref "C204A")
      (value "100nF")
      (fields
        (field (name "BOM_Manufacturer Part") "CL31B104KBCNNNC")
        (field (name "BOM_Supplier Part") "C24497")
      )
      (libsource (lib "") (part "CL31B104KBCNNNC_20"))
    )
    (comp (ref "C205A")
      (value "100nF")
      (fields
        (field (name "BOM_Manufacturer Part") "CL31B104KBCNNNC")
        (field (name "BOM_Supplier Part") "C24497")
      )
      (libsource (lib "") (part "CL31B104KBCNNNC_10"))
    )
    (comp (ref "C206A")
      (value "100nF")
      (fields
        (field (name "BOM_Manufacturer Part") "CL31B104KBCNNNC")
        (field (name "BOM_Supplier Part") "C24497")
      )
      (libsource (lib "") (part "CL31B104KBCNNNC_17"))
    )
    (comp (ref "C207A")
      (value "100nF")
      (fields
        (field (name "BOM_Manufacturer Part") "CL31B104KBCNNNC")
        (field (name "BOM_Supplier Part") "C24497")
      )
      (libsource (lib "") (part "CL31B104KBCNNNC_22"))
    )
    (comp (ref "C212A")
      (value "100nF")
      (fields
        (field (name "BOM_Manufacturer Part") "CL31B104KBCNNNC")
        (field (name "BOM_Supplier Part") "C24497")
      )
      (libsource (lib "") (part "CL31B104KBCNNNC_6"))
    )
    (comp (ref "C303A")
      (value "100nF")
      (fields
        (field (name "BOM_Manufacturer Part") "CL31B104KBCNNNC")
        (field (name "BOM_Supplier Part") "C24497")
      )
      (libsource (lib "") (part "CL31B104KBCNNNC_5"))
    )
    (comp (ref "C304A")
      (value "100nF")
      (fields
        (field (name "BOM_Manufacturer Part") "CL31B104KBCNNNC")
        (field (name "BOM_Supplier Part") "C24497")
      )
      (libsource (lib "") (part "CL31B104KBCNNNC_7"))
    )
    (comp (ref "C305A")
      (value "100nF")
      (fields
        (field (name "BOM_Manufacturer Part") "CL31B104KBCNNNC")
        (field (name "BOM_Supplier Part") "C24497")
      )
      (libsource (lib "") (part "CL31B104KBCNNNC_12"))
    )
    (comp (ref "C306A")
      (value "100nF")
      (fields
        (field (name "BOM_Manufacturer Part") "CL31B104KBCNNNC")
        (field (name "BOM_Supplier Part") "C24497")
      )
      (libsource (lib "") (part "CL31B104KBCNNNC_21"))
    )
    (comp (ref "C307A")
      (value "100nF")
      (fields
        (field (name "BOM_Manufacturer Part") "CL31B104KBCNNNC")
        (field (name "BOM_Supplier Part") "C24497")
      )
      (libsource (lib "") (part "CL31B104KBCNNNC_18"))
    )
    (comp (ref "CN2")
      (value "TE-350211-1")
      (fields
        (field (name "BOM_Manufacturer Part") "350211-1")
        (field (name "BOM_Supplier Part") "AN1212-ND")
      )
      (libsource (lib "") (part "TE-350211-1-Simple"))
    )
    (comp (ref "CN3")
      (value "TE 171826-4")
      (fields
        (field (name "BOM_Manufacturer Part") "171826-4")
        (field (name "BOM_Supplier Part") "A112643-ND")
      )
      (libsource (lib "") (part "FLOPPY PWR TE 171826-4"))
    )
    (comp (ref "CN4")
      (value "Fan")
      (fields
        (field (name "BOM_Manufacturer Part") "KF2510-3AGW")
        (field (name "BOM_Supplier Part") "C722745")
      )
      (libsource (lib "") (part "KF2510-3AGW_C722745"))
    )
    (comp (ref "D309A")
      (value "TMBYV10")
      (fields
        (field (name "BOM_Manufacturer Part") "TMBYV10-40FILM")
        (field (name "BOM_Supplier Part") "C283270")
      )
      (libsource (lib "") (part "LL4007G L0"))
    )
    (comp (ref "F309A")
      (value "TH Polyfuse 1.85A")
      (fields (field (name "BOM_Manufacturer Part") "A72-185") (field (name "BOM_Supplier Part") "C135432"))
      (libsource (lib "") (part "A72-185 POLYFUSE"))
    )
    (comp (ref "F309B")
      (value "SMD Polyfuse 1.85A")
      (fields
        (field (name "BOM_Manufacturer Part") "SMD2920B185TF")
        (field (name "BOM_Supplier Part") "C269182")
      )
      (libsource (lib "") (part "A72-185-POLYFUSE-SMD"))
    )
    (comp (ref "FID1")
      (value "FIDUCIAL_SQUARE_DOT_128_100")
      (libsource (lib "") (part "FIDUCIAL_SQUARE_DOT_128_100"))
    )
    (comp (ref "FID2")
      (value "FIDUCIAL_SQUARE_DOT_128_100")
      (libsource (lib "") (part "FIDUCIAL_SQUARE_DOT_128_100"))
    )
    (comp (ref "FID3")
      (value "FIDUCIAL_SQUARE_DOT_128_100")
      (libsource (lib "") (part "FIDUCIAL_SQUARE_DOT_128_100"))
    )
    (comp (ref "FID4")
      (value "FIDUCIAL_SQUARE_DOT_128_100")
      (libsource (lib "") (part "FIDUCIAL_SQUARE_DOT_128_100"))
    )
    (comp (ref "FID5")
      (value "FIDUCIAL_SQUARE_DOT_128_100")
      (libsource (lib "") (part "FIDUCIAL_SQUARE_DOT_128_100"))
    )
    (comp (ref "FID6")
      (value "FIDUCIAL_SQUARE_DOT_128_100")
      (libsource (lib "") (part "FIDUCIAL_SQUARE_DOT_128_100"))
    )
    (comp (ref "MB1") (value "Mousebites") (libsource (lib "") (part "Mousebites")))
    (comp (ref "MB2") (value "Mousebites") (libsource (lib "") (part "Mousebites")))
    (comp (ref "MH1")
      (value "MOUNTINGHOLE_4MM")
      (fields (field (name "BOM_Manufacturer Part") "Mounting hole"))
      (libsource (lib "") (part "MOUNTINGHOLE_4MM"))
    )
    (comp (ref "MH2")
      (value "MOUNTINGHOLE_4MM")
      (fields (field (name "BOM_Manufacturer Part") "Mounting hole"))
      (libsource (lib "") (part "MOUNTINGHOLE_4MM"))
    )
    (comp (ref "MH3")
      (value "MOUNTINGHOLE_4MM")
      (fields (field (name "BOM_Manufacturer Part") "Mounting hole"))
      (libsource (lib "") (part "MOUNTINGHOLE_4MM"))
    )
    (comp (ref "MH4")
      (value "MOUNTINGHOLE_4MM")
      (fields (field (name "BOM_Manufacturer Part") "Mounting hole"))
      (libsource (lib "") (part "MOUNTINGHOLE_4MM"))
    )
    (comp (ref "MK5") (value "Mounting_Hole") (libsource (lib "") (part "Mounting_Hole")))
    (comp (ref "MK6") (value "Mounting_Hole") (libsource (lib "") (part "Mounting_Hole")))
    (comp (ref "MK7") (value "Mounting_Hole") (libsource (lib "") (part "Mounting_Hole")))
    (comp (ref "C400A")
      (value "4.7uF")
      (fields
        (field (name "BOM_Manufacturer Part") "UWX1E4R7MCL1GB")
        (field (name "BOM_Supplier Part") "C445042")
      )
      (libsource (lib "") (part "VZH4R7M1HTR-0406_1"))
    )
    (comp (ref "C400B")
      (value "100nF")
      (fields
        (field (name "BOM_Manufacturer Part") "CL31B104KBCNNNC")
        (field (name "BOM_Supplier Part") "C24497")
      )
      (libsource (lib "") (part "CL31B104KBCNNNC_2"))
    )
    (comp (ref "C401A")
      (value "4.7uF")
      (fields
        (field (name "BOM_Manufacturer Part") "UWX1E4R7MCL1GB")
        (field (name "BOM_Supplier Part") "C445042")
      )
      (libsource (lib "") (part "VZH4R7M1HTR-0406_2"))
    )
    (comp (ref "C401B")
      (value "100nF")
      (fields
        (field (name "BOM_Manufacturer Part") "CL31B104KBCNNNC")
        (field (name "BOM_Supplier Part") "C24497")
      )
      (libsource (lib "") (part "CL31B104KBCNNNC_1"))
    )
    (comp (ref "C402")
      (value "100nF")
      (fields
        (field (name "BOM_Manufacturer Part") "CL31B104KBCNNNC")
        (field (name "BOM_Supplier Part") "C24497")
      )
      (libsource (lib "") (part "CL31B104KBCNNNC"))
    )
    (comp (ref "C403")
      (value "4.7uF")
      (fields
        (field (name "BOM_Manufacturer Part") "UWX1E4R7MCL1GB")
        (field (name "BOM_Supplier Part") "C445042")
      )
      (libsource (lib "") (part "VZH4R7M1HTR-0406"))
    )
    (comp (ref "CN400")
      (value "IDC-M-Right")
      (fields
        (field (name "BOM_Manufacturer Part") "Z-231012050106")
        (field (name "BOM_Supplier Part") "C221060")
      )
      (libsource (lib "") (part "Z-231012050106"))
    )
    (comp (ref "FID7")
      (value "FIDUCIAL_SQUARE_DOT_128_100")
      (libsource (lib "") (part "FIDUCIAL_SQUARE_DOT_128_100"))
    )
    (comp (ref "FID8")
      (value "FIDUCIAL_SQUARE_DOT_128_100")
      (libsource (lib "") (part "FIDUCIAL_SQUARE_DOT_128_100"))
    )
    (comp (ref "MK1") (value "Mounting_Hole") (libsource (lib "") (part "Mounting_Hole")))
    (comp (ref "MK2") (value "Mounting_Hole") (libsource (lib "") (part "Mounting_Hole")))
    (comp (ref "U400") (value "DS2107S") (libsource (lib "") (part "DS2107S")))
    (comp (ref "U401") (value "DS2107S") (libsource (lib "") (part "DS2107S")))
  )
  (nets
    (net (code "1") (name "A0") (class "Default")
      (node (ref "R300K") (pin "1") (pinfunction "1_1") (pintype "input"))
      (node (ref "U300") (pin "144") (pinfunction "A0_144") (pintype "unspecified"))
      (node (ref "U304") (pin "26") (pinfunction "IOQ_26") (pintype "unspecified"))
      (node (ref "U305") (pin "16") (pinfunction "I_16") (pintype "unspecified"))
    )
    (net (code "2") (name "A1") (class "Default")
      (node (ref "R300L") (pin "1") (pinfunction "1_1") (pintype "input"))
      (node (ref "U300") (pin "145") (pinfunction "A1_145") (pintype "unspecified"))
      (node (ref "U304") (pin "27") (pinfunction "IOQ_27") (pintype "unspecified"))
      (node (ref "U305") (pin "13") (pinfunction "I_13") (pintype "unspecified"))
    )
    (net (code "3") (name "A2") (class "Default")
      (node (ref "R300I") (pin "1") (pinfunction "1_1") (pintype "input"))
      (node (ref "U103") (pin "7") (pinfunction "A5_7") (pintype "unspecified"))
      (node (ref "U202") (pin "7") (pinfunction "I_7") (pintype "unspecified"))
      (node (ref "U206") (pin "10") (pinfunction "A0_10") (pintype "input"))
      (node (ref "U300") (pin "146") (pinfunction "A2_146") (pintype "unspecified"))
    )
    (net (code "4") (name "A3") (class "Default")
      (node (ref "R300J") (pin "1") (pinfunction "1_1") (pintype "input"))
      (node (ref "U103") (pin "6") (pinfunction "A4_6") (pintype "unspecified"))
      (node (ref "U202") (pin "6") (pinfunction "I_6") (pintype "unspecified"))
      (node (ref "U206") (pin "9") (pinfunction "A1_9") (pintype "input"))
      (node (ref "U300") (pin "147") (pinfunction "A3_147") (pintype "unspecified"))
    )
    (net (code "5") (name "A4") (class "Default")
      (node (ref "U103") (pin "5") (pinfunction "A3_5") (pintype "unspecified"))
      (node (ref "U202") (pin "5") (pinfunction "I_5") (pintype "unspecified"))
      (node (ref "U206") (pin "8") (pinfunction "A2_8") (pintype "input"))
      (node (ref "U300") (pin "148") (pinfunction "A4_148") (pintype "unspecified"))
    )
    (net (code "6") (name "A5") (class "Default")
      (node (ref "U103") (pin "4") (pinfunction "A2_4") (pintype "unspecified"))
      (node (ref "U202") (pin "4") (pinfunction "I_4") (pintype "unspecified"))
      (node (ref "U206") (pin "7") (pinfunction "A3_7") (pintype "input"))
      (node (ref "U300") (pin "150") (pinfunction "A5_150") (pintype "unspecified"))
    )
    (net (code "7") (name "A6") (class "Default")
      (node (ref "U103") (pin "3") (pinfunction "A1_3") (pintype "unspecified"))
      (node (ref "U202") (pin "3") (pinfunction "I_3") (pintype "unspecified"))
      (node (ref "U206") (pin "6") (pinfunction "A4_6") (pintype "input"))
      (node (ref "U300") (pin "151") (pinfunction "A6_151") (pintype "unspecified"))
    )
    (net (code "8") (name "A7") (class "Default")
      (node (ref "U103") (pin "2") (pinfunction "A0_2") (pintype "unspecified"))
      (node (ref "U206") (pin "5") (pinfunction "A5_5") (pintype "input"))
      (node (ref "U300") (pin "152") (pinfunction "A7_152") (pintype "unspecified"))
    )
    (net (code "9") (name "A8") (class "Default")
      (node (ref "U102") (pin "10") (pinfunction "A7_10") (pintype "bidirectional"))
      (node (ref "U202") (pin "9") (pinfunction "I_9") (pintype "unspecified"))
      (node (ref "U206") (pin "4") (pinfunction "A6_4") (pintype "input"))
      (node (ref "U300") (pin "154") (pinfunction "A8_154") (pintype "unspecified"))
    )
    (net (code "10") (name "A9") (class "Default")
      (node (ref "U102") (pin "9") (pinfunction "A6_9") (pintype "bidirectional"))
      (node (ref "U206") (pin "3") (pinfunction "A7_3") (pintype "input"))
      (node (ref "U300") (pin "155") (pinfunction "A9_155") (pintype "unspecified"))
    )
    (net (code "11") (name "A10") (class "Default")
      (node (ref "U102") (pin "8") (pinfunction "A5_8") (pintype "bidirectional"))
      (node (ref "U206") (pin "25") (pinfunction "A8_25") (pintype "output"))
      (node (ref "U300") (pin "157") (pinfunction "A10_157") (pintype "unspecified"))
    )
    (net (code "12") (name "A11") (class "Default")
      (node (ref "U102") (pin "7") (pinfunction "A4_7") (pintype "bidirectional"))
      (node (ref "U206") (pin "24") (pinfunction "A9_24") (pintype "output"))
      (node (ref "U300") (pin "158") (pinfunction "A11_158") (pintype "unspecified"))
    )
    (net (code "13") (name "A12") (class "Default")
      (node (ref "U102") (pin "6") (pinfunction "A3_6") (pintype "bidirectional"))
      (node (ref "U206") (pin "21") (pinfunction "A10_21") (pintype "output"))
      (node (ref "U300") (pin "159") (pinfunction "A12_159") (pintype "unspecified"))
    )
    (net (code "14") (name "A13") (class "Default")
      (node (ref "U102") (pin "5") (pinfunction "A2_5") (pintype "bidirectional"))
      (node (ref "U206") (pin "23") (pinfunction "A11_23") (pintype "output"))
      (node (ref "U300") (pin "160") (pinfunction "A13_160") (pintype "unspecified"))
    )
    (net (code "15") (name "A14") (class "Default")
      (node (ref "U102") (pin "4") (pinfunction "A1_4") (pintype "bidirectional"))
      (node (ref "U206") (pin "2") (pinfunction "A12_2") (pintype "input"))
      (node (ref "U300") (pin "1") (pinfunction "A14_1") (pintype "unspecified"))
    )
    (net (code "16") (name "A15") (class "Default")
      (node (ref "U102") (pin "3") (pinfunction "A0_3") (pintype "bidirectional"))
      (node (ref "U206") (pin "26") (pinfunction "A13_26") (pintype "output"))
      (node (ref "U300") (pin "3") (pinfunction "A15_3") (pintype "unspecified"))
    )
    (net (code "17") (name "A16") (class "Default")
      (node (ref "U101") (pin "10") (pinfunction "A7_10") (pintype "bidirectional"))
      (node (ref "U206") (pin "27") (pinfunction "A14_27") (pintype "output"))
      (node (ref "U300") (pin "4") (pinfunction "A16_4") (pintype "unspecified"))
    )
    (net (code "18") (name "A17") (class "Default")
      (node (ref "J100") (pin "3") (pinfunction "3_3") (pintype "input"))
      (node (ref "U101") (pin "9") (pinfunction "A6_9") (pintype "bidirectional"))
      (node (ref "U203") (pin "5") (pinfunction "I_5") (pintype "unspecified"))
      (node (ref "U300") (pin "5") (pinfunction "A17_5") (pintype "unspecified"))
    )
    (net (code "19") (name "A18") (class "Default")
      (node (ref "U101") (pin "8") (pinfunction "A5_8") (pintype "bidirectional"))
      (node (ref "U203") (pin "4") (pinfunction "I_4") (pintype "unspecified"))
      (node (ref "U300") (pin "7") (pinfunction "A18_7") (pintype "unspecified"))
    )
    (net (code "20") (name "A19") (class "Default")
      (node (ref "U101") (pin "7") (pinfunction "A4_7") (pintype "bidirectional"))
      (node (ref "U203") (pin "3") (pinfunction "I_3") (pintype "unspecified"))
      (node (ref "U300") (pin "8") (pinfunction "A19_8") (pintype "unspecified"))
    )
    (net (code "21") (name "A20") (class "Default")
      (node (ref "U101") (pin "6") (pinfunction "A3_6") (pintype "bidirectional"))
      (node (ref "U300") (pin "10") (pinfunction "A20_10") (pintype "unspecified"))
    )
    (net (code "22") (name "A21") (class "Default")
      (node (ref "U101") (pin "5") (pinfunction "A2_5") (pintype "bidirectional"))
      (node (ref "U300") (pin "11") (pinfunction "A21_11") (pintype "unspecified"))
    )
    (net (code "23") (name "A22") (class "Default")
      (node (ref "U101") (pin "4") (pinfunction "A1_4") (pintype "bidirectional"))
      (node (ref "U300") (pin "12") (pinfunction "A22_12") (pintype "unspecified"))
    )
    (net (code "24") (name "A23") (class "Default")
      (node (ref "U101") (pin "3") (pinfunction "A0_3") (pintype "bidirectional"))
      (node (ref "U203") (pin "2") (pinfunction "CLK/I_2") (pintype "unspecified"))
      (node (ref "U300") (pin "13") (pinfunction "A23_13") (pintype "unspecified"))
    )
    (net (code "25") (name "A24") (class "Default")
      (node (ref "U100") (pin "10") (pinfunction "A7_10") (pintype "bidirectional"))
      (node (ref "U201") (pin "17") (pinfunction "A7_17") (pintype "unspecified"))
      (node (ref "U300") (pin "14") (pinfunction "A24_14") (pintype "unspecified"))
    )
    (net (code "26") (name "A25") (class "Default")
      (node (ref "U100") (pin "9") (pinfunction "A6_9") (pintype "bidirectional"))
      (node (ref "U201") (pin "15") (pinfunction "A6_15") (pintype "unspecified"))
      (node (ref "U300") (pin "16") (pinfunction "A25_16") (pintype "unspecified"))
    )
    (net (code "27") (name "A26") (class "Default")
      (node (ref "U100") (pin "8") (pinfunction "A5_8") (pintype "bidirectional"))
      (node (ref "U201") (pin "13") (pinfunction "A5_13") (pintype "unspecified"))
      (node (ref "U300") (pin "17") (pinfunction "A26_17") (pintype "unspecified"))
    )
    (net (code "28") (name "A27") (class "Default")
      (node (ref "U100") (pin "7") (pinfunction "A4_7") (pintype "bidirectional"))
      (node (ref "U201") (pin "11") (pinfunction "A4_11") (pintype "unspecified"))
      (node (ref "U300") (pin "18") (pinfunction "A27_18") (pintype "unspecified"))
    )
    (net (code "29") (name "A28") (class "Default")
      (node (ref "U100") (pin "6") (pinfunction "A3_6") (pintype "bidirectional"))
      (node (ref "U201") (pin "8") (pinfunction "A3_8") (pintype "unspecified"))
      (node (ref "U300") (pin "20") (pinfunction "A28_20") (pintype "unspecified"))
    )
    (net (code "30") (name "A29") (class "Default")
      (node (ref "U100") (pin "5") (pinfunction "A2_5") (pintype "bidirectional"))
      (node (ref "U201") (pin "6") (pinfunction "A2_6") (pintype "unspecified"))
      (node (ref "U300") (pin "21") (pinfunction "A29_21") (pintype "unspecified"))
    )
    (net (code "31") (name "A30") (class "Default")
      (node (ref "U100") (pin "4") (pinfunction "A1_4") (pintype "bidirectional"))
      (node (ref "U201") (pin "4") (pinfunction "A1_4") (pintype "unspecified"))
      (node (ref "U300") (pin "23") (pinfunction "A30_23") (pintype "unspecified"))
    )
    (net (code "32") (name "A31") (class "Default")
      (node (ref "U100") (pin "3") (pinfunction "A0_3") (pintype "bidirectional"))
      (node (ref "U201") (pin "2") (pinfunction "A0_2") (pintype "unspecified"))
      (node (ref "U300") (pin "24") (pinfunction "A31_24") (pintype "unspecified"))
    )
    (net (code "33") (name "ABOEH") (class "Default")
      (node (ref "U100") (pin "13") (pinfunction "OEAB_13") (pintype "unspecified"))
      (node (ref "U100") (pin "2") (pinfunction "OEBA_2") (pintype "unspecified"))
      (node (ref "U101") (pin "13") (pinfunction "OEAB_13") (pintype "unspecified"))
      (node (ref "U101") (pin "2") (pinfunction "OEBA_2") (pintype "unspecified"))
      (node (ref "U102") (pin "13") (pinfunction "OEAB_13") (pintype "unspecified"))
      (node (ref "U102") (pin "2") (pinfunction "OEBA_2") (pintype "unspecified"))
      (node (ref "U205") (pin "27") (pinfunction "IOQ_27") (pintype "unspecified"))
      (node (ref "U306") (pin "10") (pinfunction "I_10") (pintype "unspecified"))
    )
    (net (code "34") (name "ABOEL") (class "Default")
      (node (ref "U103") (pin "19") (pinfunction "OE#_19") (pintype "unspecified"))
      (node (ref "U109") (pin "19") (pinfunction "OE#_19") (pintype "unspecified"))
      (node (ref "U205") (pin "26") (pinfunction "IOQ_26") (pintype "unspecified"))
    )
    (net (code "35") (name "BERR") (class "Default")
      (node (ref "R307B") (pin "2") (pinfunction "2_2") (pintype "input"))
      (node (ref "U202") (pin "17") (pinfunction "IOQ_17") (pintype "unspecified"))
      (node (ref "U300") (pin "37") (pinfunction "BERR/-TEA/_37") (pintype "unspecified"))
      (node (ref "U303") (pin "10") (pinfunction "I_10") (pintype "unspecified"))
      (node (ref "U306") (pin "11") (pinfunction "I_11") (pintype "unspecified"))
      (node (ref "U307") (pin "6") (pinfunction "3Y_6") (pintype "unspecified"))
    )
    (net (code "36") (name "BGACK") (class "Default")
      (node (ref "R300A") (pin "1") (pinfunction "1_1") (pintype "input"))
      (node (ref "U300") (pin "98") (pinfunction "BGACK/-BB/_98") (pintype "unspecified"))
    )
    (net (code "37") (name "BMASTER") (class "Default")
      (node (ref "U100") (pin "23") (pinfunction "CEBA_23") (pintype "unspecified"))
      (node (ref "U101") (pin "23") (pinfunction "CEBA_23") (pintype "unspecified"))
      (node (ref "U102") (pin "23") (pinfunction "CEBA_23") (pintype "unspecified"))
      (node (ref "U103") (pin "1") (pinfunction "T/R#_1") (pintype "unspecified"))
      (node (ref "U109") (pin "1") (pinfunction "T/R#_1") (pintype "unspecified"))
      (node (ref "U303") (pin "27") (pinfunction "IOQ_27") (pintype "unspecified"))
    )
    (net (code "38") (name "CBACK") (class "Default")
      (node (ref "R300B") (pin "2") (pinfunction "2_2") (pintype "input"))
      (node (ref "U300") (pin "35") (pinfunction "CBACK/-TBI/_35") (pintype "unspecified"))
      (node (ref "U306") (pin "27") (pinfunction "IOQ_27") (pintype "unspecified"))
    )
    (net (code "39") (name "CBREQ") (class "Default")
      (node (ref "R300C") (pin "1") (pinfunction "1_1") (pintype "input"))
      (node (ref "U300") (pin "33") (pinfunction "CBREQ/-TT1/_33") (pintype "unspecified"))
      (node (ref "U306") (pin "6") (pinfunction "I_6") (pintype "unspecified"))
    )
    (net (code "40") (name "CLK") (class "Default")
      (node (ref "R302B") (pin "1") (pinfunction "1_1") (pintype "input"))
      (node (ref "U205") (pin "2") (pinfunction "CLK/I_2") (pintype "unspecified"))
      (node (ref "U207") (pin "2") (pinfunction "CLK/I_2") (pintype "unspecified"))
      (node (ref "U300") (pin "41") (pinfunction "BCLK_41") (pintype "unspecified"))
      (node (ref "U303") (pin "12") (pinfunction "I_12") (pintype "unspecified"))
      (node (ref "U305") (pin "2") (pinfunction "CLK/I_2") (pintype "unspecified"))
    )
    (net (code "41") (name "CLKI") (class "Default")
      (node (ref "R302A") (pin "1") (pinfunction "1_1") (pintype "input"))
      (node (ref "U302") (pin "2") (pinfunction "D0_2") (pintype "unspecified"))
      (node (ref "U304") (pin "2") (pinfunction "CLK/I_2") (pintype "unspecified"))
      (node (ref "U306") (pin "2") (pinfunction "CLK/I_2") (pintype "unspecified"))
    )
    (net (code "42") (name "CLK_50M") (class "Default")
      (node (ref "R301A") (pin "1") (pinfunction "1_1") (pintype "input"))
      (node (ref "U300") (pin "102") (pinfunction "SCLK_102") (pintype "unspecified"))
      (node (ref "U302") (pin "3") (pinfunction "CP0_3") (pintype "unspecified"))
    )
    (net (code "43") (name "D0") (class "Default")
      (node (ref "U107") (pin "10") (pinfunction "A7_10") (pintype "bidirectional"))
      (node (ref "U204") (pin "18") (pinfunction "D7_18") (pintype "unspecified"))
      (node (ref "U204") (pin "19") (pinfunction "Q7_19") (pintype "unspecified"))
      (node (ref "U213") (pin "3") (pinfunction "O4_3") (pintype "unspecified"))
      (node (ref "U300") (pin "85") (pinfunction "D0_85") (pintype "unspecified"))
    )
    (net (code "44") (name "D1") (class "Default")
      (node (ref "U107") (pin "9") (pinfunction "A6_9") (pintype "bidirectional"))
      (node (ref "U204") (pin "16") (pinfunction "Q6_16") (pintype "unspecified"))
      (node (ref "U204") (pin "17") (pinfunction "D6_17") (pintype "unspecified"))
      (node (ref "U213") (pin "5") (pinfunction "O5_5") (pintype "unspecified"))
      (node (ref "U300") (pin "84") (pinfunction "D1_84") (pintype "unspecified"))
    )
    (net (code "45") (name "D2") (class "Default")
      (node (ref "U107") (pin "8") (pinfunction "A5_8") (pintype "bidirectional"))
      (node (ref "U204") (pin "14") (pinfunction "D5_14") (pintype "unspecified"))
      (node (ref "U204") (pin "15") (pinfunction "Q5_15") (pintype "unspecified"))
      (node (ref "U213") (pin "7") (pinfunction "O6_7") (pintype "unspecified"))
      (node (ref "U300") (pin "83") (pinfunction "D2_83") (pintype "unspecified"))
    )
    (net (code "46") (name "D2Z") (class "Default")
      (node (ref "U105") (pin "11") (pinfunction "CEAB_11") (pintype "unspecified"))
      (node (ref "U106") (pin "11") (pinfunction "CEAB_11") (pintype "unspecified"))
      (node (ref "U107") (pin "11") (pinfunction "CEAB_11") (pintype "unspecified"))
      (node (ref "U108") (pin "11") (pinfunction "CEAB_11") (pintype "unspecified"))
      (node (ref "U205") (pin "21") (pinfunction "IOQ_21") (pintype "unspecified"))
    )
    (net (code "47") (name "D3") (class "Default")
      (node (ref "U107") (pin "7") (pinfunction "A4_7") (pintype "bidirectional"))
      (node (ref "U204") (pin "12") (pinfunction "Q4_12") (pintype "unspecified"))
      (node (ref "U204") (pin "13") (pinfunction "D4_13") (pintype "unspecified"))
      (node (ref "U213") (pin "9") (pinfunction "O7_9") (pintype "unspecified"))
      (node (ref "U300") (pin "81") (pinfunction "D3_81") (pintype "unspecified"))
    )
    (net (code "48") (name "D4") (class "Default")
      (node (ref "U107") (pin "6") (pinfunction "A3_6") (pintype "bidirectional"))
      (node (ref "U204") (pin "8") (pinfunction "D3_8") (pintype "unspecified"))
      (node (ref "U204") (pin "9") (pinfunction "Q3_9") (pintype "unspecified"))
      (node (ref "U213") (pin "12") (pinfunction "O3_12") (pintype "unspecified"))
      (node (ref "U300") (pin "80") (pinfunction "D4_80") (pintype "unspecified"))
    )
    (net (code "49") (name "D5") (class "Default")
      (node (ref "U107") (pin "5") (pinfunction "A2_5") (pintype "bidirectional"))
      (node (ref "U204") (pin "6") (pinfunction "Q2_6") (pintype "unspecified"))
      (node (ref "U204") (pin "7") (pinfunction "D2_7") (pintype "unspecified"))
      (node (ref "U213") (pin "14") (pinfunction "O2_14") (pintype "unspecified"))
      (node (ref "U300") (pin "78") (pinfunction "D5_78") (pintype "unspecified"))
    )
    (net (code "50") (name "D6") (class "Default")
      (node (ref "U107") (pin "4") (pinfunction "A1_4") (pintype "bidirectional"))
      (node (ref "U204") (pin "4") (pinfunction "D1_4") (pintype "unspecified"))
      (node (ref "U204") (pin "5") (pinfunction "Q1_5") (pintype "unspecified"))
      (node (ref "U213") (pin "16") (pinfunction "O1_16") (pintype "unspecified"))
      (node (ref "U300") (pin "77") (pinfunction "D6_77") (pintype "unspecified"))
    )
    (net (code "51") (name "D7") (class "Default")
      (node (ref "U107") (pin "3") (pinfunction "A0_3") (pintype "bidirectional"))
      (node (ref "U204") (pin "2") (pinfunction "Q0_2") (pintype "unspecified"))
      (node (ref "U204") (pin "3") (pinfunction "D0_3") (pintype "unspecified"))
      (node (ref "U213") (pin "18") (pinfunction "O0_18") (pintype "unspecified"))
      (node (ref "U300") (pin "76") (pinfunction "D7_76") (pintype "unspecified"))
    )
    (net (code "52") (name "D8") (class "Default")
      (node (ref "U106") (pin "10") (pinfunction "A7_10") (pintype "bidirectional"))
      (node (ref "U300") (pin "73") (pinfunction "D8_73") (pintype "unspecified"))
    )
    (net (code "53") (name "D9") (class "Default")
      (node (ref "U106") (pin "9") (pinfunction "A6_9") (pintype "bidirectional"))
      (node (ref "U300") (pin "72") (pinfunction "D9_72") (pintype "unspecified"))
    )
    (net (code "54") (name "D10") (class "Default")
      (node (ref "U106") (pin "8") (pinfunction "A5_8") (pintype "bidirectional"))
      (node (ref "U300") (pin "71") (pinfunction "D10_71") (pintype "unspecified"))
    )
    (net (code "55") (name "D11") (class "Default")
      (node (ref "U106") (pin "7") (pinfunction "A4_7") (pintype "bidirectional"))
      (node (ref "U300") (pin "70") (pinfunction "D11_70") (pintype "unspecified"))
    )
    (net (code "56") (name "D12") (class "Default")
      (node (ref "U106") (pin "6") (pinfunction "A3_6") (pintype "bidirectional"))
      (node (ref "U206") (pin "11") (pinfunction "D0_11") (pintype "input"))
      (node (ref "U300") (pin "68") (pinfunction "D12_68") (pintype "unspecified"))
    )
    (net (code "57") (name "D13") (class "Default")
      (node (ref "U106") (pin "5") (pinfunction "A2_5") (pintype "bidirectional"))
      (node (ref "U206") (pin "12") (pinfunction "D1_12") (pintype "passive"))
      (node (ref "U300") (pin "67") (pinfunction "D13_67") (pintype "unspecified"))
    )
    (net (code "58") (name "D14") (class "Default")
      (node (ref "U106") (pin "4") (pinfunction "A1_4") (pintype "bidirectional"))
      (node (ref "U206") (pin "13") (pinfunction "D2_13") (pintype "input"))
      (node (ref "U300") (pin "66") (pinfunction "D14_66") (pintype "unspecified"))
    )
    (net (code "59") (name "D15") (class "Default")
      (node (ref "U106") (pin "3") (pinfunction "A0_3") (pintype "bidirectional"))
      (node (ref "U206") (pin "15") (pinfunction "D3_15") (pintype "output"))
      (node (ref "U300") (pin "65") (pinfunction "D15_65") (pintype "unspecified"))
    )
    (net (code "60") (name "D16") (class "Default")
      (node (ref "U108") (pin "3") (pinfunction "A0_3") (pintype "bidirectional"))
      (node (ref "U300") (pin "62") (pinfunction "D16_62") (pintype "unspecified"))
    )
    (net (code "61") (name "D17") (class "Default")
      (node (ref "U108") (pin "4") (pinfunction "A1_4") (pintype "bidirectional"))
      (node (ref "U300") (pin "60") (pinfunction "D17_60") (pintype "unspecified"))
    )
    (net (code "62") (name "D18") (class "Default")
      (node (ref "U108") (pin "5") (pinfunction "A2_5") (pintype "bidirectional"))
      (node (ref "U300") (pin "59") (pinfunction "D18_59") (pintype "unspecified"))
    )
    (net (code "63") (name "D19") (class "Default")
      (node (ref "U108") (pin "6") (pinfunction "A3_6") (pintype "bidirectional"))
      (node (ref "U300") (pin "58") (pinfunction "D19_58") (pintype "unspecified"))
    )
    (net (code "64") (name "D20") (class "Default")
      (node (ref "U108") (pin "7") (pinfunction "A4_7") (pintype "bidirectional"))
      (node (ref "U300") (pin "57") (pinfunction "D20_57") (pintype "unspecified"))
    )
    (net (code "65") (name "D21") (class "Default")
      (node (ref "U108") (pin "8") (pinfunction "A5_8") (pintype "bidirectional"))
      (node (ref "U300") (pin "56") (pinfunction "D21_56") (pintype "unspecified"))
    )
    (net (code "66") (name "D22") (class "Default")
      (node (ref "U108") (pin "9") (pinfunction "A6_9") (pintype "bidirectional"))
      (node (ref "U300") (pin "55") (pinfunction "D22_55") (pintype "unspecified"))
    )
    (net (code "67") (name "D23") (class "Default")
      (node (ref "U108") (pin "10") (pinfunction "A7_10") (pintype "bidirectional"))
      (node (ref "U300") (pin "53") (pinfunction "D23_53") (pintype "unspecified"))
    )
    (net (code "68") (name "D24") (class "Default")
      (node (ref "U105") (pin "3") (pinfunction "A0_3") (pintype "bidirectional"))
      (node (ref "U200") (pin "18") (pinfunction "D7_18") (pintype "unspecified"))
      (node (ref "U300") (pin "51") (pinfunction "D24_51") (pintype "unspecified"))
    )
    (net (code "69") (name "D25") (class "Default")
      (node (ref "U105") (pin "4") (pinfunction "A1_4") (pintype "bidirectional"))
      (node (ref "U200") (pin "17") (pinfunction "D6_17") (pintype "unspecified"))
      (node (ref "U300") (pin "50") (pinfunction "D25_50") (pintype "unspecified"))
    )
    (net (code "70") (name "D26") (class "Default")
      (node (ref "U105") (pin "5") (pinfunction "A2_5") (pintype "bidirectional"))
      (node (ref "U200") (pin "14") (pinfunction "D5_14") (pintype "unspecified"))
      (node (ref "U300") (pin "48") (pinfunction "D26_48") (pintype "unspecified"))
    )
    (net (code "71") (name "D27") (class "Default")
      (node (ref "U105") (pin "6") (pinfunction "A3_6") (pintype "bidirectional"))
      (node (ref "U200") (pin "13") (pinfunction "D4_13") (pintype "unspecified"))
      (node (ref "U300") (pin "47") (pinfunction "D27_47") (pintype "unspecified"))
    )
    (net (code "72") (name "D28") (class "Default")
      (node (ref "U105") (pin "7") (pinfunction "A4_7") (pintype "bidirectional"))
      (node (ref "U200") (pin "8") (pinfunction "D3_8") (pintype "unspecified"))
      (node (ref "U206") (pin "16") (pinfunction "D4_16") (pintype "output"))
      (node (ref "U300") (pin "45") (pinfunction "D28_45") (pintype "unspecified"))
    )
    (net (code "73") (name "D29") (class "Default")
      (node (ref "U105") (pin "8") (pinfunction "A5_8") (pintype "bidirectional"))
      (node (ref "U200") (pin "7") (pinfunction "D2_7") (pintype "unspecified"))
      (node (ref "U206") (pin "17") (pinfunction "D5_17") (pintype "output"))
      (node (ref "U300") (pin "44") (pinfunction "D29_44") (pintype "unspecified"))
    )
    (net (code "74") (name "D30") (class "Default")
      (node (ref "U105") (pin "9") (pinfunction "A6_9") (pintype "bidirectional"))
      (node (ref "U200") (pin "4") (pinfunction "D1_4") (pintype "unspecified"))
      (node (ref "U206") (pin "18") (pinfunction "D6_18") (pintype "output"))
      (node (ref "U300") (pin "43") (pinfunction "D30_43") (pintype "unspecified"))
    )
    (net (code "75") (name "D31") (class "Default")
      (node (ref "U105") (pin "10") (pinfunction "A7_10") (pintype "bidirectional"))
      (node (ref "U200") (pin "3") (pinfunction "D0_3") (pintype "unspecified"))
      (node (ref "U206") (pin "19") (pinfunction "D7_19") (pintype "output"))
      (node (ref "U300") (pin "42") (pinfunction "D31_42") (pintype "unspecified"))
    )
    (net (code "76") (name "DBLT") (class "Default")
      (node (ref "U105") (pin "1") (pinfunction "LEBA_1") (pintype "unspecified"))
      (node (ref "U105") (pin "14") (pinfunction "LEAB_14") (pintype "unspecified"))
      (node (ref "U106") (pin "1") (pinfunction "LEBA_1") (pintype "unspecified"))
      (node (ref "U106") (pin "14") (pinfunction "LEAB_14") (pintype "unspecified"))
      (node (ref "U107") (pin "1") (pinfunction "LEBA_1") (pintype "unspecified"))
      (node (ref "U107") (pin "14") (pinfunction "LEAB_14") (pintype "unspecified"))
      (node (ref "U108") (pin "1") (pinfunction "LEBA_1") (pintype "unspecified"))
      (node (ref "U108") (pin "14") (pinfunction "LEAB_14") (pintype "unspecified"))
      (node (ref "U205") (pin "24") (pinfunction "IOQ_24") (pintype "unspecified"))
    )
    (net (code "77") (name "DBOE") (class "Default")
      (node (ref "FB505") (pin "2") (pinfunction "2_2") (pintype "unspecified"))
      (node (ref "U105") (pin "13") (pinfunction "OEAB_13") (pintype "unspecified"))
      (node (ref "U105") (pin "2") (pinfunction "OEBA_2") (pintype "unspecified"))
      (node (ref "U106") (pin "13") (pinfunction "OEAB_13") (pintype "unspecified"))
      (node (ref "U106") (pin "2") (pinfunction "OEBA_2") (pintype "unspecified"))
      (node (ref "U107") (pin "13") (pinfunction "OEAB_13") (pintype "unspecified"))
      (node (ref "U107") (pin "2") (pinfunction "OEBA_2") (pintype "unspecified"))
      (node (ref "U108") (pin "13") (pinfunction "OEAB_13") (pintype "unspecified"))
      (node (ref "U108") (pin "2") (pinfunction "OEBA_2") (pintype "unspecified"))
    )
    (net (code "78") (name "DIP_EXT_TERM") (class "Default")
      (node (ref "R212G") (pin "2") (pinfunction "2_2") (pintype "input"))
      (node (ref "SW1") (pin "7") (pinfunction "PIN7_7") (pintype "unspecified"))
      (node (ref "U213") (pin "4") (pinfunction "I1_4") (pintype "unspecified"))
      (node (ref "U310") (pin "16") (pinfunction "PD#_16") (pintype "unspecified"))
      (node (ref "U311") (pin "16") (pinfunction "PD#_16") (pintype "unspecified"))
    )
    (net (code "79") (name "DIP_LONG_SPINUP") (class "Default")
      (node (ref "R212E") (pin "2") (pinfunction "2_2") (pintype "input"))
      (node (ref "SW1") (pin "5") (pinfunction "PIN5_5") (pintype "unspecified"))
      (node (ref "U213") (pin "8") (pinfunction "I3_8") (pintype "unspecified"))
    )
    (net (code "80") (name "DIP_SCSI_ADR0") (class "Default")
      (node (ref "R212A") (pin "2") (pinfunction "2_2") (pintype "input"))
      (node (ref "SW1") (pin "1") (pinfunction "PIN1_1") (pintype "unspecified"))
      (node (ref "U213") (pin "17") (pinfunction "I4_17") (pintype "unspecified"))
    )
    (net (code "81") (name "DIP_SCSI_ADR1") (class "Default")
      (node (ref "R212B") (pin "1") (pinfunction "1_1") (pintype "input"))
      (node (ref "SW1") (pin "2") (pinfunction "PIN2_2") (pintype "unspecified"))
      (node (ref "U213") (pin "15") (pinfunction "I5_15") (pintype "unspecified"))
    )
    (net (code "82") (name "DIP_SCSI_ADR2") (class "Default")
      (node (ref "R212C") (pin "1") (pinfunction "1_1") (pintype "input"))
      (node (ref "SW1") (pin "3") (pinfunction "PIN3_3") (pintype "unspecified"))
      (node (ref "U213") (pin "13") (pinfunction "I6_13") (pintype "unspecified"))
    )
    (net (code "83") (name "DIP_SCSI_FAST") (class "Default")
      (node (ref "R212D") (pin "1") (pinfunction "1_1") (pintype "input"))
      (node (ref "SW1") (pin "4") (pinfunction "PIN4_4") (pintype "unspecified"))
      (node (ref "U213") (pin "11") (pinfunction "I7_11") (pintype "unspecified"))
    )
    (net (code "84") (name "DIP_SCSI_LUNS") (class "Default")
      (node (ref "R212H") (pin "2") (pinfunction "2_2") (pintype "input"))
      (node (ref "SW1") (pin "8") (pinfunction "PIN8_8") (pintype "unspecified"))
      (node (ref "U213") (pin "2") (pinfunction "I0_2") (pintype "unspecified"))
    )
    (net (code "85") (name "DIP_SYNCH_MODE") (class "Default")
      (node (ref "R212F") (pin "2") (pinfunction "2_2") (pintype "input"))
      (node (ref "SW1") (pin "6") (pinfunction "PIN6_6") (pintype "unspecified"))
      (node (ref "U213") (pin "6") (pinfunction "I2_6") (pintype "unspecified"))
    )
    (net (code "86") (name "DP3_ABRT") (class "Default")
      (node (ref "R300P") (pin "1") (pinfunction "1_1") (pintype "input"))
      (node (ref "U300") (pin "52") (pinfunction "DP3_ABRT/_52") (pintype "unspecified"))
    )
    (net (code "87") (name "GND") (class "Default")
      (node (ref "C1") (pin "01") (pinfunction "GND_01") (pintype "bidirectional"))
      (node (ref "C1") (pin "02") (pinfunction "GND_02") (pintype "unspecified"))
      (node (ref "C1") (pin "03") (pinfunction "GND_03") (pintype "output"))
      (node (ref "C1") (pin "04") (pinfunction "GND_04") (pintype "bidirectional"))
      (node (ref "C1") (pin "100") (pinfunction "GND_100") (pintype "bidirectional"))
      (node (ref "C1") (pin "13") (pinfunction "GND_13") (pintype "bidirectional"))
      (node (ref "C1") (pin "25") (pinfunction "GND_25") (pintype "output"))
      (node (ref "C1") (pin "37") (pinfunction "GND_37") (pintype "unspecified"))
      (node (ref "C1") (pin "49") (pinfunction "GND_49") (pintype "unspecified"))
      (node (ref "C1") (pin "61") (pinfunction "GND_61") (pintype "bidirectional"))
      (node (ref "C1") (pin "73") (pinfunction "GND_73") (pintype "unspecified"))
      (node (ref "C1") (pin "85") (pinfunction "GND_85") (pintype "unspecified"))
      (node (ref "C1") (pin "87") (pinfunction "GND_87") (pintype "output"))
      (node (ref "C1") (pin "88") (pinfunction "GND_88") (pintype "bidirectional"))
      (node (ref "C1") (pin "89") (pinfunction "GND_89") (pintype "unspecified"))
      (node (ref "C1") (pin "90") (pinfunction "GND_90") (pintype "bidirectional"))
      (node (ref "C1") (pin "99") (pinfunction "GND_99") (pintype "bidirectional"))
      (node (ref "C10") (pin "2") (pinfunction "2_2") (pintype "input"))
      (node (ref "C100A") (pin "2") (pinfunction "2_2") (pintype "input"))
      (node (ref "C101A") (pin "2") (pinfunction "2_2") (pintype "input"))
      (node (ref "C102A") (pin "2") (pinfunction "2_2") (pintype "input"))
      (node (ref "C103A") (pin "2") (pinfunction "2_2") (pintype "input"))
      (node (ref "C105A") (pin "2") (pinfunction "2_2") (pintype "input"))
      (node (ref "C106A") (pin "1") (pinfunction "1_1") (pintype "input"))
      (node (ref "C107A") (pin "2") (pinfunction "2_2") (pintype "input"))
      (node (ref "C108A") (pin "2") (pinfunction "2_2") (pintype "input"))
      (node (ref "C109A") (pin "2") (pinfunction "2_2") (pintype "input"))
      (node (ref "C11") (pin "2") (pinfunction "2_2") (pintype "input"))
      (node (ref "C12") (pin "2") (pinfunction "2_2") (pintype "input"))
      (node (ref "C13") (pin "2") (pinfunction "2_2") (pintype "input"))
      (node (ref "C1A") (pin "1") (pinfunction "1_1") (pintype "input"))
      (node (ref "C1B") (pin "2") (pinfunction "2_2") (pintype "input"))
      (node (ref "C1C") (pin "2") (pinfunction "2_2") (pintype "input"))
      (node (ref "C200A") (pin "1") (pinfunction "1_1") (pintype "input"))
      (node (ref "C201A") (pin "2") (pinfunction "2_2") (pintype "input"))
      (node (ref "C202A") (pin "2") (pinfunction "2_2") (pintype "input"))
      (node (ref "C203A") (pin "2") (pinfunction "2_2") (pintype "input"))
      (node (ref "C204A") (pin "1") (pinfunction "1_1") (pintype "input"))
      (node (ref "C205A") (pin "2") (pinfunction "2_2") (pintype "input"))
      (node (ref "C206A") (pin "1") (pinfunction "1_1") (pintype "input"))
      (node (ref "C207A") (pin "2") (pinfunction "2_2") (pintype "input"))
      (node (ref "C212A") (pin "2") (pinfunction "2_2") (pintype "input"))
      (node (ref "C300A") (pin "2") (pinfunction "2_2") (pintype "input"))
      (node (ref "C300B") (pin "2") (pinfunction "2_2") (pintype "input"))
      (node (ref "C300C") (pin "2") (pinfunction "2_2") (pintype "input"))
      (node (ref "C300D") (pin "1") (pinfunction "1_1") (pintype "input"))
      (node (ref "C300E") (pin "2") (pinfunction "2_2") (pintype "input"))
      (node (ref "C300F") (pin "2") (pinfunction "2_2") (pintype "input"))
      (node (ref "C300G") (pin "2") (pinfunction "2_2") (pintype "input"))
      (node (ref "C300H") (pin "1") (pinfunction "1_1") (pintype "input"))
      (node (ref "C300I") (pin "2") (pinfunction "2_2") (pintype "input"))
      (node (ref "C301A") (pin "1") (pinfunction "1_1") (pintype "input"))
      (node (ref "C302A") (pin "2") (pinfunction "2_2") (pintype "input"))
      (node (ref "C303A") (pin "1") (pinfunction "1_1") (pintype "input"))
      (node (ref "C304A") (pin "2") (pinfunction "2_2") (pintype "input"))
      (node (ref "C305A") (pin "2") (pinfunction "2_2") (pintype "input"))
      (node (ref "C306A") (pin "2") (pinfunction "2_2") (pintype "input"))
      (node (ref "C306B") (pin "2") (pinfunction "2_2") (pintype "input"))
      (node (ref "C307A") (pin "1") (pinfunction "1_1") (pintype "input"))
      (node (ref "C310A") (pin "1") (pinfunction "1_1") (pintype "unspecified"))
      (node (ref "C310B") (pin "1") (pinfunction "1_1") (pintype "unspecified"))
      (node (ref "C310C") (pin "1") (pinfunction "1_1") (pintype "unspecified"))
      (node (ref "C310D") (pin "1") (pinfunction "1_1") (pintype "unspecified"))
      (node (ref "C310E") (pin "1") (pinfunction "1_1") (pintype "unspecified"))
      (node (ref "C310F") (pin "1") (pinfunction "1_1") (pintype "unspecified"))
      (node (ref "C310G") (pin "1") (pinfunction "1_1") (pintype "unspecified"))
      (node (ref "C310H") (pin "1") (pinfunction "1_1") (pintype "unspecified"))
      (node (ref "C310I") (pin "1") (pinfunction "1_1") (pintype "unspecified"))
      (node (ref "C310J") (pin "2") (pinfunction "2_2") (pintype "unspecified"))
      (node (ref "C310K") (pin "2") (pinfunction "2_2") (pintype "unspecified"))
      (node (ref "C310L") (pin "2") (pinfunction "2_2") (pintype "unspecified"))
      (node (ref "C310M") (pin "2") (pinfunction "2_2") (pintype "unspecified"))
      (node (ref "C310N") (pin "2") (pinfunction "2_2") (pintype "unspecified"))
      (node (ref "C310O") (pin "2") (pinfunction "2_2") (pintype "unspecified"))
      (node (ref "C310P") (pin "2") (pinfunction "2_2") (pintype "unspecified"))
      (node (ref "C310Q") (pin "2") (pinfunction "2_2") (pintype "unspecified"))
      (node (ref "C310R") (pin "2") (pinfunction "2_2") (pintype "unspecified"))
      (node (ref "C350A") (pin "2") (pinfunction "2_2") (pintype "unspecified"))
      (node (ref "C350B") (pin "1") (pinfunction "1_1") (pintype "input"))
      (node (ref "C351A") (pin "2") (pinfunction "2_2") (pintype "unspecified"))
      (node (ref "C351B") (pin "2") (pinfunction "2_2") (pintype "input"))
      (node (ref "CN2") (pin "2") (pinfunction "2_2") (pintype "unspecified"))
      (node (ref "CN2") (pin "3") (pinfunction "3_3") (pintype "unspecified"))
      (node (ref "CN3") (pin "2") (pinfunction "GND_2") (pintype "unspecified"))
      (node (ref "CN3") (pin "3") (pinfunction "GND_3") (pintype "unspecified"))
      (node (ref "CN309") (pin "1") (pinfunction "1_1") (pintype "unspecified"))
      (node (ref "CN309") (pin "11") (pinfunction "11_11") (pintype "unspecified"))
      (node (ref "CN309") (pin "13") (pinfunction "13_13") (pintype "unspecified"))
      (node (ref "CN309") (pin "15") (pinfunction "15_15") (pintype "unspecified"))
      (node (ref "CN309") (pin "17") (pinfunction "17_17") (pintype "unspecified"))
      (node (ref "CN309") (pin "19") (pinfunction "19_19") (pintype "unspecified"))
      (node (ref "CN309") (pin "20") (pinfunction "20_20") (pintype "unspecified"))
      (node (ref "CN309") (pin "21") (pinfunction "21_21") (pintype "unspecified"))
      (node (ref "CN309") (pin "22") (pinfunction "22_22") (pintype "unspecified"))
      (node (ref "CN309") (pin "23") (pinfunction "23_23") (pintype "unspecified"))
      (node (ref "CN309") (pin "24") (pinfunction "24_24") (pintype "unspecified"))
      (node (ref "CN309") (pin "27") (pinfunction "27_27") (pintype "unspecified"))
      (node (ref "CN309") (pin "28") (pinfunction "28_28") (pintype "unspecified"))
      (node (ref "CN309") (pin "29") (pinfunction "29_29") (pintype "unspecified"))
      (node (ref "CN309") (pin "3") (pinfunction "3_3") (pintype "unspecified"))
      (node (ref "CN309") (pin "30") (pinfunction "30_30") (pintype "unspecified"))
      (node (ref "CN309") (pin "31") (pinfunction "31_31") (pintype "unspecified"))
      (node (ref "CN309") (pin "33") (pinfunction "33_33") (pintype "unspecified"))
      (node (ref "CN309") (pin "35") (pinfunction "35_35") (pintype "unspecified"))
      (node (ref "CN309") (pin "37") (pinfunction "37_37") (pintype "unspecified"))
      (node (ref "CN309") (pin "39") (pinfunction "39_39") (pintype "unspecified"))
      (node (ref "CN309") (pin "41") (pinfunction "41_41") (pintype "unspecified"))
      (node (ref "CN309") (pin "43") (pinfunction "43_43") (pintype "unspecified"))
      (node (ref "CN309") (pin "45") (pinfunction "45_45") (pintype "unspecified"))
      (node (ref "CN309") (pin "47") (pinfunction "47_47") (pintype "unspecified"))
      (node (ref "CN309") (pin "49") (pinfunction "49_49") (pintype "unspecified"))
      (node (ref "CN309") (pin "5") (pinfunction "5_5") (pintype "unspecified"))
      (node (ref "CN309") (pin "7") (pinfunction "7_7") (pintype "unspecified"))
      (node (ref "CN309") (pin "9") (pinfunction "9_9") (pintype "unspecified"))
      (node (ref "CN310") (pin "1") (pinfunction "GND_1") (pintype "unspecified"))
      (node (ref "CN310") (pin "10") (pinfunction "GND_10") (pintype "unspecified"))
      (node (ref "CN310") (pin "11") (pinfunction "GND_11") (pintype "unspecified"))
      (node (ref "CN310") (pin "15") (pinfunction "GND_15") (pintype "unspecified"))
      (node (ref "CN310") (pin "16") (pinfunction "GND_16") (pintype "unspecified"))
      (node (ref "CN310") (pin "17") (pinfunction "GND_17") (pintype "unspecified"))
      (node (ref "CN310") (pin "18") (pinfunction "GND_18") (pintype "unspecified"))
      (node (ref "CN310") (pin "19") (pinfunction "GND_19") (pintype "unspecified"))
      (node (ref "CN310") (pin "2") (pinfunction "GND_2") (pintype "unspecified"))
      (node (ref "CN310") (pin "20") (pinfunction "GND_20") (pintype "unspecified"))
      (node (ref "CN310") (pin "21") (pinfunction "GND_21") (pintype "unspecified"))
      (node (ref "CN310") (pin "22") (pinfunction "GND_22") (pintype "unspecified"))
      (node (ref "CN310") (pin "23") (pinfunction "GND_23") (pintype "unspecified"))
      (node (ref "CN310") (pin "24") (pinfunction "GND_24") (pintype "unspecified"))
      (node (ref "CN310") (pin "25") (pinfunction "GND_25") (pintype "unspecified"))
      (node (ref "CN310") (pin "3") (pinfunction "GND_3") (pintype "unspecified"))
      (node (ref "CN310") (pin "35") (pinfunction "GND_35") (pintype "unspecified"))
      (node (ref "CN310") (pin "36") (pinfunction "GND_36") (pintype "unspecified"))
      (node (ref "CN310") (pin "4") (pinfunction "GND_4") (pintype "unspecified"))
      (node (ref "CN310") (pin "40") (pinfunction "GND_40") (pintype "unspecified"))
      (node (ref "CN310") (pin "42") (pinfunction "GND_42") (pintype "unspecified"))
      (node (ref "CN310") (pin "5") (pinfunction "GND_5") (pintype "unspecified"))
      (node (ref "CN310") (pin "6") (pinfunction "GND_6") (pintype "unspecified"))
      (node (ref "CN310") (pin "7") (pinfunction "GND_7") (pintype "unspecified"))
      (node (ref "CN310") (pin "8") (pinfunction "GND_8") (pintype "unspecified"))
      (node (ref "CN310") (pin "9") (pinfunction "GND_9") (pintype "unspecified"))
      (node (ref "CN4") (pin "3") (pinfunction "3_3") (pintype "unspecified"))
      (node (ref "MH1") (pin "1") (pinfunction "1_1") (pintype "unspecified"))
      (node (ref "MH2") (pin "1") (pinfunction "1_1") (pintype "unspecified"))
      (node (ref "MH3") (pin "1") (pinfunction "1_1") (pintype "unspecified"))
      (node (ref "MH4") (pin "1") (pinfunction "1_1") (pintype "unspecified"))
      (node (ref "R109H") (pin "1") (pinfunction "1_1") (pintype "input"))
      (node (ref "RP300A") (pin "1") (pinfunction "COM1_1") (pintype "unspecified"))
      (node (ref "RP300B") (pin "1") (pinfunction "COM1_1") (pintype "unspecified"))
      (node (ref "RP300C") (pin "1") (pinfunction "COM1_1") (pintype "unspecified"))
      (node (ref "SW1") (pin "10") (pinfunction "PIN10_10") (pintype "unspecified"))
      (node (ref "SW1") (pin "11") (pinfunction "PIN11_11") (pintype "unspecified"))
      (node (ref "SW1") (pin "12") (pinfunction "PIN12_12") (pintype "unspecified"))
      (node (ref "SW1") (pin "13") (pinfunction "PIN13_13") (pintype "unspecified"))
      (node (ref "SW1") (pin "14") (pinfunction "PIN14_14") (pintype "unspecified"))
      (node (ref "SW1") (pin "15") (pinfunction "PIN15_15") (pintype "unspecified"))
      (node (ref "SW1") (pin "16") (pinfunction "PIN16_16") (pintype "unspecified"))
      (node (ref "SW1") (pin "9") (pinfunction "PIN9_9") (pintype "unspecified"))
      (node (ref "U100") (pin "12") (pinfunction "GND_12") (pintype "passive"))
      (node (ref "U100") (pin "14") (pinfunction "LEAB_14") (pintype "unspecified"))
      (node (ref "U101") (pin "12") (pinfunction "GND_12") (pintype "passive"))
      (node (ref "U101") (pin "14") (pinfunction "LEAB_14") (pintype "unspecified"))
      (node (ref "U102") (pin "12") (pinfunction "GND_12") (pintype "passive"))
      (node (ref "U102") (pin "14") (pinfunction "LEAB_14") (pintype "unspecified"))
      (node (ref "U103") (pin "10") (pinfunction "GND_10") (pintype "unspecified"))
      (node (ref "U105") (pin "12") (pinfunction "GND_12") (pintype "passive"))
      (node (ref "U106") (pin "12") (pinfunction "GND_12") (pintype "passive"))
      (node (ref "U107") (pin "12") (pinfunction "GND_12") (pintype "passive"))
      (node (ref "U108") (pin "12") (pinfunction "GND_12") (pintype "passive"))
      (node (ref "U109") (pin "10") (pinfunction "GND_10") (pintype "unspecified"))
      (node (ref "U200") (pin "10") (pinfunction "GND_10") (pintype "unspecified"))
      (node (ref "U201") (pin "1") (pinfunction "IA=B_1") (pintype "unspecified"))
      (node (ref "U201") (pin "10") (pinfunction "GND_10") (pintype "unspecified"))
      (node (ref "U202") (pin "14") (pinfunction "GND_14") (pintype "unspecified"))
      (node (ref "U203") (pin "14") (pinfunction "GND_14") (pintype "unspecified"))
      (node (ref "U204") (pin "10") (pinfunction "GND_10") (pintype "unspecified"))
      (node (ref "U205") (pin "14") (pinfunction "GND_14") (pintype "unspecified"))
      (node (ref "U206") (pin "14") (pinfunction "GND_14") (pintype "output"))
      (node (ref "U206") (pin "20") (pinfunction "CE#_20") (pintype "output"))
      (node (ref "U207") (pin "14") (pinfunction "GND_14") (pintype "unspecified"))
      (node (ref "U213") (pin "10") (pinfunction "GND_10") (pintype "unspecified"))
      (node (ref "U300") (pin "109") (pinfunction "Vss_109") (pintype "unspecified"))
      (node (ref "U300") (pin "113") (pinfunction "Vss_113") (pintype "unspecified"))
      (node (ref "U300") (pin "118") (pinfunction "Vss_118") (pintype "unspecified"))
      (node (ref "U300") (pin "123") (pinfunction "Vss_123") (pintype "unspecified"))
      (node (ref "U300") (pin "128") (pinfunction "Vss_128") (pintype "unspecified"))
      (node (ref "U300") (pin "136") (pinfunction "Vss_136") (pintype "unspecified"))
      (node (ref "U300") (pin "143") (pinfunction "Vss_143") (pintype "unspecified"))
      (node (ref "U300") (pin "149") (pinfunction "Vss_149") (pintype "unspecified"))
      (node (ref "U300") (pin "15") (pinfunction "Vss_15") (pintype "unspecified"))
      (node (ref "U300") (pin "156") (pinfunction "Vss_156") (pintype "unspecified"))
      (node (ref "U300") (pin "2") (pinfunction "Vss_2") (pintype "unspecified"))
      (node (ref "U300") (pin "22") (pinfunction "Vss_22") (pintype "unspecified"))
      (node (ref "U300") (pin "31") (pinfunction "Vss_31") (pintype "unspecified"))
      (node (ref "U300") (pin "46") (pinfunction "Vss_46") (pintype "unspecified"))
      (node (ref "U300") (pin "54") (pinfunction "Vss_54") (pintype "unspecified"))
      (node (ref "U300") (pin "61") (pinfunction "Vss_61") (pintype "unspecified"))
      (node (ref "U300") (pin "69") (pinfunction "Vss_69") (pintype "unspecified"))
      (node (ref "U300") (pin "75") (pinfunction "Vss_75") (pintype "unspecified"))
      (node (ref "U300") (pin "82") (pinfunction "Vss_82") (pintype "unspecified"))
      (node (ref "U300") (pin "9") (pinfunction "Vss_9") (pintype "unspecified"))
      (node (ref "U300") (pin "96") (pinfunction "Vss_96") (pintype "unspecified"))
      (node (ref "U301") (pin "7") (pinfunction "Gnd_7") (pintype "unspecified"))
      (node (ref "U302") (pin "7") (pinfunction "GND_7") (pintype "unspecified"))
      (node (ref "U303") (pin "14") (pinfunction "GND_14") (pintype "unspecified"))
      (node (ref "U304") (pin "14") (pinfunction "GND_14") (pintype "unspecified"))
      (node (ref "U305") (pin "14") (pinfunction "GND_14") (pintype "unspecified"))
      (node (ref "U306") (pin "14") (pinfunction "GND_14") (pintype "unspecified"))
      (node (ref "U307") (pin "11") (pinfunction "5A_11") (pintype "unspecified"))
      (node (ref "U307") (pin "13") (pinfunction "6A_13") (pintype "unspecified"))
      (node (ref "U307") (pin "7") (pinfunction "GND_7") (pintype "unspecified"))
      (node (ref "U310") (pin "8") (pinfunction "GND_8") (pintype "passive"))
      (node (ref "U311") (pin "8") (pinfunction "GND_8") (pintype "passive"))
    )
    (net (code "88") (name "IORST") (class "Default")
      (node (ref "R307A") (pin "1") (pinfunction "1_1") (pintype "input"))
      (node (ref "U202") (pin "19") (pinfunction "IOQ_19") (pintype "unspecified"))
      (node (ref "U203") (pin "27") (pinfunction "IOQ_27") (pintype "unspecified"))
      (node (ref "U207") (pin "9") (pinfunction "I_9") (pintype "unspecified"))
      (node (ref "U300") (pin "94") (pinfunction "RESET/_94") (pintype "unspecified"))
      (node (ref "U303") (pin "11") (pinfunction "I_11") (pintype "unspecified"))
      (node (ref "U306") (pin "12") (pinfunction "I_12") (pintype "unspecified"))
      (node (ref "U307") (pin "8") (pinfunction "4Y_8") (pintype "unspecified"))
    )
    (net (code "89") (name "LED") (class "Default")
      (node (ref "R398") (pin "2") (pinfunction "2_2") (pintype "unspecified"))
      (node (ref "U307") (pin "2") (pinfunction "1Y_2") (pintype "unspecified"))
      (node (ref "U307") (pin "4") (pinfunction "2Y_4") (pintype "unspecified"))
    )
    (net (code "90") (name "LEDR") (class "Default")
      (node (ref "CN308") (pin "1") (pinfunction "1_1") (pintype "input"))
      (node (ref "CN308") (pin "3") (pinfunction "3_3") (pintype "input"))
      (node (ref "CN351") (pin "1") (pinfunction "1_1") (pintype "input"))
      (node (ref "CN351") (pin "3") (pinfunction "3_3") (pintype "input"))
      (node (ref "R398") (pin "1") (pinfunction "1_1") (pintype "unspecified"))
    )
    (net (code "91") (name "M24") (class "Default")
      (node (ref "R200H") (pin "1") (pinfunction "1_1") (pintype "input"))
      (node (ref "U200") (pin "19") (pinfunction "Q7_19") (pintype "unspecified"))
      (node (ref "U201") (pin "18") (pinfunction "B7_18") (pintype "unspecified"))
    )
    (net (code "92") (name "M25") (class "Default")
      (node (ref "R200G") (pin "1") (pinfunction "1_1") (pintype "input"))
      (node (ref "U200") (pin "16") (pinfunction "Q6_16") (pintype "unspecified"))
      (node (ref "U201") (pin "16") (pinfunction "B6_16") (pintype "unspecified"))
    )
    (net (code "93") (name "M26") (class "Default")
      (node (ref "R200F") (pin "1") (pinfunction "1_1") (pintype "input"))
      (node (ref "U200") (pin "15") (pinfunction "Q5_15") (pintype "unspecified"))
      (node (ref "U201") (pin "14") (pinfunction "B5_14") (pintype "unspecified"))
    )
    (net (code "94") (name "M27") (class "Default")
      (node (ref "R200E") (pin "1") (pinfunction "1_1") (pintype "input"))
      (node (ref "U200") (pin "12") (pinfunction "Q4_12") (pintype "unspecified"))
      (node (ref "U201") (pin "12") (pinfunction "B4_12") (pintype "unspecified"))
    )
    (net (code "95") (name "M28") (class "Default")
      (node (ref "R200D") (pin "1") (pinfunction "1_1") (pintype "input"))
      (node (ref "U200") (pin "9") (pinfunction "Q3_9") (pintype "unspecified"))
      (node (ref "U201") (pin "9") (pinfunction "B3_9") (pintype "unspecified"))
    )
    (net (code "96") (name "M29") (class "Default")
      (node (ref "R200C") (pin "1") (pinfunction "1_1") (pintype "input"))
      (node (ref "U200") (pin "6") (pinfunction "Q2_6") (pintype "unspecified"))
      (node (ref "U201") (pin "7") (pinfunction "B2_7") (pintype "unspecified"))
    )
    (net (code "97") (name "M30") (class "Default")
      (node (ref "R200B") (pin "1") (pinfunction "1_1") (pintype "input"))
      (node (ref "U200") (pin "5") (pinfunction "Q1_5") (pintype "unspecified"))
      (node (ref "U201") (pin "5") (pinfunction "B1_5") (pintype "unspecified"))
    )
    (net (code "98") (name "M31") (class "Default")
      (node (ref "R200A") (pin "1") (pinfunction "1_1") (pintype "input"))
      (node (ref "U200") (pin "2") (pinfunction "Q0_2") (pintype "unspecified"))
      (node (ref "U201") (pin "3") (pinfunction "B0_3") (pintype "unspecified"))
    )
    (net (code "99") (name "MASTER") (class "Default")
      (node (ref "FB502") (pin "1") (pinfunction "1_1") (pintype "unspecified"))
      (node (ref "U100") (pin "11") (pinfunction "CEAB_11") (pintype "unspecified"))
      (node (ref "U101") (pin "11") (pinfunction "CEAB_11") (pintype "unspecified"))
      (node (ref "U102") (pin "11") (pinfunction "CEAB_11") (pintype "unspecified"))
      (node (ref "U205") (pin "18") (pinfunction "IOQ_18") (pintype "unspecified"))
      (node (ref "U303") (pin "3") (pinfunction "I_3") (pintype "unspecified"))
    )
    (net (code "100") (name "MATCH") (class "Default")
      (node (ref "U201") (pin "19") (pinfunction "OA=B_19") (pintype "unspecified"))
      (node (ref "U202") (pin "2") (pinfunction "CLK/I_2") (pintype "unspecified"))
    )
    (net (code "101") (name "NCR_INT") (class "Default")
      (node (ref "U207") (pin "10") (pinfunction "I_10") (pintype "unspecified"))
      (node (ref "U300") (pin "105") (pinfunction "IRQ/_105") (pintype "unspecified"))
    )
    (net (code "102") (name "Net-(CN309-Pad2)") (class "Default")
      (node (ref "CN309") (pin "2") (pinfunction "2_2") (pintype "unspecified"))
      (node (ref "FB311A") (pin "1") (pinfunction "1_1") (pintype "unspecified"))
    )
    (net (code "103") (name "Net-(CN309-Pad4)") (class "Default")
      (node (ref "CN309") (pin "4") (pinfunction "4_4") (pintype "unspecified"))
      (node (ref "FB311B") (pin "1") (pinfunction "1_1") (pintype "unspecified"))
    )
    (net (code "104") (name "Net-(CN309-Pad6)") (class "Default")
      (node (ref "CN309") (pin "6") (pinfunction "6_6") (pintype "unspecified"))
      (node (ref "FB311C") (pin "1") (pinfunction "1_1") (pintype "unspecified"))
    )
    (net (code "105") (name "Net-(CN309-Pad8)") (class "Default")
      (node (ref "CN309") (pin "8") (pinfunction "8_8") (pintype "unspecified"))
      (node (ref "FB311D") (pin "1") (pinfunction "1_1") (pintype "unspecified"))
    )
    (net (code "106") (name "Net-(CN309-Pad10)") (class "Default")
      (node (ref "CN309") (pin "10") (pinfunction "10_10") (pintype "unspecified"))
      (node (ref "FB311E") (pin "1") (pinfunction "1_1") (pintype "unspecified"))
    )
    (net (code "107") (name "Net-(CN309-Pad12)") (class "Default")
      (node (ref "CN309") (pin "12") (pinfunction "12_12") (pintype "unspecified"))
      (node (ref "FB311F") (pin "1") (pinfunction "1_1") (pintype "unspecified"))
    )
    (net (code "108") (name "Net-(CN309-Pad14)") (class "Default")
      (node (ref "CN309") (pin "14") (pinfunction "14_14") (pintype "unspecified"))
      (node (ref "FB311G") (pin "1") (pinfunction "1_1") (pintype "unspecified"))
    )
    (net (code "109") (name "Net-(CN309-Pad16)") (class "Default")
      (node (ref "CN309") (pin "16") (pinfunction "16_16") (pintype "unspecified"))
      (node (ref "FB311H") (pin "1") (pinfunction "1_1") (pintype "unspecified"))
    )
    (net (code "110") (name "Net-(CN309-Pad18)") (class "Default")
      (node (ref "CN309") (pin "18") (pinfunction "18_18") (pintype "unspecified"))
      (node (ref "FB311I") (pin "1") (pinfunction "1_1") (pintype "unspecified"))
    )
    (net (code "111") (name "Net-(CN309-Pad32)") (class "Default")
      (node (ref "CN309") (pin "32") (pinfunction "32_32") (pintype "unspecified"))
      (node (ref "FB311J") (pin "1") (pinfunction "1_1") (pintype "unspecified"))
    )
    (net (code "112") (name "Net-(CN309-Pad38)") (class "Default")
      (node (ref "CN309") (pin "38") (pinfunction "38_38") (pintype "unspecified"))
      (node (ref "FB311Q") (pin "1") (pinfunction "1_1") (pintype "unspecified"))
    )
    (net (code "113") (name "Net-(CN309-Pad40)") (class "Default")
      (node (ref "CN309") (pin "40") (pinfunction "40_40") (pintype "unspecified"))
      (node (ref "FB311P") (pin "1") (pinfunction "1_1") (pintype "unspecified"))
    )
    (net (code "114") (name "Net-(CN309-Pad42)") (class "Default")
      (node (ref "CN309") (pin "42") (pinfunction "42_42") (pintype "unspecified"))
      (node (ref "FB311O") (pin "1") (pinfunction "1_1") (pintype "unspecified"))
    )
    (net (code "115") (name "Net-(CN309-Pad44)") (class "Default")
      (node (ref "CN309") (pin "44") (pinfunction "44_44") (pintype "unspecified"))
      (node (ref "FB311N") (pin "1") (pinfunction "1_1") (pintype "unspecified"))
    )
    (net (code "116") (name "Net-(CN309-Pad46)") (class "Default")
      (node (ref "CN309") (pin "46") (pinfunction "46_46") (pintype "unspecified"))
      (node (ref "FB311M") (pin "1") (pinfunction "1_1") (pintype "unspecified"))
    )
    (net (code "117") (name "Net-(CN309-Pad48)") (class "Default")
      (node (ref "CN309") (pin "48") (pinfunction "48_48") (pintype "unspecified"))
      (node (ref "FB311L") (pin "1") (pinfunction "1_1") (pintype "unspecified"))
    )
    (net (code "118") (name "Net-(CN309-Pad50)") (class "Default")
      (node (ref "CN309") (pin "50") (pinfunction "50_50") (pintype "unspecified"))
      (node (ref "FB311K") (pin "1") (pinfunction "1_1") (pintype "unspecified"))
    )
    (net (code "119") (name "Net-(CN310-ACK)") (class "Default")
      (node (ref "C310G") (pin "2") (pinfunction "2_2") (pintype "unspecified"))
      (node (ref "CN310") (pin "44") (pinfunction "ACK_44") (pintype "unspecified"))
      (node (ref "FB310G") (pin "2") (pinfunction "2_2") (pintype "unspecified"))
    )
    (net (code "120") (name "Net-(CN310-ATN)") (class "Default")
      (node (ref "C310I") (pin "2") (pinfunction "2_2") (pintype "unspecified"))
      (node (ref "CN310") (pin "41") (pinfunction "ATN_41") (pintype "unspecified"))
      (node (ref "FB310I") (pin "2") (pinfunction "2_2") (pintype "unspecified"))
    )
    (net (code "121") (name "Net-(CN310-BSY)") (class "Default")
      (node (ref "C310H") (pin "2") (pinfunction "2_2") (pintype "unspecified"))
      (node (ref "CN310") (pin "43") (pinfunction "BSY_43") (pintype "unspecified"))
      (node (ref "FB310H") (pin "2") (pinfunction "2_2") (pintype "unspecified"))
    )
    (net (code "122") (name "Net-(CN310-CD)") (class "Default")
      (node (ref "C310C") (pin "2") (pinfunction "2_2") (pintype "unspecified"))
      (node (ref "CN310") (pin "48") (pinfunction "CD_48") (pintype "unspecified"))
      (node (ref "FB310C") (pin "2") (pinfunction "2_2") (pintype "unspecified"))
    )
    (net (code "123") (name "Net-(CN310-D0)") (class "Default")
      (node (ref "C310K") (pin "1") (pinfunction "1_1") (pintype "unspecified"))
      (node (ref "CN310") (pin "26") (pinfunction "D0_26") (pintype "unspecified"))
      (node (ref "FB310K") (pin "2") (pinfunction "2_2") (pintype "unspecified"))
    )
    (net (code "124") (name "Net-(CN310-D1)") (class "Default")
      (node (ref "C310L") (pin "1") (pinfunction "1_1") (pintype "unspecified"))
      (node (ref "CN310") (pin "27") (pinfunction "D1_27") (pintype "unspecified"))
      (node (ref "FB310L") (pin "2") (pinfunction "2_2") (pintype "unspecified"))
    )
    (net (code "125") (name "Net-(CN310-D2)") (class "Default")
      (node (ref "C310M") (pin "1") (pinfunction "1_1") (pintype "unspecified"))
      (node (ref "CN310") (pin "28") (pinfunction "D2_28") (pintype "unspecified"))
      (node (ref "FB310M") (pin "2") (pinfunction "2_2") (pintype "unspecified"))
    )
    (net (code "126") (name "Net-(CN310-D3)") (class "Default")
      (node (ref "C310N") (pin "1") (pinfunction "1_1") (pintype "unspecified"))
      (node (ref "CN310") (pin "29") (pinfunction "D3_29") (pintype "unspecified"))
      (node (ref "FB310N") (pin "2") (pinfunction "2_2") (pintype "unspecified"))
    )
    (net (code "127") (name "Net-(CN310-D4)") (class "Default")
      (node (ref "C310O") (pin "1") (pinfunction "1_1") (pintype "unspecified"))
      (node (ref "CN310") (pin "30") (pinfunction "D4_30") (pintype "unspecified"))
      (node (ref "FB310O") (pin "2") (pinfunction "2_2") (pintype "unspecified"))
    )
    (net (code "128") (name "Net-(CN310-D5)") (class "Default")
      (node (ref "C310P") (pin "1") (pinfunction "1_1") (pintype "unspecified"))
      (node (ref "CN310") (pin "31") (pinfunction "D5_31") (pintype "unspecified"))
      (node (ref "FB310P") (pin "2") (pinfunction "2_2") (pintype "unspecified"))
    )
    (net (code "129") (name "Net-(CN310-D6)") (class "Default")
      (node (ref "C310Q") (pin "1") (pinfunction "1_1") (pintype "unspecified"))
      (node (ref "CN310") (pin "32") (pinfunction "D6_32") (pintype "unspecified"))
      (node (ref "FB310Q") (pin "2") (pinfunction "2_2") (pintype "unspecified"))
    )
    (net (code "130") (name "Net-(CN310-D7)") (class "Default")
      (node (ref "C310R") (pin "1") (pinfunction "1_1") (pintype "unspecified"))
      (node (ref "CN310") (pin "33") (pinfunction "D7_33") (pintype "unspecified"))
      (node (ref "FB310R") (pin "2") (pinfunction "2_2") (pintype "unspecified"))
    )
    (net (code "131") (name "Net-(CN310-DP)") (class "Default")
      (node (ref "C310J") (pin "1") (pinfunction "1_1") (pintype "unspecified"))
      (node (ref "CN310") (pin "34") (pinfunction "DP_34") (pintype "unspecified"))
      (node (ref "FB310J") (pin "2") (pinfunction "2_2") (pintype "unspecified"))
    )
    (net (code "132") (name "Net-(CN310-IO)") (class "Default")
      (node (ref "C310A") (pin "2") (pinfunction "2_2") (pintype "unspecified"))
      (node (ref "CN310") (pin "50") (pinfunction "IO_50") (pintype "unspecified"))
      (node (ref "FB310A") (pin "2") (pinfunction "2_2") (pintype "unspecified"))
    )
    (net (code "133") (name "Net-(CN310-MSG)") (class "Default")
      (node (ref "C310E") (pin "2") (pinfunction "2_2") (pintype "unspecified"))
      (node (ref "CN310") (pin "46") (pinfunction "MSG_46") (pintype "unspecified"))
      (node (ref "FB310E") (pin "2") (pinfunction "2_2") (pintype "unspecified"))
    )
    (net (code "134") (name "Net-(CN310-REQ)") (class "Default")
      (node (ref "C310B") (pin "2") (pinfunction "2_2") (pintype "unspecified"))
      (node (ref "CN310") (pin "49") (pinfunction "REQ_49") (pintype "unspecified"))
      (node (ref "FB310B") (pin "2") (pinfunction "2_2") (pintype "unspecified"))
    )
    (net (code "135") (name "Net-(CN310-RST)") (class "Default")
      (node (ref "C310F") (pin "2") (pinfunction "2_2") (pintype "unspecified"))
      (node (ref "CN310") (pin "45") (pinfunction "RST_45") (pintype "unspecified"))
      (node (ref "FB310F") (pin "2") (pinfunction "2_2") (pintype "unspecified"))
    )
    (net (code "136") (name "Net-(CN310-SEL)") (class "Default")
      (node (ref "C310D") (pin "2") (pinfunction "2_2") (pintype "unspecified"))
      (node (ref "CN310") (pin "47") (pinfunction "SEL_47") (pintype "unspecified"))
      (node (ref "FB310D") (pin "2") (pinfunction "2_2") (pintype "unspecified"))
    )
    (net (code "137") (name "Net-(D309A-C)") (class "Default")
      (node (ref "D309A") (pin "1") (pinfunction "C_1") (pintype "unspecified"))
      (node (ref "F309A") (pin "1") (pinfunction "1_1") (pintype "unspecified"))
      (node (ref "F309B") (pin "1") (pinfunction "1_1") (pintype "unspecified"))
    )
    (net (code "138") (name "Net-(FB500-Pad1)") (class "Default")
      (node (ref "FB500") (pin "1") (pinfunction "1_1") (pintype "unspecified"))
      (node (ref "U305") (pin "19") (pinfunction "IOQ_19") (pintype "unspecified"))
    )
    (net (code "139") (name "Net-(FB501-Pad1)") (class "Default")
      (node (ref "FB501") (pin "1") (pinfunction "1_1") (pintype "unspecified"))
      (node (ref "U306") (pin "21") (pinfunction "IOQ_21") (pintype "unspecified"))
    )
    (net (code "140") (name "Net-(FB504-Pad1)") (class "Default")
      (node (ref "FB504") (pin "1") (pinfunction "1_1") (pintype "unspecified"))
      (node (ref "U205") (pin "23") (pinfunction "IOQ_23") (pintype "unspecified"))
    )
    (net (code "141") (name "Net-(FB505-Pad1)") (class "Default")
      (node (ref "FB505") (pin "1") (pinfunction "1_1") (pintype "unspecified"))
      (node (ref "U205") (pin "25") (pinfunction "IOQ_25") (pintype "unspecified"))
    )
    (net (code "142") (name "Net-(U109-B4)") (class "Default")
      (node (ref "FB507") (pin "1") (pinfunction "1_1") (pintype "unspecified"))
      (node (ref "U109") (pin "14") (pinfunction "B4_14") (pintype "unspecified"))
    )
    (net (code "143") (name "Net-(U109-B5)") (class "Default")
      (node (ref "FB508") (pin "1") (pinfunction "1_1") (pintype "unspecified"))
      (node (ref "U109") (pin "13") (pinfunction "B5_13") (pintype "unspecified"))
    )
    (net (code "144") (name "Net-(U300-BR{slash})") (class "Default")
      (node (ref "FB503") (pin "1") (pinfunction "1_1") (pintype "unspecified"))
      (node (ref "U300") (pin "101") (pinfunction "BR/_101") (pintype "unspecified"))
    )
    (net (code "145") (name "Net-(U300-DP0)") (class "Default")
      (node (ref "R300M") (pin "2") (pinfunction "2_2") (pintype "input"))
      (node (ref "U300") (pin "86") (pinfunction "DP0_86") (pintype "unspecified"))
    )
    (net (code "146") (name "Net-(U300-DP1)") (class "Default")
      (node (ref "R300N") (pin "1") (pinfunction "1_1") (pintype "input"))
      (node (ref "U300") (pin "74") (pinfunction "DP1_74") (pintype "unspecified"))
    )
    (net (code "147") (name "Net-(U300-DP2)") (class "Default")
      (node (ref "R300O") (pin "1") (pinfunction "1_1") (pintype "input"))
      (node (ref "U300") (pin "63") (pinfunction "DP2_63") (pintype "unspecified"))
    )
    (net (code "148") (name "Net-(U300-MASTER{slash})") (class "Default")
      (node (ref "FB502") (pin "2") (pinfunction "2_2") (pintype "unspecified"))
      (node (ref "U300") (pin "38") (pinfunction "MASTER/_38") (pintype "unspecified"))
    )
    (net (code "149") (name "Net-(U300-R_W{slash})") (class "Default")
      (node (ref "FB506") (pin "2") (pinfunction "2_2") (pintype "unspecified"))
      (node (ref "U300") (pin "32") (pinfunction "R_W/_32") (pintype "unspecified"))
    )
    (net (code "150") (name "Net-(U301-Out)") (class "Default")
      (node (ref "R301A") (pin "2") (pinfunction "2_2") (pintype "input"))
      (node (ref "U301") (pin "8") (pinfunction "Out_8") (pintype "unspecified"))
    )
    (net (code "151") (name "Net-(U302-Q0#)") (class "Default")
      (node (ref "R302A") (pin "2") (pinfunction "2_2") (pintype "input"))
      (node (ref "U302") (pin "6") (pinfunction "Q0#_6") (pintype "unspecified"))
    )
    (net (code "152") (name "Net-(U302-Q0)") (class "Default")
      (node (ref "R302B") (pin "2") (pinfunction "2_2") (pintype "input"))
      (node (ref "U302") (pin "5") (pinfunction "Q0_5") (pintype "unspecified"))
    )
    (net (code "153") (name "Net-(U310-VREF1)") (class "Default")
      (node (ref "C350A") (pin "1") (pinfunction "1_1") (pintype "unspecified"))
      (node (ref "C350B") (pin "2") (pinfunction "2_2") (pintype "input"))
      (node (ref "U310") (pin "15") (pinfunction "VREF2_15") (pintype "passive"))
      (node (ref "U310") (pin "7") (pinfunction "VREF1_7") (pintype "passive"))
    )
    (net (code "154") (name "Net-(U311-VREF1)") (class "Default")
      (node (ref "C351A") (pin "1") (pinfunction "1_1") (pintype "unspecified"))
      (node (ref "C351B") (pin "1") (pinfunction "1_1") (pintype "input"))
      (node (ref "U311") (pin "15") (pinfunction "VREF2_15") (pintype "passive"))
      (node (ref "U311") (pin "7") (pinfunction "VREF1_7") (pintype "passive"))
    )
    (net (code "155") (name "Net-(U400-VREF1)") (class "Default")
      (node (ref "C400A") (pin "1") (pinfunction "1_1") (pintype "unspecified"))
      (node (ref "C400B") (pin "2") (pinfunction "2_2") (pintype "input"))
      (node (ref "U400") (pin "15") (pinfunction "VREF2_15") (pintype "passive"))
      (node (ref "U400") (pin "7") (pinfunction "VREF1_7") (pintype "passive"))
    )
    (net (code "156") (name "Net-(U401-VREF1)") (class "Default")
      (node (ref "C401A") (pin "1") (pinfunction "1_1") (pintype "unspecified"))
      (node (ref "C401B") (pin "2") (pinfunction "2_2") (pintype "input"))
      (node (ref "U401") (pin "15") (pinfunction "VREF2_15") (pintype "passive"))
      (node (ref "U401") (pin "7") (pinfunction "VREF1_7") (pintype "passive"))
    )
    (net (code "157") (name "PLD_AS") (class "Default")
      (node (ref "R300H") (pin "1") (pinfunction "1_1") (pintype "input"))
      (node (ref "U300") (pin "25") (pinfunction "AS/-TS/_25") (pintype "unspecified"))
      (node (ref "U304") (pin "21") (pinfunction "IOQ_21") (pintype "unspecified"))
      (node (ref "U305") (pin "4") (pinfunction "I_4") (pintype "unspecified"))
    )
    (net (code "158") (name "PLD_ASQ") (class "Default")
      (node (ref "U305") (pin "20") (pinfunction "IOQ_20") (pintype "unspecified"))
      (node (ref "U306") (pin "13") (pinfunction "I_13") (pintype "unspecified"))
    )
    (net (code "159") (name "PLD_CFGLT") (class "Default")
      (node (ref "U200") (pin "11") (pinfunction "CP_11") (pintype "unspecified"))
      (node (ref "U202") (pin "23") (pinfunction "IOQ_23") (pintype "unspecified"))
    )
    (net (code "160") (name "PLD_DOE") (class "Default")
      (node (ref "R109H") (pin "2") (pinfunction "2_2") (pintype "input"))
      (node (ref "U109") (pin "4") (pinfunction "A2_4") (pintype "unspecified"))
      (node (ref "U205") (pin "5") (pinfunction "I_5") (pintype "unspecified"))
      (node (ref "U304") (pin "10") (pinfunction "I_10") (pintype "unspecified"))
      (node (ref "U305") (pin "27") (pinfunction "IOQ_27") (pintype "unspecified"))
      (node (ref "U306") (pin "23") (pinfunction "IOQ_23") (pintype "unspecified"))
    )
    (net (code "161") (name "PLD_DS") (class "Default")
      (node (ref "R300G") (pin "1") (pinfunction "1_1") (pintype "input"))
      (node (ref "U300") (pin "87") (pinfunction "DS/-DLE_87") (pintype "unspecified"))
      (node (ref "U304") (pin "20") (pinfunction "IOQ_20") (pintype "unspecified"))
    )
    (net (code "162") (name "PLD_DS0") (class "Default")
      (node (ref "R109A") (pin "1") (pinfunction "1_1") (pintype "input"))
      (node (ref "U109") (pin "9") (pinfunction "A7_9") (pintype "unspecified"))
      (node (ref "U203") (pin "10") (pinfunction "I_10") (pintype "unspecified"))
      (node (ref "U207") (pin "6") (pinfunction "I_6") (pintype "unspecified"))
      (node (ref "U304") (pin "9") (pinfunction "I_9") (pintype "unspecified"))
      (node (ref "U305") (pin "23") (pinfunction "IOQ_23") (pintype "unspecified"))
    )
    (net (code "163") (name "PLD_DS1") (class "Default")
      (node (ref "R109B") (pin "1") (pinfunction "1_1") (pintype "input"))
      (node (ref "U109") (pin "8") (pinfunction "A6_8") (pintype "unspecified"))
      (node (ref "U304") (pin "7") (pinfunction "I_7") (pintype "unspecified"))
      (node (ref "U305") (pin "24") (pinfunction "IOQ_24") (pintype "unspecified"))
    )
    (net (code "164") (name "PLD_DS2") (class "Default")
      (node (ref "R109C") (pin "1") (pinfunction "1_1") (pintype "input"))
      (node (ref "U109") (pin "7") (pinfunction "A5_7") (pintype "unspecified"))
      (node (ref "U304") (pin "6") (pinfunction "I_6") (pintype "unspecified"))
      (node (ref "U305") (pin "25") (pinfunction "IOQ_25") (pintype "unspecified"))
    )
    (net (code "165") (name "PLD_DS3") (class "Default")
      (node (ref "R109D") (pin "1") (pinfunction "1_1") (pintype "input"))
      (node (ref "U109") (pin "6") (pinfunction "A4_6") (pintype "unspecified"))
      (node (ref "U202") (pin "11") (pinfunction "I_11") (pintype "unspecified"))
      (node (ref "U304") (pin "5") (pinfunction "I_5") (pintype "unspecified"))
      (node (ref "U305") (pin "26") (pinfunction "IOQ_26") (pintype "unspecified"))
    )
    (net (code "166") (name "PLD_DTACK") (class "Default")
      (node (ref "U303") (pin "9") (pinfunction "I_9") (pintype "unspecified"))
      (node (ref "U304") (pin "11") (pinfunction "I_11") (pintype "unspecified"))
      (node (ref "U306") (pin "17") (pinfunction "IOQ_17") (pintype "unspecified"))
    )
    (net (code "167") (name "PLD_FC0") (class "Default")
      (node (ref "R109F") (pin "1") (pinfunction "1_1") (pintype "input"))
      (node (ref "U109") (pin "3") (pinfunction "A1_3") (pintype "unspecified"))
      (node (ref "U202") (pin "16") (pinfunction "I_16") (pintype "unspecified"))
      (node (ref "U300") (pin "30") (pinfunction "FC0-TM0_30") (pintype "unspecified"))
    )
    (net (code "168") (name "PLD_FC1") (class "Default")
      (node (ref "R109G") (pin "1") (pinfunction "1_1") (pintype "input"))
      (node (ref "U109") (pin "2") (pinfunction "A0_2") (pintype "unspecified"))
      (node (ref "U202") (pin "13") (pinfunction "I_13") (pintype "unspecified"))
      (node (ref "U300") (pin "29") (pinfunction "FC1-TM1_29") (pintype "unspecified"))
    )
    (net (code "169") (name "PLD_FC2") (class "Default")
      (node (ref "R103A") (pin "1") (pinfunction "1_1") (pintype "input"))
      (node (ref "U103") (pin "8") (pinfunction "A6_8") (pintype "unspecified"))
      (node (ref "U203") (pin "11") (pinfunction "I_11") (pintype "unspecified"))
      (node (ref "U300") (pin "28") (pinfunction "FC2-TM2_28") (pintype "unspecified"))
    )
    (net (code "170") (name "PLD_FCS") (class "Default")
      (node (ref "FB500") (pin "2") (pinfunction "2_2") (pintype "unspecified"))
      (node (ref "U100") (pin "1") (pinfunction "LEBA_1") (pintype "unspecified"))
      (node (ref "U101") (pin "1") (pinfunction "LEBA_1") (pintype "unspecified"))
      (node (ref "U102") (pin "1") (pinfunction "LEBA_1") (pintype "unspecified"))
      (node (ref "U202") (pin "12") (pinfunction "I_12") (pintype "unspecified"))
      (node (ref "U203") (pin "12") (pinfunction "I_12") (pintype "unspecified"))
      (node (ref "U205") (pin "6") (pinfunction "I_6") (pintype "unspecified"))
      (node (ref "U207") (pin "12") (pinfunction "I_12") (pintype "unspecified"))
      (node (ref "U303") (pin "6") (pinfunction "I_6") (pintype "unspecified"))
      (node (ref "U306") (pin "4") (pinfunction "I_4") (pintype "unspecified"))
    )
    (net (code "171") (name "PLD_INT") (class "Default")
      (node (ref "U203") (pin "7") (pinfunction "I_7") (pintype "unspecified"))
      (node (ref "U207") (pin "26") (pinfunction "IOQ_26") (pintype "unspecified"))
    )
    (net (code "172") (name "PLD_INTREG") (class "Default")
      (node (ref "U203") (pin "24") (pinfunction "IOQ_24") (pintype "unspecified"))
      (node (ref "U204") (pin "11") (pinfunction "CP_11") (pintype "unspecified"))
      (node (ref "U205") (pin "11") (pinfunction "I_11") (pintype "unspecified"))
    )
    (net (code "173") (name "PLD_INTSPC") (class "Default")
      (node (ref "U202") (pin "27") (pinfunction "IOQ_27") (pintype "unspecified"))
      (node (ref "U203") (pin "16") (pinfunction "I_16") (pintype "unspecified"))
    )
    (net (code "174") (name "PLD_INTVEC") (class "Default")
      (node (ref "U203") (pin "23") (pinfunction "IOQ_23") (pintype "unspecified"))
      (node (ref "U204") (pin "1") (pinfunction "OE#_1") (pintype "unspecified"))
      (node (ref "U205") (pin "12") (pinfunction "I_12") (pintype "unspecified"))
      (node (ref "U207") (pin "11") (pinfunction "I_11") (pintype "unspecified"))
    )
    (net (code "175") (name "PLD_MTCR") (class "Default")
      (node (ref "R109E") (pin "1") (pinfunction "1_1") (pintype "input"))
      (node (ref "U109") (pin "5") (pinfunction "A3_5") (pintype "unspecified"))
      (node (ref "U203") (pin "13") (pinfunction "I_13") (pintype "unspecified"))
      (node (ref "U205") (pin "17") (pinfunction "IOQ_17") (pintype "unspecified"))
      (node (ref "U305") (pin "10") (pinfunction "I_10") (pintype "unspecified"))
      (node (ref "U306") (pin "25") (pinfunction "IOQ_25") (pintype "unspecified"))
    )
    (net (code "176") (name "PLD_MYBUS") (class "Default")
      (node (ref "U205") (pin "4") (pinfunction "I_4") (pintype "unspecified"))
      (node (ref "U303") (pin "20") (pinfunction "IOQ_20") (pintype "unspecified"))
      (node (ref "U304") (pin "13") (pinfunction "I_13") (pintype "unspecified"))
      (node (ref "U305") (pin "3") (pinfunction "I_3") (pintype "unspecified"))
      (node (ref "U306") (pin "3") (pinfunction "I_3") (pintype "unspecified"))
    )
    (net (code "177") (name "PLD_NACK") (class "Default")
      (node (ref "U205") (pin "16") (pinfunction "I_16") (pintype "unspecified"))
      (node (ref "U207") (pin "24") (pinfunction "IOQ_24") (pintype "unspecified"))
    )
    (net (code "178") (name "PLD_NOZ3") (class "Default")
      (node (ref "U205") (pin "10") (pinfunction "I_10") (pintype "unspecified"))
      (node (ref "U305") (pin "9") (pinfunction "I_9") (pintype "unspecified"))
      (node (ref "U306") (pin "20") (pinfunction "IOQ_20") (pintype "unspecified"))
    )
    (net (code "179") (name "PLD_READ") (class "Default")
      (node (ref "FB506") (pin "1") (pinfunction "1_1") (pintype "unspecified"))
      (node (ref "R103B") (pin "1") (pinfunction "1_1") (pintype "input"))
      (node (ref "U103") (pin "9") (pinfunction "A7_9") (pintype "unspecified"))
      (node (ref "U202") (pin "10") (pinfunction "I_10") (pintype "unspecified"))
      (node (ref "U203") (pin "9") (pinfunction "I_9") (pintype "unspecified"))
      (node (ref "U205") (pin "7") (pinfunction "I_7") (pintype "unspecified"))
      (node (ref "U207") (pin "7") (pinfunction "I_7") (pintype "unspecified"))
      (node (ref "U304") (pin "4") (pinfunction "I_4") (pintype "unspecified"))
      (node (ref "U305") (pin "5") (pinfunction "I_5") (pintype "unspecified"))
    )
    (net (code "180") (name "PLD_SCSI") (class "Default")
      (node (ref "U203") (pin "26") (pinfunction "IOQ_26") (pintype "unspecified"))
      (node (ref "U304") (pin "3") (pinfunction "I_3") (pintype "unspecified"))
      (node (ref "U306") (pin "7") (pinfunction "I_7") (pintype "unspecified"))
    )
    (net (code "181") (name "PLD_SID") (class "Default")
      (node (ref "U203") (pin "17") (pinfunction "IOQ_17") (pintype "unspecified"))
      (node (ref "U205") (pin "19") (pinfunction "IOQ_19") (pintype "unspecified"))
      (node (ref "U213") (pin "1") (pinfunction "OE1#_1") (pintype "unspecified"))
      (node (ref "U213") (pin "19") (pinfunction "OE2#_19") (pintype "unspecified"))
    )
    (net (code "182") (name "PLD_SIZ0") (class "Default")
      (node (ref "R300E") (pin "1") (pinfunction "1_1") (pintype "input"))
      (node (ref "U300") (pin "27") (pinfunction "SIZ0_27") (pintype "unspecified"))
      (node (ref "U304") (pin "24") (pinfunction "IOQ_24") (pintype "unspecified"))
      (node (ref "U305") (pin "7") (pinfunction "I_7") (pintype "unspecified"))
    )
    (net (code "183") (name "PLD_SIZ1") (class "Default")
      (node (ref "R300F") (pin "1") (pinfunction "1_1") (pintype "input"))
      (node (ref "U300") (pin "26") (pinfunction "SIZ1_26") (pintype "unspecified"))
      (node (ref "U304") (pin "25") (pinfunction "IOQ_25") (pintype "unspecified"))
      (node (ref "U305") (pin "6") (pinfunction "I_6") (pintype "unspecified"))
    )
    (net (code "184") (name "ROM_A15") (class "Default")
      (node (ref "J100") (pin "2") (pinfunction "2_2") (pintype "input"))
      (node (ref "U206") (pin "1") (pinfunction "VPP_1") (pintype "input"))
    )
    (net (code "185") (name "ROM_OE") (class "Default")
      (node (ref "U203") (pin "25") (pinfunction "IOQ_25") (pintype "unspecified"))
      (node (ref "U206") (pin "22") (pinfunction "OE#_22") (pintype "passive"))
      (node (ref "U207") (pin "19") (pinfunction "IOQ_19") (pintype "unspecified"))
    )
    (net (code "186") (name "SBG") (class "Default")
      (node (ref "U300") (pin "100") (pinfunction "BG/_100") (pintype "unspecified"))
      (node (ref "U303") (pin "21") (pinfunction "IOQ_21") (pintype "unspecified"))
    )
    (net (code "187") (name "SBR") (class "Default")
      (node (ref "FB503") (pin "2") (pinfunction "2_2") (pintype "unspecified"))
      (node (ref "U303") (pin "4") (pinfunction "I_4") (pintype "unspecified"))
    )
    (net (code "188") (name "SCDAT0") (class "Default")
      (node (ref "FB310K") (pin "1") (pinfunction "1_1") (pintype "unspecified"))
      (node (ref "FB311A") (pin "2") (pinfunction "2_2") (pintype "unspecified"))
      (node (ref "RP300B") (pin "5") (pinfunction "R4_5") (pintype "unspecified"))
      (node (ref "U300") (pin "131") (pinfunction "SD0/_131") (pintype "unspecified"))
      (node (ref "U311") (pin "3") (pinfunction "R2_3") (pintype "unspecified"))
    )
    (net (code "189") (name "SCDAT1") (class "Default")
      (node (ref "FB310L") (pin "1") (pinfunction "1_1") (pintype "unspecified"))
      (node (ref "FB311B") (pin "2") (pinfunction "2_2") (pintype "unspecified"))
      (node (ref "RP300B") (pin "6") (pinfunction "R5_6") (pintype "unspecified"))
      (node (ref "U300") (pin "130") (pinfunction "SD1/_130") (pintype "unspecified"))
      (node (ref "U311") (pin "4") (pinfunction "R3_4") (pintype "unspecified"))
    )
    (net (code "190") (name "SCDAT2") (class "Default")
      (node (ref "FB310M") (pin "1") (pinfunction "1_1") (pintype "unspecified"))
      (node (ref "FB311C") (pin "2") (pinfunction "2_2") (pintype "unspecified"))
      (node (ref "RP300B") (pin "7") (pinfunction "R6_7") (pintype "unspecified"))
      (node (ref "U300") (pin "129") (pinfunction "SD2/_129") (pintype "unspecified"))
      (node (ref "U311") (pin "5") (pinfunction "R4_5") (pintype "unspecified"))
    )
    (net (code "191") (name "SCDAT3") (class "Default")
      (node (ref "FB310N") (pin "1") (pinfunction "1_1") (pintype "unspecified"))
      (node (ref "FB311D") (pin "2") (pinfunction "2_2") (pintype "unspecified"))
      (node (ref "RP300A") (pin "7") (pinfunction "R6_7") (pintype "unspecified"))
      (node (ref "U300") (pin "127") (pinfunction "SD3/_127") (pintype "unspecified"))
      (node (ref "U311") (pin "6") (pinfunction "R5_6") (pintype "unspecified"))
    )
    (net (code "192") (name "SCDAT4") (class "Default")
      (node (ref "FB310O") (pin "1") (pinfunction "1_1") (pintype "unspecified"))
      (node (ref "FB311E") (pin "2") (pinfunction "2_2") (pintype "unspecified"))
      (node (ref "RP300A") (pin "6") (pinfunction "R5_6") (pintype "unspecified"))
      (node (ref "U300") (pin "126") (pinfunction "SD4/_126") (pintype "unspecified"))
      (node (ref "U310") (pin "5") (pinfunction "R4_5") (pintype "unspecified"))
    )
    (net (code "193") (name "SCDAT5") (class "Default")
      (node (ref "FB310P") (pin "1") (pinfunction "1_1") (pintype "unspecified"))
      (node (ref "FB311F") (pin "2") (pinfunction "2_2") (pintype "unspecified"))
      (node (ref "RP300A") (pin "5") (pinfunction "R4_5") (pintype "unspecified"))
      (node (ref "U300") (pin "125") (pinfunction "SD5/_125") (pintype "unspecified"))
      (node (ref "U311") (pin "10") (pinfunction "R6_10") (pintype "unspecified"))
    )
    (net (code "194") (name "SCDAT6") (class "Default")
      (node (ref "FB310Q") (pin "1") (pinfunction "1_1") (pintype "unspecified"))
      (node (ref "FB311G") (pin "2") (pinfunction "2_2") (pintype "unspecified"))
      (node (ref "RP300A") (pin "4") (pinfunction "R3_4") (pintype "unspecified"))
      (node (ref "U300") (pin "124") (pinfunction "SD6/_124") (pintype "unspecified"))
      (node (ref "U311") (pin "11") (pinfunction "R7_11") (pintype "unspecified"))
    )
    (net (code "195") (name "SCDAT7") (class "Default")
      (node (ref "FB310R") (pin "1") (pinfunction "1_1") (pintype "unspecified"))
      (node (ref "FB311H") (pin "2") (pinfunction "2_2") (pintype "unspecified"))
      (node (ref "RP300A") (pin "3") (pinfunction "R2_3") (pintype "unspecified"))
      (node (ref "U300") (pin "122") (pinfunction "SD7/_122") (pintype "unspecified"))
      (node (ref "U311") (pin "12") (pinfunction "R8_12") (pintype "unspecified"))
    )
    (net (code "196") (name "SCDATP") (class "Default")
      (node (ref "FB310J") (pin "1") (pinfunction "1_1") (pintype "unspecified"))
      (node (ref "FB311I") (pin "2") (pinfunction "2_2") (pintype "unspecified"))
      (node (ref "RP300A") (pin "2") (pinfunction "R1_2") (pintype "unspecified"))
      (node (ref "U300") (pin "121") (pinfunction "SDP/_121") (pintype "unspecified"))
      (node (ref "U311") (pin "13") (pinfunction "R9_13") (pintype "unspecified"))
    )
    (net (code "197") (name "SCSI_BUSY") (class "Default")
      (node (ref "CN309") (pin "36") (pinfunction "36_36") (pintype "unspecified"))
      (node (ref "FB311R") (pin "1") (pinfunction "1_1") (pintype "unspecified"))
      (node (ref "U307") (pin "1") (pinfunction "1A_1") (pintype "unspecified"))
      (node (ref "U307") (pin "3") (pinfunction "2A_3") (pintype "unspecified"))
    )
    (net (code "198") (name "SCSI_TERMPWR") (class "Default")
      (node (ref "CN309") (pin "26") (pinfunction "26_26") (pintype "unspecified"))
      (node (ref "CN310") (pin "38") (pinfunction "TERM_38") (pintype "unspecified"))
      (node (ref "F309A") (pin "2") (pinfunction "2_2") (pintype "unspecified"))
      (node (ref "F309B") (pin "2") (pinfunction "2_2") (pintype "unspecified"))
      (node (ref "U310") (pin "1") (pinfunction "TPWR1_1") (pintype "passive"))
      (node (ref "U310") (pin "9") (pinfunction "TPWR2_9") (pintype "passive"))
      (node (ref "U311") (pin "1") (pinfunction "TPWR1_1") (pintype "passive"))
      (node (ref "U311") (pin "9") (pinfunction "TPWR2_9") (pintype "passive"))
    )
    (net (code "199") (name "SCTRL_ACK") (class "Default")
      (node (ref "FB310G") (pin "1") (pinfunction "1_1") (pintype "unspecified"))
      (node (ref "FB311Q") (pin "2") (pinfunction "2_2") (pintype "unspecified"))
      (node (ref "RP300C") (pin "7") (pinfunction "R6_7") (pintype "unspecified"))
      (node (ref "U300") (pin "117") (pinfunction "ACK/_117") (pintype "unspecified"))
      (node (ref "U310") (pin "10") (pinfunction "R6_10") (pintype "unspecified"))
    )
    (net (code "200") (name "SCTRL_ATN") (class "Default")
      (node (ref "FB310I") (pin "1") (pinfunction "1_1") (pintype "unspecified"))
      (node (ref "FB311J") (pin "2") (pinfunction "2_2") (pintype "unspecified"))
      (node (ref "RP300C") (pin "6") (pinfunction "R5_6") (pintype "unspecified"))
      (node (ref "U300") (pin "120") (pinfunction "ATN/_120") (pintype "unspecified"))
      (node (ref "U310") (pin "6") (pinfunction "R5_6") (pintype "unspecified"))
    )
    (net (code "201") (name "SCTRL_BSY") (class "Default")
      (node (ref "FB310H") (pin "1") (pinfunction "1_1") (pintype "unspecified"))
      (node (ref "FB311R") (pin "2") (pinfunction "2_2") (pintype "unspecified"))
      (node (ref "RP300C") (pin "3") (pinfunction "R2_3") (pintype "unspecified"))
      (node (ref "U300") (pin "119") (pinfunction "BSY/_119") (pintype "unspecified"))
      (node (ref "U310") (pin "2") (pinfunction "R1_2") (pintype "unspecified"))
    )
    (net (code "202") (name "SCTRL_CD") (class "Default")
      (node (ref "FB310C") (pin "1") (pinfunction "1_1") (pintype "unspecified"))
      (node (ref "FB311M") (pin "2") (pinfunction "2_2") (pintype "unspecified"))
      (node (ref "RP300B") (pin "2") (pinfunction "R1_2") (pintype "unspecified"))
      (node (ref "U300") (pin "112") (pinfunction "C/D_112") (pintype "unspecified"))
      (node (ref "U311") (pin "2") (pinfunction "R1_2") (pintype "unspecified"))
    )
    (net (code "203") (name "SCTRL_IO") (class "Default")
      (node (ref "FB310A") (pin "1") (pinfunction "1_1") (pintype "unspecified"))
      (node (ref "FB311K") (pin "2") (pinfunction "2_2") (pintype "unspecified"))
      (node (ref "RP300B") (pin "3") (pinfunction "R2_3") (pintype "unspecified"))
      (node (ref "U300") (pin "110") (pinfunction "I/O_110") (pintype "unspecified"))
      (node (ref "U310") (pin "13") (pinfunction "R9_13") (pintype "unspecified"))
    )
    (net (code "204") (name "SCTRL_MSG") (class "Default")
      (node (ref "FB310E") (pin "1") (pinfunction "1_1") (pintype "unspecified"))
      (node (ref "FB311O") (pin "2") (pinfunction "2_2") (pintype "unspecified"))
      (node (ref "RP300B") (pin "4") (pinfunction "R3_4") (pintype "unspecified"))
      (node (ref "U300") (pin "115") (pinfunction "MSG/_115") (pintype "unspecified"))
      (node (ref "U310") (pin "12") (pinfunction "R8_12") (pintype "unspecified"))
    )
    (net (code "205") (name "SCTRL_REQ") (class "Default")
      (node (ref "FB310B") (pin "1") (pinfunction "1_1") (pintype "unspecified"))
      (node (ref "FB311L") (pin "2") (pinfunction "2_2") (pintype "unspecified"))
      (node (ref "RP300C") (pin "2") (pinfunction "R1_2") (pintype "unspecified"))
      (node (ref "U300") (pin "111") (pinfunction "REQ/_111") (pintype "unspecified"))
      (node (ref "U310") (pin "11") (pinfunction "R7_11") (pintype "unspecified"))
    )
    (net (code "206") (name "SCTRL_RST") (class "Default")
      (node (ref "FB310F") (pin "1") (pinfunction "1_1") (pintype "unspecified"))
      (node (ref "FB311P") (pin "2") (pinfunction "2_2") (pintype "unspecified"))
      (node (ref "RP300C") (pin "5") (pinfunction "R4_5") (pintype "unspecified"))
      (node (ref "U300") (pin "116") (pinfunction "RST/_116") (pintype "unspecified"))
      (node (ref "U310") (pin "4") (pinfunction "R3_4") (pintype "unspecified"))
    )
    (net (code "207") (name "SCTRL_SEL") (class "Default")
      (node (ref "FB310D") (pin "1") (pinfunction "1_1") (pintype "unspecified"))
      (node (ref "FB311N") (pin "2") (pinfunction "2_2") (pintype "unspecified"))
      (node (ref "RP300C") (pin "4") (pinfunction "R3_4") (pintype "unspecified"))
      (node (ref "U300") (pin "114") (pinfunction "SEL/_114") (pintype "unspecified"))
      (node (ref "U310") (pin "3") (pinfunction "R2_3") (pintype "unspecified"))
    )
    (net (code "208") (name "SLACK") (class "Default")
      (node (ref "U205") (pin "9") (pinfunction "I_9") (pintype "unspecified"))
      (node (ref "U300") (pin "92") (pinfunction "SLACK/_92") (pintype "unspecified"))
    )
    (net (code "209") (name "SREG") (class "Default")
      (node (ref "U300") (pin "93") (pinfunction "CS/_93") (pintype "unspecified"))
      (node (ref "U304") (pin "19") (pinfunction "IOQ_19") (pintype "unspecified"))
    )
    (net (code "210") (name "STERM") (class "Default")
      (node (ref "R300D") (pin "2") (pinfunction "2_2") (pintype "input"))
      (node (ref "U300") (pin "36") (pinfunction "STERM/-TA/_36") (pintype "unspecified"))
      (node (ref "U304") (pin "12") (pinfunction "I_12") (pintype "unspecified"))
      (node (ref "U306") (pin "19") (pinfunction "IOQ_19") (pintype "unspecified"))
    )
    (net (code "211") (name "T_GND") (class "Default")
      (node (ref "C400A") (pin "2") (pinfunction "2_2") (pintype "unspecified"))
      (node (ref "C400B") (pin "1") (pinfunction "1_1") (pintype "input"))
      (node (ref "C401A") (pin "2") (pinfunction "2_2") (pintype "unspecified"))
      (node (ref "C401B") (pin "1") (pinfunction "1_1") (pintype "input"))
      (node (ref "C402") (pin "1") (pinfunction "1_1") (pintype "input"))
      (node (ref "C403") (pin "2") (pinfunction "2_2") (pintype "unspecified"))
      (node (ref "CN400") (pin "1") (pinfunction "1_1") (pintype "unspecified"))
      (node (ref "CN400") (pin "11") (pinfunction "11_11") (pintype "unspecified"))
      (node (ref "CN400") (pin "13") (pinfunction "13_13") (pintype "unspecified"))
      (node (ref "CN400") (pin "15") (pinfunction "15_15") (pintype "unspecified"))
      (node (ref "CN400") (pin "17") (pinfunction "17_17") (pintype "unspecified"))
      (node (ref "CN400") (pin "19") (pinfunction "19_19") (pintype "unspecified"))
      (node (ref "CN400") (pin "20") (pinfunction "20_20") (pintype "unspecified"))
      (node (ref "CN400") (pin "21") (pinfunction "21_21") (pintype "unspecified"))
      (node (ref "CN400") (pin "22") (pinfunction "22_22") (pintype "unspecified"))
      (node (ref "CN400") (pin "23") (pinfunction "23_23") (pintype "unspecified"))
      (node (ref "CN400") (pin "24") (pinfunction "24_24") (pintype "unspecified"))
      (node (ref "CN400") (pin "27") (pinfunction "27_27") (pintype "unspecified"))
      (node (ref "CN400") (pin "28") (pinfunction "28_28") (pintype "unspecified"))
      (node (ref "CN400") (pin "29") (pinfunction "29_29") (pintype "unspecified"))
      (node (ref "CN400") (pin "3") (pinfunction "3_3") (pintype "unspecified"))
      (node (ref "CN400") (pin "30") (pinfunction "30_30") (pintype "unspecified"))
      (node (ref "CN400") (pin "31") (pinfunction "31_31") (pintype "unspecified"))
      (node (ref "CN400") (pin "33") (pinfunction "33_33") (pintype "unspecified"))
      (node (ref "CN400") (pin "34") (pinfunction "34_34") (pintype "unspecified"))
      (node (ref "CN400") (pin "35") (pinfunction "35_35") (pintype "unspecified"))
      (node (ref "CN400") (pin "37") (pinfunction "37_37") (pintype "unspecified"))
      (node (ref "CN400") (pin "39") (pinfunction "39_39") (pintype "unspecified"))
      (node (ref "CN400") (pin "41") (pinfunction "41_41") (pintype "unspecified"))
      (node (ref "CN400") (pin "43") (pinfunction "43_43") (pintype "unspecified"))
      (node (ref "CN400") (pin "45") (pinfunction "45_45") (pintype "unspecified"))
      (node (ref "CN400") (pin "47") (pinfunction "47_47") (pintype "unspecified"))
      (node (ref "CN400") (pin "49") (pinfunction "49_49") (pintype "unspecified"))
      (node (ref "CN400") (pin "5") (pinfunction "5_5") (pintype "unspecified"))
      (node (ref "CN400") (pin "7") (pinfunction "7_7") (pintype "unspecified"))
      (node (ref "CN400") (pin "9") (pinfunction "9_9") (pintype "unspecified"))
      (node (ref "U400") (pin "8") (pinfunction "GND_8") (pintype "passive"))
      (node (ref "U401") (pin "8") (pinfunction "GND_8") (pintype "passive"))
    )
    (net (code "212") (name "T_SCDAT0") (class "Default")
      (node (ref "CN400") (pin "2") (pinfunction "2_2") (pintype "unspecified"))
      (node (ref "U401") (pin "13") (pinfunction "R9_13") (pintype "unspecified"))
    )
    (net (code "213") (name "T_SCDAT1") (class "Default")
      (node (ref "CN400") (pin "4") (pinfunction "4_4") (pintype "unspecified"))
      (node (ref "U401") (pin "12") (pinfunction "R8_12") (pintype "unspecified"))
    )
    (net (code "214") (name "T_SCDAT2") (class "Default")
      (node (ref "CN400") (pin "6") (pinfunction "6_6") (pintype "unspecified"))
      (node (ref "U401") (pin "11") (pinfunction "R7_11") (pintype "unspecified"))
    )
    (net (code "215") (name "T_SCDAT3") (class "Default")
      (node (ref "CN400") (pin "8") (pinfunction "8_8") (pintype "unspecified"))
      (node (ref "U401") (pin "10") (pinfunction "R6_10") (pintype "unspecified"))
    )
    (net (code "216") (name "T_SCDAT4") (class "Default")
      (node (ref "CN400") (pin "10") (pinfunction "10_10") (pintype "unspecified"))
      (node (ref "U401") (pin "6") (pinfunction "R5_6") (pintype "unspecified"))
    )
    (net (code "217") (name "T_SCDAT5") (class "Default")
      (node (ref "CN400") (pin "12") (pinfunction "12_12") (pintype "unspecified"))
      (node (ref "U401") (pin "5") (pinfunction "R4_5") (pintype "unspecified"))
    )
    (net (code "218") (name "T_SCDAT6") (class "Default")
      (node (ref "CN400") (pin "14") (pinfunction "14_14") (pintype "unspecified"))
      (node (ref "U401") (pin "4") (pinfunction "R3_4") (pintype "unspecified"))
    )
    (net (code "219") (name "T_SCDAT7") (class "Default")
      (node (ref "CN400") (pin "16") (pinfunction "16_16") (pintype "unspecified"))
      (node (ref "U401") (pin "3") (pinfunction "R2_3") (pintype "unspecified"))
    )
    (net (code "220") (name "T_SCDATP") (class "Default")
      (node (ref "CN400") (pin "18") (pinfunction "18_18") (pintype "unspecified"))
      (node (ref "U401") (pin "2") (pinfunction "R1_2") (pintype "unspecified"))
    )
    (net (code "221") (name "T_SCSI_TERMPWR") (class "Default")
      (node (ref "C402") (pin "2") (pinfunction "2_2") (pintype "input"))
      (node (ref "C403") (pin "1") (pinfunction "1_1") (pintype "unspecified"))
      (node (ref "CN400") (pin "26") (pinfunction "26_26") (pintype "unspecified"))
      (node (ref "U400") (pin "1") (pinfunction "TPWR1_1") (pintype "passive"))
      (node (ref "U400") (pin "9") (pinfunction "TPWR2_9") (pintype "passive"))
      (node (ref "U401") (pin "1") (pinfunction "TPWR1_1") (pintype "passive"))
      (node (ref "U401") (pin "9") (pinfunction "TPWR2_9") (pintype "passive"))
    )
    (net (code "222") (name "T_SCTRL_ACK") (class "Default")
      (node (ref "CN400") (pin "38") (pinfunction "38_38") (pintype "unspecified"))
      (node (ref "U400") (pin "11") (pinfunction "R7_11") (pintype "unspecified"))
    )
    (net (code "223") (name "T_SCTRL_ATN") (class "Default")
      (node (ref "CN400") (pin "32") (pinfunction "32_32") (pintype "unspecified"))
      (node (ref "U400") (pin "13") (pinfunction "R9_13") (pintype "unspecified"))
    )
    (net (code "224") (name "T_SCTRL_BSY") (class "Default")
      (node (ref "CN400") (pin "36") (pinfunction "36_36") (pintype "unspecified"))
      (node (ref "U400") (pin "12") (pinfunction "R8_12") (pintype "unspecified"))
    )
    (net (code "225") (name "T_SCTRL_CD") (class "Default")
      (node (ref "CN400") (pin "46") (pinfunction "46_46") (pintype "unspecified"))
      (node (ref "U400") (pin "4") (pinfunction "R3_4") (pintype "unspecified"))
    )
    (net (code "226") (name "T_SCTRL_IO") (class "Default")
      (node (ref "CN400") (pin "50") (pinfunction "50_50") (pintype "unspecified"))
      (node (ref "U400") (pin "2") (pinfunction "R1_2") (pintype "unspecified"))
    )
    (net (code "227") (name "T_SCTRL_MSG") (class "Default")
      (node (ref "CN400") (pin "42") (pinfunction "42_42") (pintype "unspecified"))
      (node (ref "U400") (pin "6") (pinfunction "R5_6") (pintype "unspecified"))
    )
    (net (code "228") (name "T_SCTRL_REQ") (class "Default")
      (node (ref "CN400") (pin "48") (pinfunction "48_48") (pintype "unspecified"))
      (node (ref "U400") (pin "3") (pinfunction "R2_3") (pintype "unspecified"))
    )
    (net (code "229") (name "T_SCTRL_RST") (class "Default")
      (node (ref "CN400") (pin "40") (pinfunction "40_40") (pintype "unspecified"))
      (node (ref "U400") (pin "10") (pinfunction "R6_10") (pintype "unspecified"))
    )
    (net (code "230") (name "T_SCTRL_SEL") (class "Default")
      (node (ref "CN400") (pin "44") (pinfunction "44_44") (pintype "unspecified"))
      (node (ref "U400") (pin "5") (pinfunction "R4_5") (pintype "unspecified"))
    )
    (net (code "231") (name "V5") (class "Default")
      (node (ref "C1") (pin "05") (pinfunction "+5V_05") (pintype "bidirectional"))
      (node (ref "C1") (pin "06") (pinfunction "+5V_06") (pintype "bidirectional"))
      (node (ref "C10") (pin "1") (pinfunction "1_1") (pintype "input"))
      (node (ref "C100A") (pin "1") (pinfunction "1_1") (pintype "input"))
      (node (ref "C101A") (pin "1") (pinfunction "1_1") (pintype "input"))
      (node (ref "C102A") (pin "1") (pinfunction "1_1") (pintype "input"))
      (node (ref "C103A") (pin "1") (pinfunction "1_1") (pintype "input"))
      (node (ref "C105A") (pin "1") (pinfunction "1_1") (pintype "input"))
      (node (ref "C106A") (pin "2") (pinfunction "2_2") (pintype "input"))
      (node (ref "C107A") (pin "1") (pinfunction "1_1") (pintype "input"))
      (node (ref "C108A") (pin "1") (pinfunction "1_1") (pintype "input"))
      (node (ref "C109A") (pin "1") (pinfunction "1_1") (pintype "input"))
      (node (ref "C11") (pin "1") (pinfunction "1_1") (pintype "input"))
      (node (ref "C12") (pin "1") (pinfunction "1_1") (pintype "input"))
      (node (ref "C13") (pin "1") (pinfunction "1_1") (pintype "input"))
      (node (ref "C1A") (pin "2") (pinfunction "2_2") (pintype "input"))
      (node (ref "C1B") (pin "1") (pinfunction "1_1") (pintype "input"))
      (node (ref "C200A") (pin "2") (pinfunction "2_2") (pintype "input"))
      (node (ref "C201A") (pin "1") (pinfunction "1_1") (pintype "input"))
      (node (ref "C202A") (pin "1") (pinfunction "1_1") (pintype "input"))
      (node (ref "C203A") (pin "1") (pinfunction "1_1") (pintype "input"))
      (node (ref "C204A") (pin "2") (pinfunction "2_2") (pintype "input"))
      (node (ref "C205A") (pin "1") (pinfunction "1_1") (pintype "input"))
      (node (ref "C206A") (pin "2") (pinfunction "2_2") (pintype "input"))
      (node (ref "C207A") (pin "1") (pinfunction "1_1") (pintype "input"))
      (node (ref "C212A") (pin "1") (pinfunction "1_1") (pintype "input"))
      (node (ref "C300A") (pin "1") (pinfunction "1_1") (pintype "input"))
      (node (ref "C300B") (pin "1") (pinfunction "1_1") (pintype "input"))
      (node (ref "C300C") (pin "1") (pinfunction "1_1") (pintype "input"))
      (node (ref "C300D") (pin "2") (pinfunction "2_2") (pintype "input"))
      (node (ref "C300E") (pin "1") (pinfunction "1_1") (pintype "input"))
      (node (ref "C300F") (pin "1") (pinfunction "1_1") (pintype "input"))
      (node (ref "C300G") (pin "1") (pinfunction "1_1") (pintype "input"))
      (node (ref "C300H") (pin "2") (pinfunction "2_2") (pintype "input"))
      (node (ref "C300I") (pin "1") (pinfunction "1_1") (pintype "input"))
      (node (ref "C301A") (pin "2") (pinfunction "2_2") (pintype "input"))
      (node (ref "C302A") (pin "1") (pinfunction "1_1") (pintype "input"))
      (node (ref "C303A") (pin "2") (pinfunction "2_2") (pintype "input"))
      (node (ref "C304A") (pin "1") (pinfunction "1_1") (pintype "input"))
      (node (ref "C305A") (pin "1") (pinfunction "1_1") (pintype "input"))
      (node (ref "C306A") (pin "1") (pinfunction "1_1") (pintype "input"))
      (node (ref "C307A") (pin "2") (pinfunction "2_2") (pintype "input"))
      (node (ref "CN2") (pin "4") (pinfunction "4_4") (pintype "unspecified"))
      (node (ref "CN3") (pin "1") (pinfunction "5V_1") (pintype "unspecified"))
      (node (ref "CN308") (pin "2") (pinfunction "2_2") (pintype "input"))
      (node (ref "CN351") (pin "2") (pinfunction "2_2") (pintype "input"))
      (node (ref "D309A") (pin "2") (pinfunction "A_2") (pintype "unspecified"))
      (node (ref "J100") (pin "1") (pinfunction "1_1") (pintype "input"))
      (node (ref "R100A") (pin "2") (pinfunction "2_2") (pintype "input"))
      (node (ref "R103A") (pin "2") (pinfunction "2_2") (pintype "input"))
      (node (ref "R103B") (pin "2") (pinfunction "2_2") (pintype "input"))
      (node (ref "R109A") (pin "2") (pinfunction "2_2") (pintype "input"))
      (node (ref "R109B") (pin "2") (pinfunction "2_2") (pintype "input"))
      (node (ref "R109C") (pin "2") (pinfunction "2_2") (pintype "input"))
      (node (ref "R109D") (pin "2") (pinfunction "2_2") (pintype "input"))
      (node (ref "R109E") (pin "2") (pinfunction "2_2") (pintype "input"))
      (node (ref "R109F") (pin "2") (pinfunction "2_2") (pintype "input"))
      (node (ref "R109G") (pin "2") (pinfunction "2_2") (pintype "input"))
      (node (ref "R200A") (pin "2") (pinfunction "2_2") (pintype "input"))
      (node (ref "R200B") (pin "2") (pinfunction "2_2") (pintype "input"))
      (node (ref "R200C") (pin "2") (pinfunction "2_2") (pintype "input"))
      (node (ref "R200D") (pin "2") (pinfunction "2_2") (pintype "input"))
      (node (ref "R200E") (pin "2") (pinfunction "2_2") (pintype "input"))
      (node (ref "R200F") (pin "2") (pinfunction "2_2") (pintype "input"))
      (node (ref "R200G") (pin "2") (pinfunction "2_2") (pintype "input"))
      (node (ref "R200H") (pin "2") (pinfunction "2_2") (pintype "input"))
      (node (ref "R212A") (pin "1") (pinfunction "1_1") (pintype "input"))
      (node (ref "R212B") (pin "2") (pinfunction "2_2") (pintype "input"))
      (node (ref "R212C") (pin "2") (pinfunction "2_2") (pintype "input"))
      (node (ref "R212D") (pin "2") (pinfunction "2_2") (pintype "input"))
      (node (ref "R212E") (pin "1") (pinfunction "1_1") (pintype "input"))
      (node (ref "R212F") (pin "1") (pinfunction "1_1") (pintype "input"))
      (node (ref "R212G") (pin "1") (pinfunction "1_1") (pintype "input"))
      (node (ref "R212H") (pin "1") (pinfunction "1_1") (pintype "input"))
      (node (ref "R300A") (pin "2") (pinfunction "2_2") (pintype "input"))
      (node (ref "R300B") (pin "1") (pinfunction "1_1") (pintype "input"))
      (node (ref "R300C") (pin "2") (pinfunction "2_2") (pintype "input"))
      (node (ref "R300D") (pin "1") (pinfunction "1_1") (pintype "input"))
      (node (ref "R300E") (pin "2") (pinfunction "2_2") (pintype "input"))
      (node (ref "R300F") (pin "2") (pinfunction "2_2") (pintype "input"))
      (node (ref "R300G") (pin "2") (pinfunction "2_2") (pintype "input"))
      (node (ref "R300H") (pin "2") (pinfunction "2_2") (pintype "input"))
      (node (ref "R300I") (pin "2") (pinfunction "2_2") (pintype "input"))
      (node (ref "R300J") (pin "2") (pinfunction "2_2") (pintype "input"))
      (node (ref "R300K") (pin "2") (pinfunction "2_2") (pintype "input"))
      (node (ref "R300L") (pin "2") (pinfunction "2_2") (pintype "input"))
      (node (ref "R300M") (pin "1") (pinfunction "1_1") (pintype "input"))
      (node (ref "R300N") (pin "2") (pinfunction "2_2") (pintype "input"))
      (node (ref "R300O") (pin "2") (pinfunction "2_2") (pintype "input"))
      (node (ref "R300P") (pin "2") (pinfunction "2_2") (pintype "input"))
      (node (ref "R307A") (pin "2") (pinfunction "2_2") (pintype "input"))
      (node (ref "R307B") (pin "1") (pinfunction "1_1") (pintype "input"))
      (node (ref "RP300A") (pin "8") (pinfunction "COM2_8") (pintype "unspecified"))
      (node (ref "RP300B") (pin "8") (pinfunction "COM2_8") (pintype "unspecified"))
      (node (ref "RP300C") (pin "8") (pinfunction "COM2_8") (pintype "unspecified"))
      (node (ref "U100") (pin "24") (pinfunction "VCC_24") (pintype "passive"))
      (node (ref "U101") (pin "24") (pinfunction "VCC_24") (pintype "passive"))
      (node (ref "U102") (pin "24") (pinfunction "VCC_24") (pintype "passive"))
      (node (ref "U103") (pin "20") (pinfunction "VCC_20") (pintype "unspecified"))
      (node (ref "U105") (pin "24") (pinfunction "VCC_24") (pintype "passive"))
      (node (ref "U106") (pin "24") (pinfunction "VCC_24") (pintype "passive"))
      (node (ref "U107") (pin "24") (pinfunction "VCC_24") (pintype "passive"))
      (node (ref "U108") (pin "24") (pinfunction "VCC_24") (pintype "passive"))
      (node (ref "U109") (pin "20") (pinfunction "VCC_20") (pintype "unspecified"))
      (node (ref "U200") (pin "20") (pinfunction "VCC_20") (pintype "unspecified"))
      (node (ref "U201") (pin "20") (pinfunction "VCC_20") (pintype "unspecified"))
      (node (ref "U202") (pin "28") (pinfunction "VCC_28") (pintype "unspecified"))
      (node (ref "U203") (pin "28") (pinfunction "VCC_28") (pintype "unspecified"))
      (node (ref "U204") (pin "20") (pinfunction "VCC_20") (pintype "unspecified"))
      (node (ref "U205") (pin "28") (pinfunction "VCC_28") (pintype "unspecified"))
      (node (ref "U206") (pin "28") (pinfunction "VCC_28") (pintype "output"))
      (node (ref "U207") (pin "28") (pinfunction "VCC_28") (pintype "unspecified"))
      (node (ref "U213") (pin "20") (pinfunction "VCC_20") (pintype "unspecified"))
      (node (ref "U300") (pin "139") (pinfunction "Vdd_139") (pintype "unspecified"))
      (node (ref "U300") (pin "153") (pinfunction "Vdd_153") (pintype "unspecified"))
      (node (ref "U300") (pin "19") (pinfunction "Vdd_19") (pintype "unspecified"))
      (node (ref "U300") (pin "39") (pinfunction "Vdd_39") (pintype "unspecified"))
      (node (ref "U300") (pin "40") (pinfunction "HALT/-TIP/_40") (pintype "unspecified"))
      (node (ref "U300") (pin "49") (pinfunction "Vdd_49") (pintype "unspecified"))
      (node (ref "U300") (pin "6") (pinfunction "Vdd_6") (pintype "unspecified"))
      (node (ref "U300") (pin "64") (pinfunction "Vdd_64") (pintype "unspecified"))
      (node (ref "U300") (pin "79") (pinfunction "Vdd_79") (pintype "unspecified"))
      (node (ref "U300") (pin "90") (pinfunction "BIG_LIT/_90") (pintype "unspecified"))
      (node (ref "U300") (pin "91") (pinfunction "BS_91") (pintype "unspecified"))
      (node (ref "U300") (pin "95") (pinfunction "BOFF/_95") (pintype "unspecified"))
      (node (ref "U300") (pin "99") (pinfunction "Vdd_99") (pintype "unspecified"))
      (node (ref "U301") (pin "14") (pinfunction "Vcc_14") (pintype "unspecified"))
      (node (ref "U302") (pin "1") (pinfunction "RD0#_1") (pintype "unspecified"))
      (node (ref "U302") (pin "10") (pinfunction "SD1#_10") (pintype "unspecified"))
      (node (ref "U302") (pin "11") (pinfunction "CP1_11") (pintype "unspecified"))
      (node (ref "U302") (pin "12") (pinfunction "D1_12") (pintype "unspecified"))
      (node (ref "U302") (pin "13") (pinfunction "RD1#_13") (pintype "unspecified"))
      (node (ref "U302") (pin "14") (pinfunction "VCC_14") (pintype "unspecified"))
      (node (ref "U302") (pin "4") (pinfunction "SD0#_4") (pintype "unspecified"))
      (node (ref "U303") (pin "28") (pinfunction "VCC_28") (pintype "unspecified"))
      (node (ref "U304") (pin "28") (pinfunction "VCC_28") (pintype "unspecified"))
      (node (ref "U305") (pin "28") (pinfunction "VCC_28") (pintype "unspecified"))
      (node (ref "U306") (pin "28") (pinfunction "VCC_28") (pintype "unspecified"))
      (node (ref "U307") (pin "14") (pinfunction "VCC_14") (pintype "unspecified"))
    )
    (net (code "232") (name "V12") (class "Default")
      (node (ref "C1") (pin "10") (pinfunction "+12V_10") (pintype "bidirectional"))
      (node (ref "C1C") (pin "1") (pinfunction "1_1") (pintype "input"))
      (node (ref "CN2") (pin "1") (pinfunction "1_1") (pintype "unspecified"))
      (node (ref "CN3") (pin "4") (pinfunction "12V_4") (pintype "unspecified"))
      (node (ref "CN4") (pin "2") (pinfunction "2_2") (pintype "unspecified"))
    )
    (net (code "233") (name "Z2D") (class "Default")
      (node (ref "FB504") (pin "2") (pinfunction "2_2") (pintype "unspecified"))
      (node (ref "U105") (pin "23") (pinfunction "CEBA_23") (pintype "unspecified"))
      (node (ref "U106") (pin "23") (pinfunction "CEBA_23") (pintype "unspecified"))
      (node (ref "U107") (pin "23") (pinfunction "CEBA_23") (pintype "unspecified"))
      (node (ref "U108") (pin "23") (pinfunction "CEBA_23") (pintype "unspecified"))
    )
    (net (code "234") (name "Z_7M") (class "Default")
      (node (ref "C1") (pin "92") (pinfunction "7M_Clock_92") (pintype "bidirectional"))
      (node (ref "U303") (pin "2") (pinfunction "CLK/I_2") (pintype "unspecified"))
    )
    (net (code "235") (name "Z_A2") (class "Default")
      (node (ref "C1") (pin "27") (pinfunction "A2_27") (pintype "output"))
      (node (ref "U103") (pin "13") (pinfunction "B5_13") (pintype "unspecified"))
    )
    (net (code "236") (name "Z_A3") (class "Default")
      (node (ref "C1") (pin "26") (pinfunction "A3_26") (pintype "bidirectional"))
      (node (ref "U103") (pin "14") (pinfunction "B4_14") (pintype "unspecified"))
    )
    (net (code "237") (name "Z_A4") (class "Default")
      (node (ref "C1") (pin "24") (pinfunction "A4_24") (pintype "bidirectional"))
      (node (ref "U103") (pin "15") (pinfunction "B3_15") (pintype "unspecified"))
    )
    (net (code "238") (name "Z_A5") (class "Default")
      (node (ref "C1") (pin "21") (pinfunction "A5_21") (pintype "output"))
      (node (ref "U103") (pin "16") (pinfunction "B2_16") (pintype "unspecified"))
    )
    (net (code "239") (name "Z_A6") (class "Default")
      (node (ref "C1") (pin "23") (pinfunction "A6_23") (pintype "output"))
      (node (ref "U103") (pin "17") (pinfunction "B1_17") (pintype "unspecified"))
    )
    (net (code "240") (name "Z_A7") (class "Default")
      (node (ref "C1") (pin "28") (pinfunction "A7_28") (pintype "bidirectional"))
      (node (ref "U103") (pin "18") (pinfunction "B0_18") (pintype "unspecified"))
    )
    (net (code "241") (name "Z_A8D0") (class "Default")
      (node (ref "C1") (pin "30") (pinfunction "A8+D0,A8_30") (pintype "bidirectional"))
      (node (ref "U102") (pin "15") (pinfunction "B7_15") (pintype "bidirectional"))
      (node (ref "U107") (pin "15") (pinfunction "B7_15") (pintype "bidirectional"))
    )
    (net (code "242") (name "Z_A9D1") (class "Default")
      (node (ref "C1") (pin "32") (pinfunction "A9+D1,A9_32") (pintype "bidirectional"))
      (node (ref "U102") (pin "16") (pinfunction "B6_16") (pintype "bidirectional"))
      (node (ref "U107") (pin "16") (pinfunction "B6_16") (pintype "bidirectional"))
    )
    (net (code "243") (name "Z_A10D2") (class "Default")
      (node (ref "C1") (pin "34") (pinfunction "A10+D2,A10_34") (pintype "bidirectional"))
      (node (ref "U102") (pin "17") (pinfunction "B5_17") (pintype "bidirectional"))
      (node (ref "U107") (pin "17") (pinfunction "B5_17") (pintype "bidirectional"))
    )
    (net (code "244") (name "Z_A11D3") (class "Default")
      (node (ref "C1") (pin "36") (pinfunction "A11+D3,A11_36") (pintype "bidirectional"))
      (node (ref "U102") (pin "18") (pinfunction "B4_18") (pintype "bidirectional"))
      (node (ref "U107") (pin "18") (pinfunction "B4_18") (pintype "bidirectional"))
    )
    (net (code "245") (name "Z_A12D4") (class "Default")
      (node (ref "C1") (pin "38") (pinfunction "A12+D4,A12_38") (pintype "bidirectional"))
      (node (ref "U102") (pin "19") (pinfunction "B3_19") (pintype "bidirectional"))
      (node (ref "U107") (pin "19") (pinfunction "B3_19") (pintype "bidirectional"))
    )
    (net (code "246") (name "Z_A13D5") (class "Default")
      (node (ref "C1") (pin "39") (pinfunction "A13+D5,A13_39") (pintype "unspecified"))
      (node (ref "U102") (pin "20") (pinfunction "B2_20") (pintype "bidirectional"))
      (node (ref "U107") (pin "20") (pinfunction "B2_20") (pintype "bidirectional"))
    )
    (net (code "247") (name "Z_A14D6") (class "Default")
      (node (ref "C1") (pin "41") (pinfunction "A14+D6,A14_41") (pintype "unspecified"))
      (node (ref "U102") (pin "21") (pinfunction "B1_21") (pintype "bidirectional"))
      (node (ref "U107") (pin "21") (pinfunction "B1_21") (pintype "bidirectional"))
    )
    (net (code "248") (name "Z_A15D7") (class "Default")
      (node (ref "C1") (pin "43") (pinfunction "A15+D7,A15_43") (pintype "unspecified"))
      (node (ref "U102") (pin "22") (pinfunction "B0_22") (pintype "bidirectional"))
      (node (ref "U107") (pin "22") (pinfunction "B0_22") (pintype "bidirectional"))
    )
    (net (code "249") (name "Z_A16D8") (class "Default")
      (node (ref "C1") (pin "45") (pinfunction "A16+D8,A16_45") (pintype "unspecified"))
      (node (ref "U101") (pin "15") (pinfunction "B7_15") (pintype "bidirectional"))
      (node (ref "U106") (pin "15") (pinfunction "B7_15") (pintype "bidirectional"))
    )
    (net (code "250") (name "Z_A17D9") (class "Default")
      (node (ref "C1") (pin "47") (pinfunction "A17+D9,A17_47") (pintype "unspecified"))
      (node (ref "U101") (pin "16") (pinfunction "B6_16") (pintype "bidirectional"))
      (node (ref "U106") (pin "16") (pinfunction "B6_16") (pintype "bidirectional"))
    )
    (net (code "251") (name "Z_A18D10") (class "Default")
      (node (ref "C1") (pin "52") (pinfunction "A18+D10,A18_52") (pintype "bidirectional"))
      (node (ref "U101") (pin "17") (pinfunction "B5_17") (pintype "bidirectional"))
      (node (ref "U106") (pin "17") (pinfunction "B5_17") (pintype "bidirectional"))
    )
    (net (code "252") (name "Z_A19D11") (class "Default")
      (node (ref "C1") (pin "54") (pinfunction "A19+D11,A19_54") (pintype "bidirectional"))
      (node (ref "U101") (pin "18") (pinfunction "B4_18") (pintype "bidirectional"))
      (node (ref "U106") (pin "18") (pinfunction "B4_18") (pintype "bidirectional"))
    )
    (net (code "253") (name "Z_A20D12") (class "Default")
      (node (ref "C1") (pin "56") (pinfunction "A20+D12,A20_56") (pintype "bidirectional"))
      (node (ref "U101") (pin "19") (pinfunction "B3_19") (pintype "bidirectional"))
      (node (ref "U106") (pin "19") (pinfunction "B3_19") (pintype "bidirectional"))
    )
    (net (code "254") (name "Z_A21D13") (class "Default")
      (node (ref "C1") (pin "58") (pinfunction "A21+D13,A21_58") (pintype "bidirectional"))
      (node (ref "U101") (pin "20") (pinfunction "B2_20") (pintype "bidirectional"))
      (node (ref "U106") (pin "20") (pinfunction "B2_20") (pintype "bidirectional"))
    )
    (net (code "255") (name "Z_A22D14") (class "Default")
      (node (ref "C1") (pin "57") (pinfunction "A22+D14,A22_57") (pintype "bidirectional"))
      (node (ref "U101") (pin "21") (pinfunction "B1_21") (pintype "bidirectional"))
      (node (ref "U106") (pin "21") (pinfunction "B1_21") (pintype "bidirectional"))
    )
    (net (code "256") (name "Z_A23D15") (class "Default")
      (node (ref "C1") (pin "59") (pinfunction "A23+D15,A23_59") (pintype "output"))
      (node (ref "U101") (pin "22") (pinfunction "B0_22") (pintype "bidirectional"))
      (node (ref "U106") (pin "22") (pinfunction "B0_22") (pintype "bidirectional"))
    )
    (net (code "257") (name "Z_A24D24") (class "Default")
      (node (ref "C1") (pin "80") (pinfunction "A24+D24,D8_80") (pintype "unspecified"))
      (node (ref "U100") (pin "15") (pinfunction "B7_15") (pintype "bidirectional"))
      (node (ref "U105") (pin "22") (pinfunction "B0_22") (pintype "bidirectional"))
    )
    (net (code "258") (name "Z_A25D25") (class "Default")
      (node (ref "C1") (pin "78") (pinfunction "A25+D25,D9_78") (pintype "unspecified"))
      (node (ref "U100") (pin "16") (pinfunction "B6_16") (pintype "bidirectional"))
      (node (ref "U105") (pin "21") (pinfunction "B1_21") (pintype "bidirectional"))
    )
    (net (code "259") (name "Z_A26D26") (class "Default")
      (node (ref "C1") (pin "76") (pinfunction "A26+D26,D10_76") (pintype "unspecified"))
      (node (ref "U100") (pin "17") (pinfunction "B5_17") (pintype "bidirectional"))
      (node (ref "U105") (pin "20") (pinfunction "B2_20") (pintype "bidirectional"))
    )
    (net (code "260") (name "Z_A27D27") (class "Default")
      (node (ref "C1") (pin "71") (pinfunction "A27+D27,D11_71") (pintype "unspecified"))
      (node (ref "U100") (pin "18") (pinfunction "B4_18") (pintype "bidirectional"))
      (node (ref "U105") (pin "19") (pinfunction "B3_19") (pintype "bidirectional"))
    )
    (net (code "261") (name "Z_A28D28") (class "Default")
      (node (ref "C1") (pin "69") (pinfunction "A28+D28,D12_69") (pintype "unspecified"))
      (node (ref "U100") (pin "19") (pinfunction "B3_19") (pintype "bidirectional"))
      (node (ref "U105") (pin "18") (pinfunction "B4_18") (pintype "bidirectional"))
    )
    (net (code "262") (name "Z_A29D29") (class "Default")
      (node (ref "C1") (pin "67") (pinfunction "A29+D29,D13_67") (pintype "unspecified"))
      (node (ref "U100") (pin "20") (pinfunction "B2_20") (pintype "bidirectional"))
      (node (ref "U105") (pin "17") (pinfunction "B5_17") (pintype "bidirectional"))
    )
    (net (code "263") (name "Z_A30D30") (class "Default")
      (node (ref "C1") (pin "65") (pinfunction "A30+D30,D14_65") (pintype "unspecified"))
      (node (ref "U100") (pin "21") (pinfunction "B1_21") (pintype "bidirectional"))
      (node (ref "U105") (pin "16") (pinfunction "B6_16") (pintype "bidirectional"))
    )
    (net (code "264") (name "Z_A31D31") (class "Default")
      (node (ref "C1") (pin "63") (pinfunction "A31+D31,D15_63") (pintype "bidirectional"))
      (node (ref "U100") (pin "22") (pinfunction "B0_22") (pintype "bidirectional"))
      (node (ref "U105") (pin "15") (pinfunction "B7_15") (pintype "bidirectional"))
    )
    (net (code "265") (name "Z_BERR") (class "Default")
      (node (ref "C1") (pin "46") (pinfunction "/BERR_46") (pintype "bidirectional"))
      (node (ref "U307") (pin "5") (pinfunction "3A_5") (pintype "unspecified"))
    )
    (net (code "266") (name "Z_BGn") (class "Default")
      (node (ref "C1") (pin "64") (pinfunction "/BGn_64") (pintype "bidirectional"))
      (node (ref "U303") (pin "5") (pinfunction "I_5") (pintype "unspecified"))
    )
    (net (code "267") (name "Z_BRn") (class "Default")
      (node (ref "C1") (pin "60") (pinfunction "/BRn_60") (pintype "bidirectional"))
      (node (ref "U303") (pin "25") (pinfunction "IOQ_25") (pintype "unspecified"))
    )
    (net (code "268") (name "Z_CFGIN") (class "Default")
      (node (ref "C1") (pin "12") (pinfunction "/CFGINn_12") (pintype "bidirectional"))
      (node (ref "U202") (pin "18") (pinfunction "IOQ_18") (pintype "unspecified"))
    )
    (net (code "269") (name "Z_CFGOUT") (class "Default")
      (node (ref "C1") (pin "11") (pinfunction "/CFGOUTn_11") (pintype "unspecified"))
      (node (ref "U200") (pin "1") (pinfunction "OE#_1") (pintype "unspecified"))
      (node (ref "U202") (pin "21") (pinfunction "IOQ_21") (pintype "unspecified"))
      (node (ref "U205") (pin "13") (pinfunction "I_13") (pintype "unspecified"))
      (node (ref "U207") (pin "16") (pinfunction "I_16") (pintype "unspecified"))
    )
    (net (code "270") (name "Z_CINH") (class "Default")
      (node (ref "C1") (pin "17") (pinfunction "/CINH,/OVR_17") (pintype "bidirectional"))
      (node (ref "U202") (pin "24") (pinfunction "IOQ_24") (pintype "unspecified"))
    )
    (net (code "271") (name "Z_D16") (class "Default")
      (node (ref "C1") (pin "75") (pinfunction "RSVD+D16,D0_75") (pintype "unspecified"))
      (node (ref "U108") (pin "22") (pinfunction "B0_22") (pintype "bidirectional"))
    )
    (net (code "272") (name "Z_D17") (class "Default")
      (node (ref "C1") (pin "77") (pinfunction "RSVD+D17,D1_77") (pintype "unspecified"))
      (node (ref "U108") (pin "21") (pinfunction "B1_21") (pintype "bidirectional"))
    )
    (net (code "273") (name "Z_D18") (class "Default")
      (node (ref "C1") (pin "79") (pinfunction "RSVD+D18,D2_79") (pintype "output"))
      (node (ref "U108") (pin "20") (pinfunction "B2_20") (pintype "bidirectional"))
    )
    (net (code "274") (name "Z_D19") (class "Default")
      (node (ref "C1") (pin "81") (pinfunction "RSVD+D19,D3_81") (pintype "unspecified"))
      (node (ref "U108") (pin "19") (pinfunction "B3_19") (pintype "bidirectional"))
    )
    (net (code "275") (name "Z_D20") (class "Default")
      (node (ref "C1") (pin "83") (pinfunction "RSVD+D20,D4_83") (pintype "output"))
      (node (ref "U108") (pin "18") (pinfunction "B4_18") (pintype "bidirectional"))
    )
    (net (code "276") (name "Z_D21") (class "Default")
      (node (ref "C1") (pin "86") (pinfunction "RSVD+D21,D5_86") (pintype "bidirectional"))
      (node (ref "U108") (pin "17") (pinfunction "B5_17") (pintype "bidirectional"))
    )
    (net (code "277") (name "Z_D22") (class "Default")
      (node (ref "C1") (pin "84") (pinfunction "RSVD+D22,D6_84") (pintype "output"))
      (node (ref "U108") (pin "16") (pinfunction "B6_16") (pintype "bidirectional"))
    )
    (net (code "278") (name "Z_D23") (class "Default")
      (node (ref "C1") (pin "82") (pinfunction "RSVD+D23,D7_82") (pintype "bidirectional"))
      (node (ref "U108") (pin "15") (pinfunction "B7_15") (pintype "bidirectional"))
    )
    (net (code "279") (name "Z_DOE") (class "Default")
      (node (ref "C1") (pin "93") (pinfunction "DOE_93") (pintype "unspecified"))
      (node (ref "U109") (pin "16") (pinfunction "B2_16") (pintype "unspecified"))
    )
    (net (code "280") (name "Z_DS0") (class "Default")
      (node (ref "C1") (pin "51") (pinfunction "/DS0,/VMA_51") (pintype "unspecified"))
      (node (ref "U109") (pin "11") (pinfunction "B7_11") (pintype "unspecified"))
    )
    (net (code "281") (name "Z_DS1") (class "Default")
      (node (ref "C1") (pin "98") (pinfunction "/DS1,NC_98") (pintype "bidirectional"))
      (node (ref "U109") (pin "12") (pinfunction "B6_12") (pintype "unspecified"))
    )
    (net (code "282") (name "Z_DS2") (class "Default")
      (node (ref "C1") (pin "70") (pinfunction "/DS2,/LDS_70") (pintype "unspecified"))
      (node (ref "FB508") (pin "2") (pinfunction "2_2") (pintype "unspecified"))
    )
    (net (code "283") (name "Z_DS3") (class "Default")
      (node (ref "C1") (pin "72") (pinfunction "/DS3,/UDS_72") (pintype "unspecified"))
      (node (ref "FB507") (pin "2") (pinfunction "2_2") (pintype "unspecified"))
    )
    (net (code "284") (name "Z_DTACK") (class "Default")
      (node (ref "C1") (pin "66") (pinfunction "/DTACK_66") (pintype "unspecified"))
      (node (ref "C306B") (pin "1") (pinfunction "1_1") (pintype "input"))
      (node (ref "U205") (pin "20") (pinfunction "IOQ_20") (pintype "unspecified"))
      (node (ref "U306") (pin "9") (pinfunction "I_9") (pintype "unspecified"))
    )
    (net (code "285") (name "Z_FC0") (class "Default")
      (node (ref "C1") (pin "31") (pinfunction "FC0_31") (pintype "unspecified"))
      (node (ref "U109") (pin "17") (pinfunction "B1_17") (pintype "unspecified"))
    )
    (net (code "286") (name "Z_FC1") (class "Default")
      (node (ref "C1") (pin "33") (pinfunction "FC1_33") (pintype "unspecified"))
      (node (ref "U109") (pin "18") (pinfunction "B0_18") (pintype "unspecified"))
    )
    (net (code "287") (name "Z_FC2") (class "Default")
      (node (ref "C1") (pin "35") (pinfunction "FC2_35") (pintype "unspecified"))
      (node (ref "U103") (pin "12") (pinfunction "B6_12") (pintype "unspecified"))
    )
    (net (code "288") (name "Z_FCS") (class "Default")
      (node (ref "C1") (pin "97") (pinfunction "/FCS,NC_97") (pintype "unspecified"))
      (node (ref "FB501") (pin "2") (pinfunction "2_2") (pintype "unspecified"))
      (node (ref "U305") (pin "21") (pinfunction "IOQ_21") (pintype "unspecified"))
    )
    (net (code "289") (name "Z_INT2") (class "Default")
      (node (ref "C1") (pin "19") (pinfunction "/INT2_19") (pintype "bidirectional"))
      (node (ref "U207") (pin "27") (pinfunction "IOQ_27") (pintype "unspecified"))
    )
    (net (code "290") (name "Z_IORST") (class "Default")
      (node (ref "C1") (pin "94") (pinfunction "/IORST,/BUSRST_94") (pintype "bidirectional"))
      (node (ref "U307") (pin "9") (pinfunction "4A_9") (pintype "unspecified"))
    )
    (net (code "291") (name "Z_LOCK") (class "Default")
      (node (ref "C1") (pin "29") (pinfunction "/LOCK,A1_29") (pintype "unspecified"))
      (node (ref "U203") (pin "6") (pinfunction "I_6") (pintype "unspecified"))
    )
    (net (code "292") (name "Z_MTACK") (class "Default")
      (node (ref "C1") (pin "48") (pinfunction "/MTACK,/VPA_48") (pintype "bidirectional"))
      (node (ref "U306") (pin "5") (pinfunction "I_5") (pintype "unspecified"))
    )
    (net (code "293") (name "Z_MTCR") (class "Default")
      (node (ref "C1") (pin "18") (pinfunction "/MTCR,XRDY_18") (pintype "bidirectional"))
      (node (ref "U109") (pin "15") (pinfunction "B3_15") (pintype "unspecified"))
    )
    (net (code "294") (name "Z_READ") (class "Default")
      (node (ref "C1") (pin "68") (pinfunction "READ_68") (pintype "unspecified"))
      (node (ref "U103") (pin "11") (pinfunction "B7_11") (pintype "unspecified"))
    )
    (net (code "295") (name "Z_SENSEZ3") (class "Default")
      (node (ref "C1") (pin "91") (pinfunction "SenseZ3,GND_91") (pintype "output"))
      (node (ref "R100A") (pin "1") (pinfunction "1_1") (pintype "input"))
      (node (ref "U202") (pin "20") (pinfunction "IOQ_20") (pintype "unspecified"))
    )
    (net (code "296") (name "Z_SLAVE") (class "Default")
      (node (ref "C1") (pin "09") (pinfunction "/SLAVEn_09") (pintype "bidirectional"))
      (node (ref "U202") (pin "26") (pinfunction "IOQ_26") (pintype "unspecified"))
      (node (ref "U203") (pin "20") (pinfunction "IOQ_20") (pintype "unspecified"))
      (node (ref "U205") (pin "3") (pinfunction "I_3") (pintype "unspecified"))
      (node (ref "U207") (pin "13") (pinfunction "I_13") (pintype "unspecified"))
      (node (ref "U303") (pin "7") (pinfunction "I_7") (pintype "unspecified"))
    )
    (net (code "297") (name "unconnected-(C1--5V-Pad08)") (class "Default")
      (node (ref "C1") (pin "08") (pinfunction "-5V_08") (pintype "bidirectional+no_connect"))
    )
    (net (code "298") (name "unconnected-(C1--12V-Pad20)") (class "Default")
      (node (ref "C1") (pin "20") (pinfunction "-12V_20") (pintype "unspecified+no_connect"))
    )
    (net (code "299") (name "unconnected-(C1-CDAC_Clock-Pad15)") (class "Default")
      (node (ref "C1") (pin "15") (pinfunction "CDAC_Clock_15") (pintype "unspecified+no_connect"))
    )
    (net (code "300") (name "unconnected-(C1-E_Clock-Pad50)") (class "Default")
      (node (ref "C1") (pin "50") (pinfunction "E_Clock_50") (pintype "bidirectional+no_connect"))
    )
    (net (code "301") (name "unconnected-(C1-RSVD,{slash}EINT1-Pad96)") (class "Default")
      (node (ref "C1") (pin "96") (pinfunction "RSVD,/EINT1_96") (pintype "bidirectional+no_connect"))
    )
    (net (code "302") (name "unconnected-(C1-RSVD,{slash}EINT4-Pad44)") (class "Default")
      (node (ref "C1") (pin "44") (pinfunction "RSVD,/EINT4_44") (pintype "bidirectional+no_connect"))
    )
    (net (code "303") (name "unconnected-(C1-RSVD,{slash}EINT5-Pad42)") (class "Default")
      (node (ref "C1") (pin "42") (pinfunction "RSVD,/EINT5_42") (pintype "bidirectional+no_connect"))
    )
    (net (code "304") (name "unconnected-(C1-RSVD,{slash}EINT7-Pad40)") (class "Default")
      (node (ref "C1") (pin "40") (pinfunction "RSVD,/EINT7_40") (pintype "bidirectional+no_connect"))
    )
    (net (code "305") (name "unconnected-(C1-{slash}BCLR,{slash}GBG-Pad95)") (class "Default")
      (node (ref "C1") (pin "95") (pinfunction "/BCLR,/GBG_95") (pintype "bidirectional+no_connect"))
    )
    (net (code "306") (name "unconnected-(C1-{slash}BGACK-Pad62)") (class "Default")
      (node (ref "C1") (pin "62") (pinfunction "/BGACK_62") (pintype "bidirectional+no_connect"))
    )
    (net (code "307") (name "unconnected-(C1-{slash}C1_Clock-Pad16)") (class "Default")
      (node (ref "C1") (pin "16") (pinfunction "/C1_Clock_16") (pintype "bidirectional+no_connect"))
    )
    (net (code "308") (name "unconnected-(C1-{slash}C3_Clock-Pad14)") (class "Default")
      (node (ref "C1") (pin "14") (pinfunction "/C3_Clock_14") (pintype "bidirectional+no_connect"))
    )
    (net (code "309") (name "unconnected-(C1-{slash}CCS,{slash}AS-Pad74)") (class "Default")
      (node (ref "C1") (pin "74") (pinfunction "/CCS,/AS_74") (pintype "unspecified+no_connect"))
    )
    (net (code "310") (name "unconnected-(C1-{slash}HLT-Pad55)") (class "Default")
      (node (ref "C1") (pin "55") (pinfunction "/HLT_55") (pintype "output+no_connect"))
    )
    (net (code "311") (name "unconnected-(C1-{slash}INT6-Pad22)") (class "Default")
      (node (ref "C1") (pin "22") (pinfunction "/INT6_22") (pintype "output+no_connect"))
    )
    (net (code "312") (name "unconnected-(C1-{slash}OWN-Pad07)") (class "Default")
      (node (ref "C1") (pin "07") (pinfunction "/OWN_07") (pintype "unspecified+no_connect"))
    )
    (net (code "313") (name "unconnected-(C1-{slash}RST-Pad53)") (class "Default")
      (node (ref "C1") (pin "53") (pinfunction "/RST_53") (pintype "unspecified+no_connect"))
    )
    (net (code "314") (name "unconnected-(CN4-Pad1)") (class "Default")
      (node (ref "CN4") (pin "1") (pinfunction "1_1") (pintype "unspecified+no_connect"))
    )
    (net (code "315") (name "unconnected-(CN309-Pad25)") (class "Default")
      (node (ref "CN309") (pin "25") (pinfunction "25_25") (pintype "unspecified+no_connect"))
    )
    (net (code "316") (name "unconnected-(CN309-Pad34)") (class "Default")
      (node (ref "CN309") (pin "34") (pinfunction "34_34") (pintype "unspecified+no_connect"))
    )
    (net (code "317") (name "unconnected-(CN310-NC-Pad12)") (class "Default")
      (node (ref "CN310") (pin "12") (pinfunction "NC_12") (pintype "unspecified+no_connect"))
    )
    (net (code "318") (name "unconnected-(CN310-NC-Pad13)") (class "Default")
      (node (ref "CN310") (pin "13") (pinfunction "NC_13") (pintype "unspecified+no_connect"))
    )
    (net (code "319") (name "unconnected-(CN310-NC-Pad14)") (class "Default")
      (node (ref "CN310") (pin "14") (pinfunction "NC_14") (pintype "unspecified+no_connect"))
    )
    (net (code "320") (name "unconnected-(CN310-RSVD-Pad37)") (class "Default")
      (node (ref "CN310") (pin "37") (pinfunction "RSVD_37") (pintype "unspecified+no_connect"))
    )
    (net (code "321") (name "unconnected-(CN310-RSVD-Pad39)") (class "Default")
      (node (ref "CN310") (pin "39") (pinfunction "RSVD_39") (pintype "unspecified+no_connect"))
    )
    (net (code "322") (name "unconnected-(CN400-Pad25)") (class "Default")
      (node (ref "CN400") (pin "25") (pinfunction "25_25") (pintype "unspecified+no_connect"))
    )
    (net (code "323") (name "unconnected-(U202-IOQ-Pad25)") (class "Default")
      (node (ref "U202") (pin "25") (pinfunction "IOQ_25") (pintype "unspecified+no_connect"))
    )
    (net (code "324") (name "unconnected-(U202-NC-Pad1)") (class "Default")
      (node (ref "U202") (pin "1") (pinfunction "NC_1") (pintype "unspecified+no_connect"))
    )
    (net (code "325") (name "unconnected-(U202-NC-Pad8)") (class "Default")
      (node (ref "U202") (pin "8") (pinfunction "NC_8") (pintype "unspecified+no_connect"))
    )
    (net (code "326") (name "unconnected-(U202-NC-Pad15)") (class "Default")
      (node (ref "U202") (pin "15") (pinfunction "NC_15") (pintype "unspecified+no_connect"))
    )
    (net (code "327") (name "unconnected-(U202-NC-Pad22)") (class "Default")
      (node (ref "U202") (pin "22") (pinfunction "NC_22") (pintype "unspecified+no_connect"))
    )
    (net (code "328") (name "unconnected-(U203-IOQ-Pad18)") (class "Default")
      (node (ref "U203") (pin "18") (pinfunction "IOQ_18") (pintype "unspecified+no_connect"))
    )
    (net (code "329") (name "unconnected-(U203-IOQ-Pad19)") (class "Default")
      (node (ref "U203") (pin "19") (pinfunction "IOQ_19") (pintype "unspecified+no_connect"))
    )
    (net (code "330") (name "unconnected-(U203-IOQ-Pad21)") (class "Default")
      (node (ref "U203") (pin "21") (pinfunction "IOQ_21") (pintype "unspecified+no_connect"))
    )
    (net (code "331") (name "unconnected-(U203-NC-Pad1)") (class "Default")
      (node (ref "U203") (pin "1") (pinfunction "NC_1") (pintype "unspecified+no_connect"))
    )
    (net (code "332") (name "unconnected-(U203-NC-Pad8)") (class "Default")
      (node (ref "U203") (pin "8") (pinfunction "NC_8") (pintype "unspecified+no_connect"))
    )
    (net (code "333") (name "unconnected-(U203-NC-Pad15)") (class "Default")
      (node (ref "U203") (pin "15") (pinfunction "NC_15") (pintype "unspecified+no_connect"))
    )
    (net (code "334") (name "unconnected-(U203-NC-Pad22)") (class "Default")
      (node (ref "U203") (pin "22") (pinfunction "NC_22") (pintype "unspecified+no_connect"))
    )
    (net (code "335") (name "unconnected-(U205-NC-Pad1)") (class "Default")
      (node (ref "U205") (pin "1") (pinfunction "NC_1") (pintype "unspecified+no_connect"))
    )
    (net (code "336") (name "unconnected-(U205-NC-Pad8)") (class "Default")
      (node (ref "U205") (pin "8") (pinfunction "NC_8") (pintype "unspecified+no_connect"))
    )
    (net (code "337") (name "unconnected-(U205-NC-Pad15)") (class "Default")
      (node (ref "U205") (pin "15") (pinfunction "NC_15") (pintype "unspecified+no_connect"))
    )
    (net (code "338") (name "unconnected-(U205-NC-Pad22)") (class "Default")
      (node (ref "U205") (pin "22") (pinfunction "NC_22") (pintype "unspecified+no_connect"))
    )
    (net (code "339") (name "unconnected-(U207-I-Pad3)") (class "Default")
      (node (ref "U207") (pin "3") (pinfunction "I_3") (pintype "unspecified+no_connect"))
    )
    (net (code "340") (name "unconnected-(U207-I-Pad4)") (class "Default")
      (node (ref "U207") (pin "4") (pinfunction "I_4") (pintype "unspecified+no_connect"))
    )
    (net (code "341") (name "unconnected-(U207-I-Pad5)") (class "Default")
      (node (ref "U207") (pin "5") (pinfunction "I_5") (pintype "unspecified+no_connect"))
    )
    (net (code "342") (name "unconnected-(U207-IOQ-Pad17)") (class "Default")
      (node (ref "U207") (pin "17") (pinfunction "IOQ_17") (pintype "unspecified+no_connect"))
    )
    (net (code "343") (name "unconnected-(U207-IOQ-Pad18)") (class "Default")
      (node (ref "U207") (pin "18") (pinfunction "IOQ_18") (pintype "unspecified+no_connect"))
    )
    (net (code "344") (name "unconnected-(U207-IOQ-Pad20)") (class "Default")
      (node (ref "U207") (pin "20") (pinfunction "IOQ_20") (pintype "unspecified+no_connect"))
    )
    (net (code "345") (name "unconnected-(U207-IOQ-Pad21)") (class "Default")
      (node (ref "U207") (pin "21") (pinfunction "IOQ_21") (pintype "unspecified+no_connect"))
    )
    (net (code "346") (name "unconnected-(U207-IOQ-Pad23)") (class "Default")
      (node (ref "U207") (pin "23") (pinfunction "IOQ_23") (pintype "unspecified+no_connect"))
    )
    (net (code "347") (name "unconnected-(U207-IOQ-Pad25)") (class "Default")
      (node (ref "U207") (pin "25") (pinfunction "IOQ_25") (pintype "unspecified+no_connect"))
    )
    (net (code "348") (name "unconnected-(U207-NC-Pad1)") (class "Default")
      (node (ref "U207") (pin "1") (pinfunction "NC_1") (pintype "unspecified+no_connect"))
    )
    (net (code "349") (name "unconnected-(U207-NC-Pad8)") (class "Default")
      (node (ref "U207") (pin "8") (pinfunction "NC_8") (pintype "unspecified+no_connect"))
    )
    (net (code "350") (name "unconnected-(U207-NC-Pad15)") (class "Default")
      (node (ref "U207") (pin "15") (pinfunction "NC_15") (pintype "unspecified+no_connect"))
    )
    (net (code "351") (name "unconnected-(U207-NC-Pad22)") (class "Default")
      (node (ref "U207") (pin "22") (pinfunction "NC_22") (pintype "unspecified+no_connect"))
    )
    (net (code "352") (name "unconnected-(U300-BSYDIR-Pad108)") (class "Default")
      (node (ref "U300") (pin "108") (pinfunction "BSYDIR_108") (pintype "unspecified+no_connect"))
    )
    (net (code "353") (name "unconnected-(U300-FETCH{slash}-Pad97)") (class "Default")
      (node (ref "U300") (pin "97") (pinfunction "FETCH/_97") (pintype "unspecified+no_connect"))
    )
    (net (code "354") (name "unconnected-(U300-IGS-Pad104)") (class "Default")
      (node (ref "U300") (pin "104") (pinfunction "IGS_104") (pintype "unspecified+no_connect"))
    )
    (net (code "355") (name "unconnected-(U300-RSTDIR-Pad107)") (class "Default")
      (node (ref "U300") (pin "107") (pinfunction "RSTDIR_107") (pintype "unspecified+no_connect"))
    )
    (net (code "356") (name "unconnected-(U300-SC0-Pad88)") (class "Default")
      (node (ref "U300") (pin "88") (pinfunction "SC0_88") (pintype "unspecified+no_connect"))
    )
    (net (code "357") (name "unconnected-(U300-SC1-Pad89)") (class "Default")
      (node (ref "U300") (pin "89") (pinfunction "SC1_89") (pintype "unspecified+no_connect"))
    )
    (net (code "358") (name "unconnected-(U300-SDIR0-Pad142)") (class "Default")
      (node (ref "U300") (pin "142") (pinfunction "SDIR0_142") (pintype "unspecified+no_connect"))
    )
    (net (code "359") (name "unconnected-(U300-SDIR1-Pad141)") (class "Default")
      (node (ref "U300") (pin "141") (pinfunction "SDIR1_141") (pintype "unspecified+no_connect"))
    )
    (net (code "360") (name "unconnected-(U300-SDIR2-Pad140)") (class "Default")
      (node (ref "U300") (pin "140") (pinfunction "SDIR2_140") (pintype "unspecified+no_connect"))
    )
    (net (code "361") (name "unconnected-(U300-SDIR3-Pad138)") (class "Default")
      (node (ref "U300") (pin "138") (pinfunction "SDIR3_138") (pintype "unspecified+no_connect"))
    )
    (net (code "362") (name "unconnected-(U300-SDIR4-Pad137)") (class "Default")
      (node (ref "U300") (pin "137") (pinfunction "SDIR4_137") (pintype "unspecified+no_connect"))
    )
    (net (code "363") (name "unconnected-(U300-SDIR5-Pad135)") (class "Default")
      (node (ref "U300") (pin "135") (pinfunction "SDIR5_135") (pintype "unspecified+no_connect"))
    )
    (net (code "364") (name "unconnected-(U300-SDIR6-Pad134)") (class "Default")
      (node (ref "U300") (pin "134") (pinfunction "SDIR6_134") (pintype "unspecified+no_connect"))
    )
    (net (code "365") (name "unconnected-(U300-SDIR7-Pad133)") (class "Default")
      (node (ref "U300") (pin "133") (pinfunction "SDIR7_133") (pintype "unspecified+no_connect"))
    )
    (net (code "366") (name "unconnected-(U300-SDIRP-Pad132)") (class "Default")
      (node (ref "U300") (pin "132") (pinfunction "SDIRP_132") (pintype "unspecified+no_connect"))
    )
    (net (code "367") (name "unconnected-(U300-SELDIR-Pad106)") (class "Default")
      (node (ref "U300") (pin "106") (pinfunction "SELDIR_106") (pintype "unspecified+no_connect"))
    )
    (net (code "368") (name "unconnected-(U300-TGS-Pad103)") (class "Default")
      (node (ref "U300") (pin "103") (pinfunction "TGS_103") (pintype "unspecified+no_connect"))
    )
    (net (code "369") (name "unconnected-(U300-UPS0-TT0{slash}-Pad34)") (class "Default")
      (node (ref "U300") (pin "34") (pinfunction "UPS0-TT0/_34") (pintype "unspecified+no_connect"))
    )
    (net (code "370") (name "unconnected-(U301-N.C-Pad1)") (class "Default")
      (node (ref "U301") (pin "1") (pinfunction "N.C_1") (pintype "unspecified+no_connect"))
    )
    (net (code "371") (name "unconnected-(U302-Q1#-Pad8)") (class "Default")
      (node (ref "U302") (pin "8") (pinfunction "Q1#_8") (pintype "unspecified+no_connect"))
    )
    (net (code "372") (name "unconnected-(U302-Q1-Pad9)") (class "Default")
      (node (ref "U302") (pin "9") (pinfunction "Q1_9") (pintype "unspecified+no_connect"))
    )
    (net (code "373") (name "unconnected-(U303-I-Pad13)") (class "Default")
      (node (ref "U303") (pin "13") (pinfunction "I_13") (pintype "unspecified+no_connect"))
    )
    (net (code "374") (name "unconnected-(U303-I-Pad16)") (class "Default")
      (node (ref "U303") (pin "16") (pinfunction "I_16") (pintype "unspecified+no_connect"))
    )
    (net (code "375") (name "unconnected-(U303-IOQ-Pad17)") (class "Default")
      (node (ref "U303") (pin "17") (pinfunction "IOQ_17") (pintype "unspecified+no_connect"))
    )
    (net (code "376") (name "unconnected-(U303-IOQ-Pad18)") (class "Default")
      (node (ref "U303") (pin "18") (pinfunction "IOQ_18") (pintype "unspecified+no_connect"))
    )
    (net (code "377") (name "unconnected-(U303-IOQ-Pad19)") (class "Default")
      (node (ref "U303") (pin "19") (pinfunction "IOQ_19") (pintype "unspecified+no_connect"))
    )
    (net (code "378") (name "unconnected-(U303-IOQ-Pad23)") (class "Default")
      (node (ref "U303") (pin "23") (pinfunction "IOQ_23") (pintype "unspecified+no_connect"))
    )
    (net (code "379") (name "unconnected-(U303-IOQ-Pad24)") (class "Default")
      (node (ref "U303") (pin "24") (pinfunction "IOQ_24") (pintype "unspecified+no_connect"))
    )
    (net (code "380") (name "unconnected-(U303-IOQ-Pad26)") (class "Default")
      (node (ref "U303") (pin "26") (pinfunction "IOQ_26") (pintype "unspecified+no_connect"))
    )
    (net (code "381") (name "unconnected-(U303-NC-Pad1)") (class "Default")
      (node (ref "U303") (pin "1") (pinfunction "NC_1") (pintype "unspecified+no_connect"))
    )
    (net (code "382") (name "unconnected-(U303-NC-Pad8)") (class "Default")
      (node (ref "U303") (pin "8") (pinfunction "NC_8") (pintype "unspecified+no_connect"))
    )
    (net (code "383") (name "unconnected-(U303-NC-Pad15)") (class "Default")
      (node (ref "U303") (pin "15") (pinfunction "NC_15") (pintype "unspecified+no_connect"))
    )
    (net (code "384") (name "unconnected-(U303-NC-Pad22)") (class "Default")
      (node (ref "U303") (pin "22") (pinfunction "NC_22") (pintype "unspecified+no_connect"))
    )
    (net (code "385") (name "unconnected-(U304-I-Pad16)") (class "Default")
      (node (ref "U304") (pin "16") (pinfunction "I_16") (pintype "unspecified+no_connect"))
    )
    (net (code "386") (name "unconnected-(U304-IOQ-Pad17)") (class "Default")
      (node (ref "U304") (pin "17") (pinfunction "IOQ_17") (pintype "unspecified+no_connect"))
    )
    (net (code "387") (name "unconnected-(U304-IOQ-Pad18)") (class "Default")
      (node (ref "U304") (pin "18") (pinfunction "IOQ_18") (pintype "unspecified+no_connect"))
    )
    (net (code "388") (name "unconnected-(U304-IOQ-Pad23)") (class "Default")
      (node (ref "U304") (pin "23") (pinfunction "IOQ_23") (pintype "unspecified+no_connect"))
    )
    (net (code "389") (name "unconnected-(U304-NC-Pad1)") (class "Default")
      (node (ref "U304") (pin "1") (pinfunction "NC_1") (pintype "unspecified+no_connect"))
    )
    (net (code "390") (name "unconnected-(U304-NC-Pad8)") (class "Default")
      (node (ref "U304") (pin "8") (pinfunction "NC_8") (pintype "unspecified+no_connect"))
    )
    (net (code "391") (name "unconnected-(U304-NC-Pad15)") (class "Default")
      (node (ref "U304") (pin "15") (pinfunction "NC_15") (pintype "unspecified+no_connect"))
    )
    (net (code "392") (name "unconnected-(U304-NC-Pad22)") (class "Default")
      (node (ref "U304") (pin "22") (pinfunction "NC_22") (pintype "unspecified+no_connect"))
    )
    (net (code "393") (name "unconnected-(U305-I-Pad11)") (class "Default")
      (node (ref "U305") (pin "11") (pinfunction "I_11") (pintype "unspecified+no_connect"))
    )
    (net (code "394") (name "unconnected-(U305-I-Pad12)") (class "Default")
      (node (ref "U305") (pin "12") (pinfunction "I_12") (pintype "unspecified+no_connect"))
    )
    (net (code "395") (name "unconnected-(U305-IOQ-Pad17)") (class "Default")
      (node (ref "U305") (pin "17") (pinfunction "IOQ_17") (pintype "unspecified+no_connect"))
    )
    (net (code "396") (name "unconnected-(U305-IOQ-Pad18)") (class "Default")
      (node (ref "U305") (pin "18") (pinfunction "IOQ_18") (pintype "unspecified+no_connect"))
    )
    (net (code "397") (name "unconnected-(U305-NC-Pad1)") (class "Default")
      (node (ref "U305") (pin "1") (pinfunction "NC_1") (pintype "unspecified+no_connect"))
    )
    (net (code "398") (name "unconnected-(U305-NC-Pad8)") (class "Default")
      (node (ref "U305") (pin "8") (pinfunction "NC_8") (pintype "unspecified+no_connect"))
    )
    (net (code "399") (name "unconnected-(U305-NC-Pad15)") (class "Default")
      (node (ref "U305") (pin "15") (pinfunction "NC_15") (pintype "unspecified+no_connect"))
    )
    (net (code "400") (name "unconnected-(U305-NC-Pad22)") (class "Default")
      (node (ref "U305") (pin "22") (pinfunction "NC_22") (pintype "unspecified+no_connect"))
    )
    (net (code "401") (name "unconnected-(U306-I-Pad16)") (class "Default")
      (node (ref "U306") (pin "16") (pinfunction "I_16") (pintype "unspecified+no_connect"))
    )
    (net (code "402") (name "unconnected-(U306-IOQ-Pad18)") (class "Default")
      (node (ref "U306") (pin "18") (pinfunction "IOQ_18") (pintype "unspecified+no_connect"))
    )
    (net (code "403") (name "unconnected-(U306-IOQ-Pad24)") (class "Default")
      (node (ref "U306") (pin "24") (pinfunction "IOQ_24") (pintype "unspecified+no_connect"))
    )
    (net (code "404") (name "unconnected-(U306-IOQ-Pad26)") (class "Default")
      (node (ref "U306") (pin "26") (pinfunction "IOQ_26") (pintype "unspecified+no_connect"))
    )
    (net (code "405") (name "unconnected-(U306-NC-Pad1)") (class "Default")
      (node (ref "U306") (pin "1") (pinfunction "NC_1") (pintype "unspecified+no_connect"))
    )
    (net (code "406") (name "unconnected-(U306-NC-Pad8)") (class "Default")
      (node (ref "U306") (pin "8") (pinfunction "NC_8") (pintype "unspecified+no_connect"))
    )
    (net (code "407") (name "unconnected-(U306-NC-Pad15)") (class "Default")
      (node (ref "U306") (pin "15") (pinfunction "NC_15") (pintype "unspecified+no_connect"))
    )
    (net (code "408") (name "unconnected-(U306-NC-Pad22)") (class "Default")
      (node (ref "U306") (pin "22") (pinfunction "NC_22") (pintype "unspecified+no_connect"))
    )
    (net (code "409") (name "unconnected-(U307-5Y-Pad10)") (class "Default")
      (node (ref "U307") (pin "10") (pinfunction "5Y_10") (pintype "unspecified+no_connect"))
    )
    (net (code "410") (name "unconnected-(U307-6Y-Pad12)") (class "Default")
      (node (ref "U307") (pin "12") (pinfunction "6Y_12") (pintype "unspecified+no_connect"))
    )
    (net (code "411") (name "unconnected-(U310-NC-Pad14)") (class "Default")
      (node (ref "U310") (pin "14") (pinfunction "NC_14") (pintype "unspecified+no_connect"))
    )
    (net (code "412") (name "unconnected-(U311-NC-Pad14)") (class "Default")
      (node (ref "U311") (pin "14") (pinfunction "NC_14") (pintype "unspecified+no_connect"))
    )
    (net (code "413") (name "unconnected-(U400-NC-Pad14)") (class "Default")
      (node (ref "U400") (pin "14") (pinfunction "NC_14") (pintype "unspecified+no_connect"))
    )
    (net (code "414") (name "unconnected-(U400-PD#-Pad16)") (class "Default")
      (node (ref "U400") (pin "16") (pinfunction "PD#_16") (pintype "unspecified+no_connect"))
    )
    (net (code "415") (name "unconnected-(U401-NC-Pad14)") (class "Default")
      (node (ref "U401") (pin "14") (pinfunction "NC_14") (pintype "unspecified+no_connect"))
    )
    (net (code "416") (name "unconnected-(U401-PD#-Pad16)") (class "Default")
      (node (ref "U401") (pin "16") (pinfunction "PD#_16") (pintype "unspecified+no_connect"))
    )
  )
)
